# M8317E.net
KiCad netlist of a schematic drawn in EAGLE
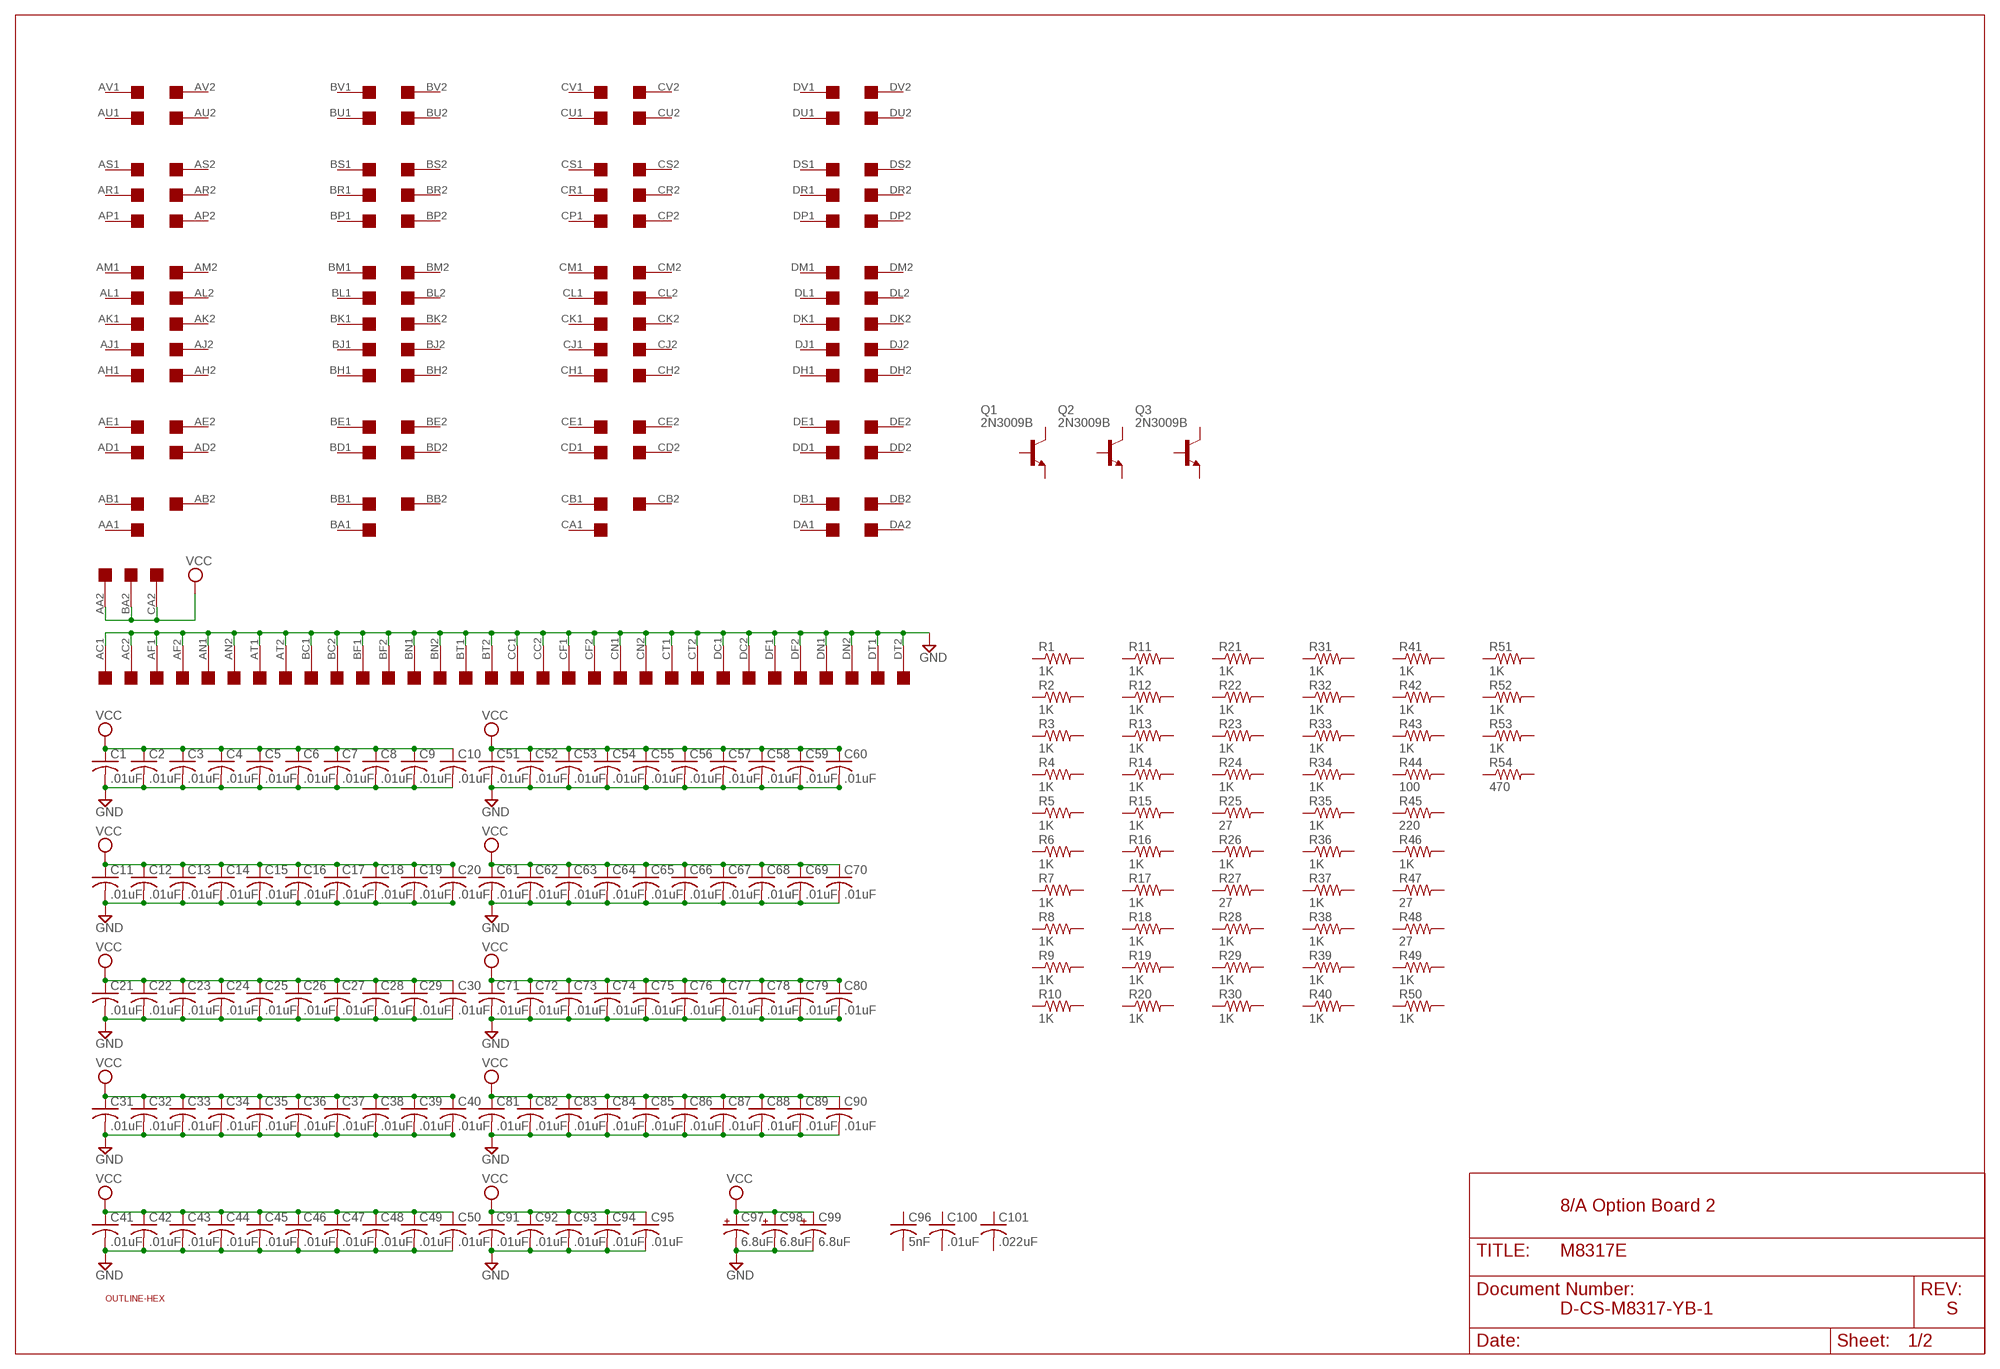
[diagram p0: schematic, sheet 1]
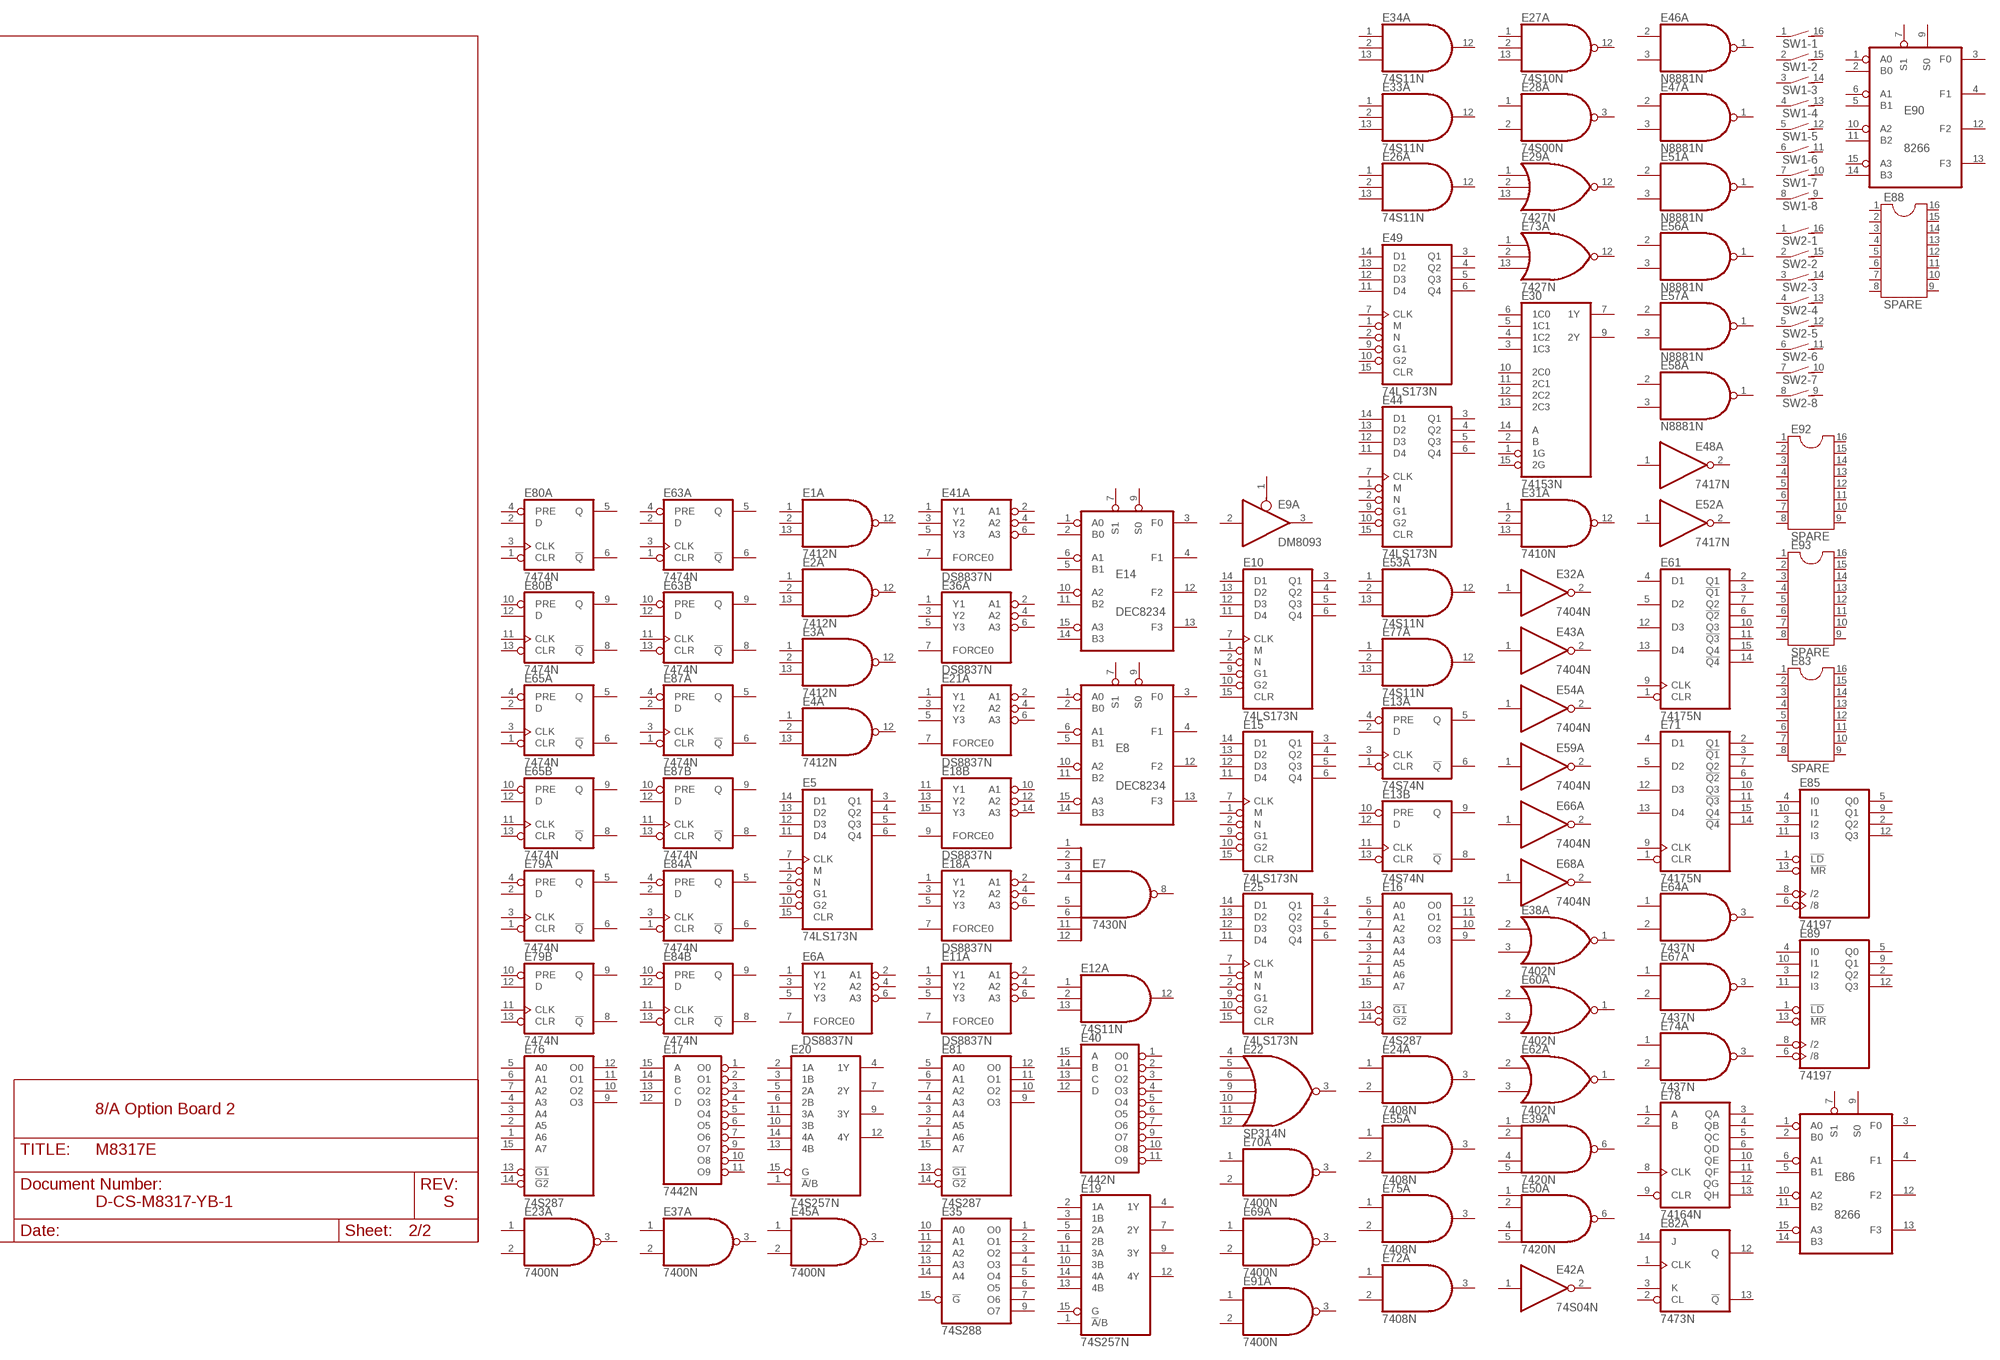
[diagram p1: schematic, sheet 2]

(export (version "E")
  (design (tool "Eeschema 10.0.6"))
  (components
    (comp (ref "C1")
      (value ".01uF")
      (footprint "eagle-import:C063-025X075")
      (libsource (lib "eagle-import") (part "C-US"))
    )
    (comp (ref "C2")
      (value ".01uF")
      (footprint "eagle-import:C063-025X075")
      (libsource (lib "eagle-import") (part "C-US"))
    )
    (comp (ref "C3")
      (value ".01uF")
      (footprint "eagle-import:C063-025X075")
      (libsource (lib "eagle-import") (part "C-US"))
    )
    (comp (ref "C4")
      (value ".01uF")
      (footprint "eagle-import:C063-025X075")
      (libsource (lib "eagle-import") (part "C-US"))
    )
    (comp (ref "C5")
      (value ".01uF")
      (footprint "eagle-import:C063-025X075")
      (libsource (lib "eagle-import") (part "C-US"))
    )
    (comp (ref "C6")
      (value ".01uF")
      (footprint "eagle-import:C063-025X075")
      (libsource (lib "eagle-import") (part "C-US"))
    )
    (comp (ref "C7")
      (value ".01uF")
      (footprint "eagle-import:C063-025X075")
      (libsource (lib "eagle-import") (part "C-US"))
    )
    (comp (ref "C8")
      (value ".01uF")
      (footprint "eagle-import:C063-025X075")
      (libsource (lib "eagle-import") (part "C-US"))
    )
    (comp (ref "C9")
      (value ".01uF")
      (footprint "eagle-import:C063-025X075")
      (libsource (lib "eagle-import") (part "C-US"))
    )
    (comp (ref "C10")
      (value ".01uF")
      (footprint "eagle-import:C063-025X075")
      (libsource (lib "eagle-import") (part "C-US"))
    )
    (comp (ref "C11")
      (value ".01uF")
      (footprint "eagle-import:C063-025X075")
      (libsource (lib "eagle-import") (part "C-US"))
    )
    (comp (ref "C12")
      (value ".01uF")
      (footprint "eagle-import:C063-025X075")
      (libsource (lib "eagle-import") (part "C-US"))
    )
    (comp (ref "C13")
      (value ".01uF")
      (footprint "eagle-import:C063-025X075")
      (libsource (lib "eagle-import") (part "C-US"))
    )
    (comp (ref "C14")
      (value ".01uF")
      (footprint "eagle-import:C063-025X075")
      (libsource (lib "eagle-import") (part "C-US"))
    )
    (comp (ref "C15")
      (value ".01uF")
      (footprint "eagle-import:C063-025X075")
      (libsource (lib "eagle-import") (part "C-US"))
    )
    (comp (ref "C16")
      (value ".01uF")
      (footprint "eagle-import:C063-025X075")
      (libsource (lib "eagle-import") (part "C-US"))
    )
    (comp (ref "C17")
      (value ".01uF")
      (footprint "eagle-import:C063-025X075")
      (libsource (lib "eagle-import") (part "C-US"))
    )
    (comp (ref "C18")
      (value ".01uF")
      (footprint "eagle-import:C063-025X075")
      (libsource (lib "eagle-import") (part "C-US"))
    )
    (comp (ref "C19")
      (value ".01uF")
      (footprint "eagle-import:C063-025X075")
      (libsource (lib "eagle-import") (part "C-US"))
    )
    (comp (ref "C20")
      (value ".01uF")
      (footprint "eagle-import:C063-025X075")
      (libsource (lib "eagle-import") (part "C-US"))
    )
    (comp (ref "C21")
      (value ".01uF")
      (footprint "eagle-import:C063-025X075")
      (libsource (lib "eagle-import") (part "C-US"))
    )
    (comp (ref "C22")
      (value ".01uF")
      (footprint "eagle-import:C063-025X075")
      (libsource (lib "eagle-import") (part "C-US"))
    )
    (comp (ref "C23")
      (value ".01uF")
      (footprint "eagle-import:C063-025X075")
      (libsource (lib "eagle-import") (part "C-US"))
    )
    (comp (ref "C24")
      (value ".01uF")
      (footprint "eagle-import:C063-025X075")
      (libsource (lib "eagle-import") (part "C-US"))
    )
    (comp (ref "C25")
      (value ".01uF")
      (footprint "eagle-import:C063-025X075")
      (libsource (lib "eagle-import") (part "C-US"))
    )
    (comp (ref "C26")
      (value ".01uF")
      (footprint "eagle-import:C063-025X075")
      (libsource (lib "eagle-import") (part "C-US"))
    )
    (comp (ref "C27")
      (value ".01uF")
      (footprint "eagle-import:C063-025X075")
      (libsource (lib "eagle-import") (part "C-US"))
    )
    (comp (ref "C28")
      (value ".01uF")
      (footprint "eagle-import:C063-025X075")
      (libsource (lib "eagle-import") (part "C-US"))
    )
    (comp (ref "C29")
      (value ".01uF")
      (footprint "eagle-import:C063-025X075")
      (libsource (lib "eagle-import") (part "C-US"))
    )
    (comp (ref "C30")
      (value ".01uF")
      (footprint "eagle-import:C063-025X075")
      (libsource (lib "eagle-import") (part "C-US"))
    )
    (comp (ref "C31")
      (value ".01uF")
      (footprint "eagle-import:C063-025X075")
      (libsource (lib "eagle-import") (part "C-US"))
    )
    (comp (ref "C32")
      (value ".01uF")
      (footprint "eagle-import:C063-025X075")
      (libsource (lib "eagle-import") (part "C-US"))
    )
    (comp (ref "C33")
      (value ".01uF")
      (footprint "eagle-import:C063-025X075")
      (libsource (lib "eagle-import") (part "C-US"))
    )
    (comp (ref "C34")
      (value ".01uF")
      (footprint "eagle-import:C063-025X075")
      (libsource (lib "eagle-import") (part "C-US"))
    )
    (comp (ref "C35")
      (value ".01uF")
      (footprint "eagle-import:C063-025X075")
      (libsource (lib "eagle-import") (part "C-US"))
    )
    (comp (ref "C36")
      (value ".01uF")
      (footprint "eagle-import:C063-025X075")
      (libsource (lib "eagle-import") (part "C-US"))
    )
    (comp (ref "C37")
      (value ".01uF")
      (footprint "eagle-import:C063-025X075")
      (libsource (lib "eagle-import") (part "C-US"))
    )
    (comp (ref "C38")
      (value ".01uF")
      (footprint "eagle-import:C063-025X075")
      (libsource (lib "eagle-import") (part "C-US"))
    )
    (comp (ref "C39")
      (value ".01uF")
      (footprint "eagle-import:C063-025X075")
      (libsource (lib "eagle-import") (part "C-US"))
    )
    (comp (ref "C40")
      (value ".01uF")
      (footprint "eagle-import:C063-025X075")
      (libsource (lib "eagle-import") (part "C-US"))
    )
    (comp (ref "C41")
      (value ".01uF")
      (footprint "eagle-import:C063-025X075")
      (libsource (lib "eagle-import") (part "C-US"))
    )
    (comp (ref "C42")
      (value ".01uF")
      (footprint "eagle-import:C063-025X075")
      (libsource (lib "eagle-import") (part "C-US"))
    )
    (comp (ref "C43")
      (value ".01uF")
      (footprint "eagle-import:C063-025X075")
      (libsource (lib "eagle-import") (part "C-US"))
    )
    (comp (ref "C44")
      (value ".01uF")
      (footprint "eagle-import:C063-025X075")
      (libsource (lib "eagle-import") (part "C-US"))
    )
    (comp (ref "C45")
      (value ".01uF")
      (footprint "eagle-import:C063-025X075")
      (libsource (lib "eagle-import") (part "C-US"))
    )
    (comp (ref "C46")
      (value ".01uF")
      (footprint "eagle-import:C063-025X075")
      (libsource (lib "eagle-import") (part "C-US"))
    )
    (comp (ref "C47")
      (value ".01uF")
      (footprint "eagle-import:C063-025X075")
      (libsource (lib "eagle-import") (part "C-US"))
    )
    (comp (ref "C48")
      (value ".01uF")
      (footprint "eagle-import:C063-025X075")
      (libsource (lib "eagle-import") (part "C-US"))
    )
    (comp (ref "C49")
      (value ".01uF")
      (footprint "eagle-import:C063-025X075")
      (libsource (lib "eagle-import") (part "C-US"))
    )
    (comp (ref "C50")
      (value ".01uF")
      (footprint "eagle-import:C063-025X075")
      (libsource (lib "eagle-import") (part "C-US"))
    )
    (comp (ref "C51")
      (value ".01uF")
      (footprint "eagle-import:C063-025X075")
      (libsource (lib "eagle-import") (part "C-US"))
    )
    (comp (ref "C52")
      (value ".01uF")
      (footprint "eagle-import:C063-025X075")
      (libsource (lib "eagle-import") (part "C-US"))
    )
    (comp (ref "C53")
      (value ".01uF")
      (footprint "eagle-import:C063-025X075")
      (libsource (lib "eagle-import") (part "C-US"))
    )
    (comp (ref "C54")
      (value ".01uF")
      (footprint "eagle-import:C063-025X075")
      (libsource (lib "eagle-import") (part "C-US"))
    )
    (comp (ref "C55")
      (value ".01uF")
      (footprint "eagle-import:C063-025X075")
      (libsource (lib "eagle-import") (part "C-US"))
    )
    (comp (ref "C56")
      (value ".01uF")
      (footprint "eagle-import:C063-025X075")
      (libsource (lib "eagle-import") (part "C-US"))
    )
    (comp (ref "C57")
      (value ".01uF")
      (footprint "eagle-import:C063-025X075")
      (libsource (lib "eagle-import") (part "C-US"))
    )
    (comp (ref "C58")
      (value ".01uF")
      (footprint "eagle-import:C063-025X075")
      (libsource (lib "eagle-import") (part "C-US"))
    )
    (comp (ref "C59")
      (value ".01uF")
      (footprint "eagle-import:C063-025X075")
      (libsource (lib "eagle-import") (part "C-US"))
    )
    (comp (ref "C60")
      (value ".01uF")
      (footprint "eagle-import:C063-025X075")
      (libsource (lib "eagle-import") (part "C-US"))
    )
    (comp (ref "C61")
      (value ".01uF")
      (footprint "eagle-import:C063-025X075")
      (libsource (lib "eagle-import") (part "C-US"))
    )
    (comp (ref "C62")
      (value ".01uF")
      (footprint "eagle-import:C063-025X075")
      (libsource (lib "eagle-import") (part "C-US"))
    )
    (comp (ref "C63")
      (value ".01uF")
      (footprint "eagle-import:C063-025X075")
      (libsource (lib "eagle-import") (part "C-US"))
    )
    (comp (ref "C64")
      (value ".01uF")
      (footprint "eagle-import:C063-025X075")
      (libsource (lib "eagle-import") (part "C-US"))
    )
    (comp (ref "C65")
      (value ".01uF")
      (footprint "eagle-import:C063-025X075")
      (libsource (lib "eagle-import") (part "C-US"))
    )
    (comp (ref "C66")
      (value ".01uF")
      (footprint "eagle-import:C063-025X075")
      (libsource (lib "eagle-import") (part "C-US"))
    )
    (comp (ref "C67")
      (value ".01uF")
      (footprint "eagle-import:C063-025X075")
      (libsource (lib "eagle-import") (part "C-US"))
    )
    (comp (ref "C68")
      (value ".01uF")
      (footprint "eagle-import:C063-025X075")
      (libsource (lib "eagle-import") (part "C-US"))
    )
    (comp (ref "C69")
      (value ".01uF")
      (footprint "eagle-import:C063-025X075")
      (libsource (lib "eagle-import") (part "C-US"))
    )
    (comp (ref "C70")
      (value ".01uF")
      (footprint "eagle-import:C063-025X075")
      (libsource (lib "eagle-import") (part "C-US"))
    )
    (comp (ref "C71")
      (value ".01uF")
      (footprint "eagle-import:C063-025X075")
      (libsource (lib "eagle-import") (part "C-US"))
    )
    (comp (ref "C72")
      (value ".01uF")
      (footprint "eagle-import:C063-025X075")
      (libsource (lib "eagle-import") (part "C-US"))
    )
    (comp (ref "C73")
      (value ".01uF")
      (footprint "eagle-import:C063-025X075")
      (libsource (lib "eagle-import") (part "C-US"))
    )
    (comp (ref "C74")
      (value ".01uF")
      (footprint "eagle-import:C063-025X075")
      (libsource (lib "eagle-import") (part "C-US"))
    )
    (comp (ref "C75")
      (value ".01uF")
      (footprint "eagle-import:C063-025X075")
      (libsource (lib "eagle-import") (part "C-US"))
    )
    (comp (ref "C76")
      (value ".01uF")
      (footprint "eagle-import:C063-025X075")
      (libsource (lib "eagle-import") (part "C-US"))
    )
    (comp (ref "C77")
      (value ".01uF")
      (footprint "eagle-import:C063-025X075")
      (libsource (lib "eagle-import") (part "C-US"))
    )
    (comp (ref "C78")
      (value ".01uF")
      (footprint "eagle-import:C063-025X075")
      (libsource (lib "eagle-import") (part "C-US"))
    )
    (comp (ref "C79")
      (value ".01uF")
      (footprint "eagle-import:C063-025X075")
      (libsource (lib "eagle-import") (part "C-US"))
    )
    (comp (ref "C80")
      (value ".01uF")
      (footprint "eagle-import:C063-025X075")
      (libsource (lib "eagle-import") (part "C-US"))
    )
    (comp (ref "C81")
      (value ".01uF")
      (footprint "eagle-import:C063-025X075")
      (libsource (lib "eagle-import") (part "C-US"))
    )
    (comp (ref "C82")
      (value ".01uF")
      (footprint "eagle-import:C063-025X075")
      (libsource (lib "eagle-import") (part "C-US"))
    )
    (comp (ref "C83")
      (value ".01uF")
      (footprint "eagle-import:C063-025X075")
      (libsource (lib "eagle-import") (part "C-US"))
    )
    (comp (ref "C84")
      (value ".01uF")
      (footprint "eagle-import:C063-025X075")
      (libsource (lib "eagle-import") (part "C-US"))
    )
    (comp (ref "C85")
      (value ".01uF")
      (footprint "eagle-import:C063-025X075")
      (libsource (lib "eagle-import") (part "C-US"))
    )
    (comp (ref "C86")
      (value ".01uF")
      (footprint "eagle-import:C063-025X075")
      (libsource (lib "eagle-import") (part "C-US"))
    )
    (comp (ref "C87")
      (value ".01uF")
      (footprint "eagle-import:C063-025X075")
      (libsource (lib "eagle-import") (part "C-US"))
    )
    (comp (ref "C88")
      (value ".01uF")
      (footprint "eagle-import:C063-025X075")
      (libsource (lib "eagle-import") (part "C-US"))
    )
    (comp (ref "C89")
      (value ".01uF")
      (footprint "eagle-import:C063-025X075")
      (libsource (lib "eagle-import") (part "C-US"))
    )
    (comp (ref "C90")
      (value ".01uF")
      (footprint "eagle-import:C063-025X075")
      (libsource (lib "eagle-import") (part "C-US"))
    )
    (comp (ref "C91")
      (value ".01uF")
      (footprint "eagle-import:C063-025X075")
      (libsource (lib "eagle-import") (part "C-US"))
    )
    (comp (ref "C92")
      (value ".01uF")
      (footprint "eagle-import:C063-025X075")
      (libsource (lib "eagle-import") (part "C-US"))
    )
    (comp (ref "C93")
      (value ".01uF")
      (footprint "eagle-import:C063-025X075")
      (libsource (lib "eagle-import") (part "C-US"))
    )
    (comp (ref "C94")
      (value ".01uF")
      (footprint "eagle-import:C063-025X075")
      (libsource (lib "eagle-import") (part "C-US"))
    )
    (comp (ref "C95")
      (value ".01uF")
      (footprint "eagle-import:C063-025X075")
      (libsource (lib "eagle-import") (part "C-US"))
    )
    (comp (ref "C96")
      (value "5nF")
      (footprint "eagle-import:C063-025X075")
      (libsource (lib "eagle-import") (part "C-US"))
    )
    (comp (ref "C97")
      (value "6.8uF")
      (footprint "eagle-import:E12-8")
      (libsource (lib "eagle-import") (part "CPOL-USE20-8AXIAL"))
    )
    (comp (ref "C98")
      (value "6.8uF")
      (footprint "eagle-import:E12-8")
      (libsource (lib "eagle-import") (part "CPOL-USE20-8AXIAL"))
    )
    (comp (ref "C99")
      (value "6.8uF")
      (footprint "eagle-import:E12-8")
      (libsource (lib "eagle-import") (part "CPOL-USE20-8AXIAL"))
    )
    (comp (ref "C100")
      (value ".01uF")
      (footprint "eagle-import:C063-025X075")
      (libsource (lib "eagle-import") (part "C-US"))
    )
    (comp (ref "C101")
      (value ".022uF")
      (footprint "eagle-import:C063-025X075")
      (libsource (lib "eagle-import") (part "C-US"))
    )
    (comp (ref "Q1")
      (value "2N3009B")
      (footprint "eagle-import:TO5")
      (libsource (lib "eagle-import") (part "-NPN-TO5"))
    )
    (comp (ref "Q2")
      (value "2N3009B")
      (footprint "eagle-import:TO5")
      (libsource (lib "eagle-import") (part "-NPN-TO5"))
    )
    (comp (ref "Q3")
      (value "2N3009B")
      (footprint "eagle-import:TO5")
      (libsource (lib "eagle-import") (part "-NPN-TO5"))
    )
    (comp (ref "R1")
      (value "1K")
      (footprint "eagle-import:0207_10")
      (libsource (lib "eagle-import") (part "R-US_0207/10"))
    )
    (comp (ref "R2")
      (value "1K")
      (footprint "eagle-import:0207_10")
      (libsource (lib "eagle-import") (part "R-US_0207/10"))
    )
    (comp (ref "R3")
      (value "1K")
      (footprint "eagle-import:0207_10")
      (libsource (lib "eagle-import") (part "R-US_0207/10"))
    )
    (comp (ref "R4")
      (value "1K")
      (footprint "eagle-import:0207_10")
      (libsource (lib "eagle-import") (part "R-US_0207/10"))
    )
    (comp (ref "R5")
      (value "1K")
      (footprint "eagle-import:0207_10")
      (libsource (lib "eagle-import") (part "R-US_0207/10"))
    )
    (comp (ref "R6")
      (value "1K")
      (footprint "eagle-import:0207_10")
      (libsource (lib "eagle-import") (part "R-US_0207/10"))
    )
    (comp (ref "R7")
      (value "1K")
      (footprint "eagle-import:0207_10")
      (libsource (lib "eagle-import") (part "R-US_0207/10"))
    )
    (comp (ref "R8")
      (value "1K")
      (footprint "eagle-import:0207_10")
      (libsource (lib "eagle-import") (part "R-US_0207/10"))
    )
    (comp (ref "R9")
      (value "1K")
      (footprint "eagle-import:0207_10")
      (libsource (lib "eagle-import") (part "R-US_0207/10"))
    )
    (comp (ref "R10")
      (value "1K")
      (footprint "eagle-import:0207_10")
      (libsource (lib "eagle-import") (part "R-US_0207/10"))
    )
    (comp (ref "R11")
      (value "1K")
      (footprint "eagle-import:0207_10")
      (libsource (lib "eagle-import") (part "R-US_0207/10"))
    )
    (comp (ref "R12")
      (value "1K")
      (footprint "eagle-import:0207_10")
      (libsource (lib "eagle-import") (part "R-US_0207/10"))
    )
    (comp (ref "R13")
      (value "1K")
      (footprint "eagle-import:0207_10")
      (libsource (lib "eagle-import") (part "R-US_0207/10"))
    )
    (comp (ref "R14")
      (value "1K")
      (footprint "eagle-import:0207_10")
      (libsource (lib "eagle-import") (part "R-US_0207/10"))
    )
    (comp (ref "R15")
      (value "1K")
      (footprint "eagle-import:0207_10")
      (libsource (lib "eagle-import") (part "R-US_0207/10"))
    )
    (comp (ref "R16")
      (value "1K")
      (footprint "eagle-import:0207_10")
      (libsource (lib "eagle-import") (part "R-US_0207/10"))
    )
    (comp (ref "R17")
      (value "1K")
      (footprint "eagle-import:0207_10")
      (libsource (lib "eagle-import") (part "R-US_0207/10"))
    )
    (comp (ref "R18")
      (value "1K")
      (footprint "eagle-import:0207_10")
      (libsource (lib "eagle-import") (part "R-US_0207/10"))
    )
    (comp (ref "R19")
      (value "1K")
      (footprint "eagle-import:0207_10")
      (libsource (lib "eagle-import") (part "R-US_0207/10"))
    )
    (comp (ref "R20")
      (value "1K")
      (footprint "eagle-import:0207_10")
      (libsource (lib "eagle-import") (part "R-US_0207/10"))
    )
    (comp (ref "R21")
      (value "1K")
      (footprint "eagle-import:0207_10")
      (libsource (lib "eagle-import") (part "R-US_0207/10"))
    )
    (comp (ref "R22")
      (value "1K")
      (footprint "eagle-import:0207_10")
      (libsource (lib "eagle-import") (part "R-US_0207/10"))
    )
    (comp (ref "R23")
      (value "1K")
      (footprint "eagle-import:0207_10")
      (libsource (lib "eagle-import") (part "R-US_0207/10"))
    )
    (comp (ref "R24")
      (value "1K")
      (footprint "eagle-import:0207_10")
      (libsource (lib "eagle-import") (part "R-US_0207/10"))
    )
    (comp (ref "R25")
      (value "27")
      (footprint "eagle-import:0207_10")
      (libsource (lib "eagle-import") (part "R-US_0207/10"))
    )
    (comp (ref "R26")
      (value "1K")
      (footprint "eagle-import:0207_10")
      (libsource (lib "eagle-import") (part "R-US_0207/10"))
    )
    (comp (ref "R27")
      (value "27")
      (footprint "eagle-import:0207_10")
      (libsource (lib "eagle-import") (part "R-US_0207/10"))
    )
    (comp (ref "R28")
      (value "1K")
      (footprint "eagle-import:0207_10")
      (libsource (lib "eagle-import") (part "R-US_0207/10"))
    )
    (comp (ref "R29")
      (value "1K")
      (footprint "eagle-import:0207_10")
      (libsource (lib "eagle-import") (part "R-US_0207/10"))
    )
    (comp (ref "R30")
      (value "1K")
      (footprint "eagle-import:0207_10")
      (libsource (lib "eagle-import") (part "R-US_0207/10"))
    )
    (comp (ref "R31")
      (value "1K")
      (footprint "eagle-import:0207_10")
      (libsource (lib "eagle-import") (part "R-US_0207/10"))
    )
    (comp (ref "R32")
      (value "1K")
      (footprint "eagle-import:0207_10")
      (libsource (lib "eagle-import") (part "R-US_0207/10"))
    )
    (comp (ref "R33")
      (value "1K")
      (footprint "eagle-import:0207_10")
      (libsource (lib "eagle-import") (part "R-US_0207/10"))
    )
    (comp (ref "R34")
      (value "1K")
      (footprint "eagle-import:0207_10")
      (libsource (lib "eagle-import") (part "R-US_0207/10"))
    )
    (comp (ref "R35")
      (value "1K")
      (footprint "eagle-import:0207_10")
      (libsource (lib "eagle-import") (part "R-US_0207/10"))
    )
    (comp (ref "R36")
      (value "1K")
      (footprint "eagle-import:0207_10")
      (libsource (lib "eagle-import") (part "R-US_0207/10"))
    )
    (comp (ref "R37")
      (value "1K")
      (footprint "eagle-import:0207_10")
      (libsource (lib "eagle-import") (part "R-US_0207/10"))
    )
    (comp (ref "R38")
      (value "1K")
      (footprint "eagle-import:0207_10")
      (libsource (lib "eagle-import") (part "R-US_0207/10"))
    )
    (comp (ref "R39")
      (value "1K")
      (footprint "eagle-import:0207_10")
      (libsource (lib "eagle-import") (part "R-US_0207/10"))
    )
    (comp (ref "R40")
      (value "1K")
      (footprint "eagle-import:0207_10")
      (libsource (lib "eagle-import") (part "R-US_0207/10"))
    )
    (comp (ref "R41")
      (value "1K")
      (footprint "eagle-import:0207_10")
      (libsource (lib "eagle-import") (part "R-US_0207/10"))
    )
    (comp (ref "R42")
      (value "1K")
      (footprint "eagle-import:0207_10")
      (libsource (lib "eagle-import") (part "R-US_0207/10"))
    )
    (comp (ref "R43")
      (value "1K")
      (footprint "eagle-import:0207_10")
      (libsource (lib "eagle-import") (part "R-US_0207/10"))
    )
    (comp (ref "R44")
      (value "100")
      (footprint "eagle-import:0207_10")
      (libsource (lib "eagle-import") (part "R-US_0207/10"))
    )
    (comp (ref "R45")
      (value "220")
      (footprint "eagle-import:0207_10")
      (libsource (lib "eagle-import") (part "R-US_0207/10"))
    )
    (comp (ref "R46")
      (value "1K")
      (footprint "eagle-import:0207_10")
      (libsource (lib "eagle-import") (part "R-US_0207/10"))
    )
    (comp (ref "R47")
      (value "27")
      (footprint "eagle-import:0207_10")
      (libsource (lib "eagle-import") (part "R-US_0207/10"))
    )
    (comp (ref "R48")
      (value "27")
      (footprint "eagle-import:0207_10")
      (libsource (lib "eagle-import") (part "R-US_0207/10"))
    )
    (comp (ref "R49")
      (value "1K")
      (footprint "eagle-import:0207_10")
      (libsource (lib "eagle-import") (part "R-US_0207/10"))
    )
    (comp (ref "R50")
      (value "1K")
      (footprint "eagle-import:0207_10")
      (libsource (lib "eagle-import") (part "R-US_0207/10"))
    )
    (comp (ref "R51")
      (value "1K")
      (footprint "eagle-import:0207_10")
      (libsource (lib "eagle-import") (part "R-US_0207/10"))
    )
    (comp (ref "R52")
      (value "1K")
      (footprint "eagle-import:0207_10")
      (libsource (lib "eagle-import") (part "R-US_0207/10"))
    )
    (comp (ref "R53")
      (value "1K")
      (footprint "eagle-import:0207_10")
      (libsource (lib "eagle-import") (part "R-US_0207/10"))
    )
    (comp (ref "R54")
      (value "470")
      (footprint "eagle-import:0207_10")
      (libsource (lib "eagle-import") (part "R-US_0207/10"))
    )
    (comp (ref "U$1")
      (value "HEX")
      (footprint "eagle-import:EDGE-CON12")
      (libsource (lib "eagle-import") (part "HEX"))
    )
    (comp (ref "U$2")
      (value "OUTLINE-HEX")
      (footprint "eagle-import:HEX-HEIGHT")
      (libsource (lib "eagle-import") (part "OUTLINE-HEX"))
    )
    (comp (ref "E1")
      (value "7412N")
      (footprint "eagle-import:DIL14")
      (libsource (lib "eagle-import") (part "7412N"))
    )
    (comp (ref "E2")
      (value "7412N")
      (footprint "eagle-import:DIL14")
      (libsource (lib "eagle-import") (part "7412N"))
    )
    (comp (ref "E3")
      (value "7412N")
      (footprint "eagle-import:DIL14")
      (libsource (lib "eagle-import") (part "7412N"))
    )
    (comp (ref "E4")
      (value "7412N")
      (footprint "eagle-import:DIL14")
      (libsource (lib "eagle-import") (part "7412N"))
    )
    (comp (ref "E5")
      (value "74LS173N")
      (footprint "eagle-import:DIL16")
      (libsource (lib "eagle-import") (part "74173NLS"))
    )
    (comp (ref "E6")
      (value "DS8837N")
      (footprint "eagle-import:DIL16")
      (libsource (lib "eagle-import") (part "DS8837N"))
    )
    (comp (ref "E7")
      (value "7430N")
      (footprint "eagle-import:DIL14")
      (libsource (lib "eagle-import") (part "7430N"))
    )
    (comp (ref "E8")
      (value "DEC8234")
      (footprint "eagle-import:DIL16")
      (libsource (lib "eagle-import") (part "DEC8235"))
    )
    (comp (ref "E9")
      (value "DM8093")
      (footprint "eagle-import:DIL14")
      (libsource (lib "eagle-import") (part "74125N"))
    )
    (comp (ref "E10")
      (value "74LS173N")
      (footprint "eagle-import:DIL16")
      (libsource (lib "eagle-import") (part "74173NLS"))
    )
    (comp (ref "E11")
      (value "DS8837N")
      (footprint "eagle-import:DIL16")
      (libsource (lib "eagle-import") (part "DS8837N"))
    )
    (comp (ref "E12")
      (value "74S11N")
      (footprint "eagle-import:DIL14")
      (libsource (lib "eagle-import") (part "7411NS"))
    )
    (comp (ref "E13")
      (value "74S74N")
      (footprint "eagle-import:DIL14")
      (libsource (lib "eagle-import") (part "7474NS"))
    )
    (comp (ref "E14")
      (value "DEC8234")
      (footprint "eagle-import:DIL16")
      (libsource (lib "eagle-import") (part "DEC8235"))
    )
    (comp (ref "E15")
      (value "74LS173N")
      (footprint "eagle-import:DIL16")
      (libsource (lib "eagle-import") (part "74173NLS"))
    )
    (comp (ref "E16")
      (value "74S287")
      (footprint "eagle-import:DIL16")
      (libsource (lib "eagle-import") (part "74S287"))
    )
    (comp (ref "E17")
      (value "7442N")
      (footprint "eagle-import:DIL16")
      (libsource (lib "eagle-import") (part "7442NLS"))
    )
    (comp (ref "E18")
      (value "DS8837N")
      (footprint "eagle-import:DIL16")
      (libsource (lib "eagle-import") (part "DS8837N"))
    )
    (comp (ref "E19")
      (value "74S257N")
      (footprint "eagle-import:DIL16")
      (libsource (lib "eagle-import") (part "74257NS"))
    )
    (comp (ref "E20")
      (value "74S257N")
      (footprint "eagle-import:DIL16")
      (libsource (lib "eagle-import") (part "74257NS"))
    )
    (comp (ref "E21")
      (value "DS8837N")
      (footprint "eagle-import:DIL16")
      (libsource (lib "eagle-import") (part "DS8837N"))
    )
    (comp (ref "E22")
      (value "SP314N")
      (footprint "eagle-import:DIL14")
      (libsource (lib "eagle-import") (part "SP314N"))
    )
    (comp (ref "E23")
      (value "7400N")
      (footprint "eagle-import:DIL14")
      (libsource (lib "eagle-import") (part "7400N"))
    )
    (comp (ref "E24")
      (value "7408N")
      (footprint "eagle-import:DIL14")
      (libsource (lib "eagle-import") (part "7408NS"))
    )
    (comp (ref "E25")
      (value "74LS173N")
      (footprint "eagle-import:DIL16")
      (libsource (lib "eagle-import") (part "74173NLS"))
    )
    (comp (ref "E26")
      (value "74S11N")
      (footprint "eagle-import:DIL14")
      (libsource (lib "eagle-import") (part "7411NS"))
    )
    (comp (ref "E27")
      (value "74S10N")
      (footprint "eagle-import:DIL14")
      (libsource (lib "eagle-import") (part "7410NS"))
    )
    (comp (ref "E28")
      (value "74S00N")
      (footprint "eagle-import:DIL14")
      (libsource (lib "eagle-import") (part "7400N"))
    )
    (comp (ref "E29")
      (value "7427N")
      (footprint "eagle-import:DIL14")
      (libsource (lib "eagle-import") (part "7427NLS"))
    )
    (comp (ref "E30")
      (value "74153N")
      (footprint "eagle-import:DIL16")
      (libsource (lib "eagle-import") (part "74153NS"))
    )
    (comp (ref "E31")
      (value "7410N")
      (footprint "eagle-import:DIL14")
      (libsource (lib "eagle-import") (part "7410NS"))
    )
    (comp (ref "E32")
      (value "7404N")
      (footprint "eagle-import:DIL14")
      (libsource (lib "eagle-import") (part "7404N"))
    )
    (comp (ref "E33")
      (value "74S11N")
      (footprint "eagle-import:DIL14")
      (libsource (lib "eagle-import") (part "7411NS"))
    )
    (comp (ref "E34")
      (value "74S11N")
      (footprint "eagle-import:DIL14")
      (libsource (lib "eagle-import") (part "7411NS"))
    )
    (comp (ref "E35")
      (value "74S288")
      (footprint "eagle-import:DIL16")
      (libsource (lib "eagle-import") (part "74S288"))
    )
    (comp (ref "E36")
      (value "DS8837N")
      (footprint "eagle-import:DIL16")
      (libsource (lib "eagle-import") (part "DS8837N"))
    )
    (comp (ref "E37")
      (value "7400N")
      (footprint "eagle-import:DIL14")
      (libsource (lib "eagle-import") (part "7400N"))
    )
    (comp (ref "E38")
      (value "7402N")
      (footprint "eagle-import:DIL14")
      (libsource (lib "eagle-import") (part "7402N"))
    )
    (comp (ref "E39")
      (value "7420N")
      (footprint "eagle-import:DIL14")
      (libsource (lib "eagle-import") (part "7420N"))
    )
    (comp (ref "E40")
      (value "7442N")
      (footprint "eagle-import:DIL16")
      (libsource (lib "eagle-import") (part "7442NLS"))
    )
    (comp (ref "E41")
      (value "DS8837N")
      (footprint "eagle-import:DIL16")
      (libsource (lib "eagle-import") (part "DS8837N"))
    )
    (comp (ref "E42")
      (value "74S04N")
      (footprint "eagle-import:DIL14")
      (libsource (lib "eagle-import") (part "7404N"))
    )
    (comp (ref "E43")
      (value "7404N")
      (footprint "eagle-import:DIL14")
      (libsource (lib "eagle-import") (part "7404N"))
    )
    (comp (ref "E44")
      (value "74LS173N")
      (footprint "eagle-import:DIL16")
      (libsource (lib "eagle-import") (part "74173NLS"))
    )
    (comp (ref "E45")
      (value "7400N")
      (footprint "eagle-import:DIL14")
      (libsource (lib "eagle-import") (part "7400N"))
    )
    (comp (ref "E46")
      (value "N8881N")
      (footprint "eagle-import:DIL14")
      (libsource (lib "eagle-import") (part "N8881N"))
    )
    (comp (ref "E47")
      (value "N8881N")
      (footprint "eagle-import:DIL14")
      (libsource (lib "eagle-import") (part "N8881N"))
    )
    (comp (ref "E48")
      (value "7417N")
      (footprint "eagle-import:DIL14")
      (libsource (lib "eagle-import") (part "7417N"))
    )
    (comp (ref "E49")
      (value "74LS173N")
      (footprint "eagle-import:DIL16")
      (libsource (lib "eagle-import") (part "74173NLS"))
    )
    (comp (ref "E50")
      (value "7420N")
      (footprint "eagle-import:DIL14")
      (libsource (lib "eagle-import") (part "7420N"))
    )
    (comp (ref "E51")
      (value "N8881N")
      (footprint "eagle-import:DIL14")
      (libsource (lib "eagle-import") (part "N8881N"))
    )
    (comp (ref "E52")
      (value "7417N")
      (footprint "eagle-import:DIL14")
      (libsource (lib "eagle-import") (part "7417N"))
    )
    (comp (ref "E53")
      (value "74S11N")
      (footprint "eagle-import:DIL14")
      (libsource (lib "eagle-import") (part "7411NS"))
    )
    (comp (ref "E54")
      (value "7404N")
      (footprint "eagle-import:DIL14")
      (libsource (lib "eagle-import") (part "7404N"))
    )
    (comp (ref "E55")
      (value "7408N")
      (footprint "eagle-import:DIL14")
      (libsource (lib "eagle-import") (part "7408NS"))
    )
    (comp (ref "E56")
      (value "N8881N")
      (footprint "eagle-import:DIL14")
      (libsource (lib "eagle-import") (part "N8881N"))
    )
    (comp (ref "E57")
      (value "N8881N")
      (footprint "eagle-import:DIL14")
      (libsource (lib "eagle-import") (part "N8881N"))
    )
    (comp (ref "E58")
      (value "N8881N")
      (footprint "eagle-import:DIL14")
      (libsource (lib "eagle-import") (part "N8881N"))
    )
    (comp (ref "E59")
      (value "7404N")
      (footprint "eagle-import:DIL14")
      (libsource (lib "eagle-import") (part "7404N"))
    )
    (comp (ref "E60")
      (value "7402N")
      (footprint "eagle-import:DIL14")
      (libsource (lib "eagle-import") (part "7402N"))
    )
    (comp (ref "E61")
      (value "74175N")
      (footprint "eagle-import:DIL16")
      (libsource (lib "eagle-import") (part "74175N"))
    )
    (comp (ref "E62")
      (value "7402N")
      (footprint "eagle-import:DIL14")
      (libsource (lib "eagle-import") (part "7402N"))
    )
    (comp (ref "E63")
      (value "7474N")
      (footprint "eagle-import:DIL14")
      (libsource (lib "eagle-import") (part "7474NS"))
    )
    (comp (ref "E64")
      (value "7437N")
      (footprint "eagle-import:DIL14")
      (libsource (lib "eagle-import") (part "7437N"))
    )
    (comp (ref "E65")
      (value "7474N")
      (footprint "eagle-import:DIL14")
      (libsource (lib "eagle-import") (part "7474NS"))
    )
    (comp (ref "E66")
      (value "7404N")
      (footprint "eagle-import:DIL14")
      (libsource (lib "eagle-import") (part "7404N"))
    )
    (comp (ref "E67")
      (value "7437N")
      (footprint "eagle-import:DIL14")
      (libsource (lib "eagle-import") (part "7437N"))
    )
    (comp (ref "E68")
      (value "7404N")
      (footprint "eagle-import:DIL14")
      (libsource (lib "eagle-import") (part "7404N"))
    )
    (comp (ref "E69")
      (value "7400N")
      (footprint "eagle-import:DIL14")
      (libsource (lib "eagle-import") (part "7400N"))
    )
    (comp (ref "E70")
      (value "7400N")
      (footprint "eagle-import:DIL14")
      (libsource (lib "eagle-import") (part "7400N"))
    )
    (comp (ref "E71")
      (value "74175N")
      (footprint "eagle-import:DIL16")
      (libsource (lib "eagle-import") (part "74175N"))
    )
    (comp (ref "E72")
      (value "7408N")
      (footprint "eagle-import:DIL14")
      (libsource (lib "eagle-import") (part "7408NS"))
    )
    (comp (ref "E73")
      (value "7427N")
      (footprint "eagle-import:DIL14")
      (libsource (lib "eagle-import") (part "7427NLS"))
    )
    (comp (ref "E74")
      (value "7437N")
      (footprint "eagle-import:DIL14")
      (libsource (lib "eagle-import") (part "7437N"))
    )
    (comp (ref "E75")
      (value "7408N")
      (footprint "eagle-import:DIL14")
      (libsource (lib "eagle-import") (part "7408NS"))
    )
    (comp (ref "E76")
      (value "74S287")
      (footprint "eagle-import:DIL16")
      (libsource (lib "eagle-import") (part "74S287"))
    )
    (comp (ref "E77")
      (value "74S11N")
      (footprint "eagle-import:DIL14")
      (libsource (lib "eagle-import") (part "7411NS"))
    )
    (comp (ref "E78")
      (value "74164N")
      (footprint "eagle-import:DIL14")
      (libsource (lib "eagle-import") (part "74164N"))
    )
    (comp (ref "E79")
      (value "7474N")
      (footprint "eagle-import:DIL14")
      (libsource (lib "eagle-import") (part "7474NS"))
    )
    (comp (ref "E80")
      (value "7474N")
      (footprint "eagle-import:DIL14")
      (libsource (lib "eagle-import") (part "7474NS"))
    )
    (comp (ref "E81")
      (value "74S287")
      (footprint "eagle-import:DIL16")
      (libsource (lib "eagle-import") (part "74S287"))
    )
    (comp (ref "E82")
      (value "7473N")
      (footprint "eagle-import:DIL14")
      (libsource (lib "eagle-import") (part "7473NLS"))
    )
    (comp (ref "E83")
      (value "SPARE")
      (footprint "eagle-import:SOCKET-16")
      (libsource (lib "eagle-import") (part "DIL16S"))
    )
    (comp (ref "E84")
      (value "7474N")
      (footprint "eagle-import:DIL14")
      (libsource (lib "eagle-import") (part "7474NS"))
    )
    (comp (ref "E85")
      (value "74197")
      (footprint "eagle-import:DIL14")
      (libsource (lib "eagle-import") (part "74LS197"))
    )
    (comp (ref "E86")
      (value "8266")
      (footprint "eagle-import:DIL16")
      (libsource (lib "eagle-import") (part "8266"))
    )
    (comp (ref "E87")
      (value "7474N")
      (footprint "eagle-import:DIL14")
      (libsource (lib "eagle-import") (part "7474NS"))
    )
    (comp (ref "E88")
      (value "SPARE")
      (footprint "eagle-import:SOCKET-16")
      (libsource (lib "eagle-import") (part "DIL16S"))
    )
    (comp (ref "E89")
      (value "74197")
      (footprint "eagle-import:DIL14")
      (libsource (lib "eagle-import") (part "74LS197"))
    )
    (comp (ref "E90")
      (value "8266")
      (footprint "eagle-import:DIL16")
      (libsource (lib "eagle-import") (part "8266"))
    )
    (comp (ref "E91")
      (value "7400N")
      (footprint "eagle-import:DIL14")
      (libsource (lib "eagle-import") (part "7400N"))
    )
    (comp (ref "E92")
      (value "SPARE")
      (footprint "eagle-import:SOCKET-16")
      (libsource (lib "eagle-import") (part "DIL16S"))
    )
    (comp (ref "E93")
      (value "SPARE")
      (footprint "eagle-import:SOCKET-16")
      (libsource (lib "eagle-import") (part "DIL16S"))
    )
    (comp (ref "SW1")
      (value "DIP08S")
      (footprint "eagle-import:DIP08S")
      (libsource (lib "eagle-import") (part "DIP08S"))
    )
    (comp (ref "SW2")
      (value "DIP08S")
      (footprint "eagle-import:DIP08S")
      (libsource (lib "eagle-import") (part "DIP08S"))
    )
  )
  (nets
    (net (code "1") (name "GND") (class "Default")
      (node (ref "C1") (pin "2") (pinfunction "2_2") (pintype "passive"))
      (node (ref "C10") (pin "2") (pinfunction "2_2") (pintype "passive"))
      (node (ref "C11") (pin "2") (pinfunction "2_2") (pintype "passive"))
      (node (ref "C12") (pin "2") (pinfunction "2_2") (pintype "passive"))
      (node (ref "C13") (pin "2") (pinfunction "2_2") (pintype "passive"))
      (node (ref "C14") (pin "2") (pinfunction "2_2") (pintype "passive"))
      (node (ref "C15") (pin "2") (pinfunction "2_2") (pintype "passive"))
      (node (ref "C16") (pin "2") (pinfunction "2_2") (pintype "passive"))
      (node (ref "C17") (pin "2") (pinfunction "2_2") (pintype "passive"))
      (node (ref "C18") (pin "2") (pinfunction "2_2") (pintype "passive"))
      (node (ref "C19") (pin "2") (pinfunction "2_2") (pintype "passive"))
      (node (ref "C2") (pin "2") (pinfunction "2_2") (pintype "passive"))
      (node (ref "C20") (pin "2") (pinfunction "2_2") (pintype "passive"))
      (node (ref "C21") (pin "2") (pinfunction "2_2") (pintype "passive"))
      (node (ref "C22") (pin "2") (pinfunction "2_2") (pintype "passive"))
      (node (ref "C23") (pin "2") (pinfunction "2_2") (pintype "passive"))
      (node (ref "C24") (pin "2") (pinfunction "2_2") (pintype "passive"))
      (node (ref "C25") (pin "2") (pinfunction "2_2") (pintype "passive"))
      (node (ref "C26") (pin "2") (pinfunction "2_2") (pintype "passive"))
      (node (ref "C27") (pin "2") (pinfunction "2_2") (pintype "passive"))
      (node (ref "C28") (pin "2") (pinfunction "2_2") (pintype "passive"))
      (node (ref "C29") (pin "2") (pinfunction "2_2") (pintype "passive"))
      (node (ref "C3") (pin "2") (pinfunction "2_2") (pintype "passive"))
      (node (ref "C30") (pin "2") (pinfunction "2_2") (pintype "passive"))
      (node (ref "C31") (pin "2") (pinfunction "2_2") (pintype "passive"))
      (node (ref "C32") (pin "2") (pinfunction "2_2") (pintype "passive"))
      (node (ref "C33") (pin "2") (pinfunction "2_2") (pintype "passive"))
      (node (ref "C34") (pin "2") (pinfunction "2_2") (pintype "passive"))
      (node (ref "C35") (pin "2") (pinfunction "2_2") (pintype "passive"))
      (node (ref "C36") (pin "2") (pinfunction "2_2") (pintype "passive"))
      (node (ref "C37") (pin "2") (pinfunction "2_2") (pintype "passive"))
      (node (ref "C38") (pin "2") (pinfunction "2_2") (pintype "passive"))
      (node (ref "C39") (pin "2") (pinfunction "2_2") (pintype "passive"))
      (node (ref "C4") (pin "2") (pinfunction "2_2") (pintype "passive"))
      (node (ref "C40") (pin "2") (pinfunction "2_2") (pintype "passive"))
      (node (ref "C41") (pin "2") (pinfunction "2_2") (pintype "passive"))
      (node (ref "C42") (pin "2") (pinfunction "2_2") (pintype "passive"))
      (node (ref "C43") (pin "2") (pinfunction "2_2") (pintype "passive"))
      (node (ref "C44") (pin "2") (pinfunction "2_2") (pintype "passive"))
      (node (ref "C45") (pin "2") (pinfunction "2_2") (pintype "passive"))
      (node (ref "C46") (pin "2") (pinfunction "2_2") (pintype "passive"))
      (node (ref "C47") (pin "2") (pinfunction "2_2") (pintype "passive"))
      (node (ref "C48") (pin "2") (pinfunction "2_2") (pintype "passive"))
      (node (ref "C49") (pin "2") (pinfunction "2_2") (pintype "passive"))
      (node (ref "C5") (pin "2") (pinfunction "2_2") (pintype "passive"))
      (node (ref "C50") (pin "2") (pinfunction "2_2") (pintype "passive"))
      (node (ref "C51") (pin "2") (pinfunction "2_2") (pintype "passive"))
      (node (ref "C52") (pin "2") (pinfunction "2_2") (pintype "passive"))
      (node (ref "C53") (pin "2") (pinfunction "2_2") (pintype "passive"))
      (node (ref "C54") (pin "2") (pinfunction "2_2") (pintype "passive"))
      (node (ref "C55") (pin "2") (pinfunction "2_2") (pintype "passive"))
      (node (ref "C56") (pin "2") (pinfunction "2_2") (pintype "passive"))
      (node (ref "C57") (pin "2") (pinfunction "2_2") (pintype "passive"))
      (node (ref "C58") (pin "2") (pinfunction "2_2") (pintype "passive"))
      (node (ref "C59") (pin "2") (pinfunction "2_2") (pintype "passive"))
      (node (ref "C6") (pin "2") (pinfunction "2_2") (pintype "passive"))
      (node (ref "C60") (pin "2") (pinfunction "2_2") (pintype "passive"))
      (node (ref "C61") (pin "2") (pinfunction "2_2") (pintype "passive"))
      (node (ref "C62") (pin "2") (pinfunction "2_2") (pintype "passive"))
      (node (ref "C63") (pin "2") (pinfunction "2_2") (pintype "passive"))
      (node (ref "C64") (pin "2") (pinfunction "2_2") (pintype "passive"))
      (node (ref "C65") (pin "2") (pinfunction "2_2") (pintype "passive"))
      (node (ref "C66") (pin "2") (pinfunction "2_2") (pintype "passive"))
      (node (ref "C67") (pin "2") (pinfunction "2_2") (pintype "passive"))
      (node (ref "C68") (pin "2") (pinfunction "2_2") (pintype "passive"))
      (node (ref "C69") (pin "2") (pinfunction "2_2") (pintype "passive"))
      (node (ref "C7") (pin "2") (pinfunction "2_2") (pintype "passive"))
      (node (ref "C70") (pin "2") (pinfunction "2_2") (pintype "passive"))
      (node (ref "C71") (pin "2") (pinfunction "2_2") (pintype "passive"))
      (node (ref "C72") (pin "2") (pinfunction "2_2") (pintype "passive"))
      (node (ref "C73") (pin "2") (pinfunction "2_2") (pintype "passive"))
      (node (ref "C74") (pin "2") (pinfunction "2_2") (pintype "passive"))
      (node (ref "C75") (pin "2") (pinfunction "2_2") (pintype "passive"))
      (node (ref "C76") (pin "2") (pinfunction "2_2") (pintype "passive"))
      (node (ref "C77") (pin "2") (pinfunction "2_2") (pintype "passive"))
      (node (ref "C78") (pin "2") (pinfunction "2_2") (pintype "passive"))
      (node (ref "C79") (pin "2") (pinfunction "2_2") (pintype "passive"))
      (node (ref "C8") (pin "2") (pinfunction "2_2") (pintype "passive"))
      (node (ref "C80") (pin "2") (pinfunction "2_2") (pintype "passive"))
      (node (ref "C81") (pin "2") (pinfunction "2_2") (pintype "passive"))
      (node (ref "C82") (pin "2") (pinfunction "2_2") (pintype "passive"))
      (node (ref "C83") (pin "2") (pinfunction "2_2") (pintype "passive"))
      (node (ref "C84") (pin "2") (pinfunction "2_2") (pintype "passive"))
      (node (ref "C85") (pin "2") (pinfunction "2_2") (pintype "passive"))
      (node (ref "C86") (pin "2") (pinfunction "2_2") (pintype "passive"))
      (node (ref "C87") (pin "2") (pinfunction "2_2") (pintype "passive"))
      (node (ref "C88") (pin "2") (pinfunction "2_2") (pintype "passive"))
      (node (ref "C89") (pin "2") (pinfunction "2_2") (pintype "passive"))
      (node (ref "C9") (pin "2") (pinfunction "2_2") (pintype "passive"))
      (node (ref "C90") (pin "2") (pinfunction "2_2") (pintype "passive"))
      (node (ref "C91") (pin "2") (pinfunction "2_2") (pintype "passive"))
      (node (ref "C92") (pin "2") (pinfunction "2_2") (pintype "passive"))
      (node (ref "C93") (pin "2") (pinfunction "2_2") (pintype "passive"))
      (node (ref "C94") (pin "2") (pinfunction "2_2") (pintype "passive"))
      (node (ref "C95") (pin "2") (pinfunction "2_2") (pintype "passive"))
      (node (ref "C97") (pin "-") (pinfunction "-_-") (pintype "passive"))
      (node (ref "C98") (pin "-") (pinfunction "-_-") (pintype "passive"))
      (node (ref "C99") (pin "-") (pinfunction "-_-") (pintype "passive"))
      (node (ref "U$1") (pin "AC1") (pinfunction "1_AC1") (pintype "bidirectional"))
      (node (ref "U$1") (pin "AC2") (pinfunction "1_AC2") (pintype "bidirectional"))
      (node (ref "U$1") (pin "AF1") (pinfunction "1_AF1") (pintype "bidirectional"))
      (node (ref "U$1") (pin "AF2") (pinfunction "1_AF2") (pintype "bidirectional"))
      (node (ref "U$1") (pin "AN1") (pinfunction "1_AN1") (pintype "bidirectional"))
      (node (ref "U$1") (pin "AN2") (pinfunction "1_AN2") (pintype "bidirectional"))
      (node (ref "U$1") (pin "AT1") (pinfunction "1_AT1") (pintype "bidirectional"))
      (node (ref "U$1") (pin "AT2") (pinfunction "1_AT2") (pintype "bidirectional"))
      (node (ref "U$1") (pin "BC1") (pinfunction "1_BC1") (pintype "bidirectional"))
      (node (ref "U$1") (pin "BC2") (pinfunction "1_BC2") (pintype "bidirectional"))
      (node (ref "U$1") (pin "BF1") (pinfunction "1_BF1") (pintype "bidirectional"))
      (node (ref "U$1") (pin "BF2") (pinfunction "1_BF2") (pintype "bidirectional"))
      (node (ref "U$1") (pin "BN1") (pinfunction "1_BN1") (pintype "bidirectional"))
      (node (ref "U$1") (pin "BN2") (pinfunction "1_BN2") (pintype "bidirectional"))
      (node (ref "U$1") (pin "BT1") (pinfunction "1_BT1") (pintype "bidirectional"))
      (node (ref "U$1") (pin "BT2") (pinfunction "1_BT2") (pintype "bidirectional"))
      (node (ref "U$1") (pin "CC1") (pinfunction "1_CC1") (pintype "bidirectional"))
      (node (ref "U$1") (pin "CC2") (pinfunction "1_CC2") (pintype "bidirectional"))
      (node (ref "U$1") (pin "CF1") (pinfunction "1_CF1") (pintype "bidirectional"))
      (node (ref "U$1") (pin "CF2") (pinfunction "1_CF2") (pintype "bidirectional"))
      (node (ref "U$1") (pin "CN1") (pinfunction "1_CN1") (pintype "bidirectional"))
      (node (ref "U$1") (pin "CN2") (pinfunction "1_CN2") (pintype "bidirectional"))
      (node (ref "U$1") (pin "CT1") (pinfunction "1_CT1") (pintype "bidirectional"))
      (node (ref "U$1") (pin "CT2") (pinfunction "1_CT2") (pintype "bidirectional"))
      (node (ref "U$1") (pin "DC1") (pinfunction "1_DC1") (pintype "bidirectional"))
      (node (ref "U$1") (pin "DC2") (pinfunction "1_DC2") (pintype "bidirectional"))
      (node (ref "U$1") (pin "DF1") (pinfunction "1_DF1") (pintype "bidirectional"))
      (node (ref "U$1") (pin "DF2") (pinfunction "1_DF2") (pintype "bidirectional"))
      (node (ref "U$1") (pin "DN1") (pinfunction "1_DN1") (pintype "bidirectional"))
      (node (ref "U$1") (pin "DN2") (pinfunction "1_DN2") (pintype "bidirectional"))
      (node (ref "U$1") (pin "DT1") (pinfunction "1_DT1") (pintype "bidirectional"))
      (node (ref "U$1") (pin "DT2") (pinfunction "1_DT2") (pintype "bidirectional"))
    )
    (net (code "2") (name "VCC") (class "Default")
      (node (ref "C1") (pin "1") (pinfunction "1_1") (pintype "passive"))
      (node (ref "C10") (pin "1") (pinfunction "1_1") (pintype "passive"))
      (node (ref "C11") (pin "1") (pinfunction "1_1") (pintype "passive"))
      (node (ref "C12") (pin "1") (pinfunction "1_1") (pintype "passive"))
      (node (ref "C13") (pin "1") (pinfunction "1_1") (pintype "passive"))
      (node (ref "C14") (pin "1") (pinfunction "1_1") (pintype "passive"))
      (node (ref "C15") (pin "1") (pinfunction "1_1") (pintype "passive"))
      (node (ref "C16") (pin "1") (pinfunction "1_1") (pintype "passive"))
      (node (ref "C17") (pin "1") (pinfunction "1_1") (pintype "passive"))
      (node (ref "C18") (pin "1") (pinfunction "1_1") (pintype "passive"))
      (node (ref "C19") (pin "1") (pinfunction "1_1") (pintype "passive"))
      (node (ref "C2") (pin "1") (pinfunction "1_1") (pintype "passive"))
      (node (ref "C20") (pin "1") (pinfunction "1_1") (pintype "passive"))
      (node (ref "C21") (pin "1") (pinfunction "1_1") (pintype "passive"))
      (node (ref "C22") (pin "1") (pinfunction "1_1") (pintype "passive"))
      (node (ref "C23") (pin "1") (pinfunction "1_1") (pintype "passive"))
      (node (ref "C24") (pin "1") (pinfunction "1_1") (pintype "passive"))
      (node (ref "C25") (pin "1") (pinfunction "1_1") (pintype "passive"))
      (node (ref "C26") (pin "1") (pinfunction "1_1") (pintype "passive"))
      (node (ref "C27") (pin "1") (pinfunction "1_1") (pintype "passive"))
      (node (ref "C28") (pin "1") (pinfunction "1_1") (pintype "passive"))
      (node (ref "C29") (pin "1") (pinfunction "1_1") (pintype "passive"))
      (node (ref "C3") (pin "1") (pinfunction "1_1") (pintype "passive"))
      (node (ref "C30") (pin "1") (pinfunction "1_1") (pintype "passive"))
      (node (ref "C31") (pin "1") (pinfunction "1_1") (pintype "passive"))
      (node (ref "C32") (pin "1") (pinfunction "1_1") (pintype "passive"))
      (node (ref "C33") (pin "1") (pinfunction "1_1") (pintype "passive"))
      (node (ref "C34") (pin "1") (pinfunction "1_1") (pintype "passive"))
      (node (ref "C35") (pin "1") (pinfunction "1_1") (pintype "passive"))
      (node (ref "C36") (pin "1") (pinfunction "1_1") (pintype "passive"))
      (node (ref "C37") (pin "1") (pinfunction "1_1") (pintype "passive"))
      (node (ref "C38") (pin "1") (pinfunction "1_1") (pintype "passive"))
      (node (ref "C39") (pin "1") (pinfunction "1_1") (pintype "passive"))
      (node (ref "C4") (pin "1") (pinfunction "1_1") (pintype "passive"))
      (node (ref "C40") (pin "1") (pinfunction "1_1") (pintype "passive"))
      (node (ref "C41") (pin "1") (pinfunction "1_1") (pintype "passive"))
      (node (ref "C42") (pin "1") (pinfunction "1_1") (pintype "passive"))
      (node (ref "C43") (pin "1") (pinfunction "1_1") (pintype "passive"))
      (node (ref "C44") (pin "1") (pinfunction "1_1") (pintype "passive"))
      (node (ref "C45") (pin "1") (pinfunction "1_1") (pintype "passive"))
      (node (ref "C46") (pin "1") (pinfunction "1_1") (pintype "passive"))
      (node (ref "C47") (pin "1") (pinfunction "1_1") (pintype "passive"))
      (node (ref "C48") (pin "1") (pinfunction "1_1") (pintype "passive"))
      (node (ref "C49") (pin "1") (pinfunction "1_1") (pintype "passive"))
      (node (ref "C5") (pin "1") (pinfunction "1_1") (pintype "passive"))
      (node (ref "C50") (pin "1") (pinfunction "1_1") (pintype "passive"))
      (node (ref "C51") (pin "1") (pinfunction "1_1") (pintype "passive"))
      (node (ref "C52") (pin "1") (pinfunction "1_1") (pintype "passive"))
      (node (ref "C53") (pin "1") (pinfunction "1_1") (pintype "passive"))
      (node (ref "C54") (pin "1") (pinfunction "1_1") (pintype "passive"))
      (node (ref "C55") (pin "1") (pinfunction "1_1") (pintype "passive"))
      (node (ref "C56") (pin "1") (pinfunction "1_1") (pintype "passive"))
      (node (ref "C57") (pin "1") (pinfunction "1_1") (pintype "passive"))
      (node (ref "C58") (pin "1") (pinfunction "1_1") (pintype "passive"))
      (node (ref "C59") (pin "1") (pinfunction "1_1") (pintype "passive"))
      (node (ref "C6") (pin "1") (pinfunction "1_1") (pintype "passive"))
      (node (ref "C60") (pin "1") (pinfunction "1_1") (pintype "passive"))
      (node (ref "C61") (pin "1") (pinfunction "1_1") (pintype "passive"))
      (node (ref "C62") (pin "1") (pinfunction "1_1") (pintype "passive"))
      (node (ref "C63") (pin "1") (pinfunction "1_1") (pintype "passive"))
      (node (ref "C64") (pin "1") (pinfunction "1_1") (pintype "passive"))
      (node (ref "C65") (pin "1") (pinfunction "1_1") (pintype "passive"))
      (node (ref "C66") (pin "1") (pinfunction "1_1") (pintype "passive"))
      (node (ref "C67") (pin "1") (pinfunction "1_1") (pintype "passive"))
      (node (ref "C68") (pin "1") (pinfunction "1_1") (pintype "passive"))
      (node (ref "C69") (pin "1") (pinfunction "1_1") (pintype "passive"))
      (node (ref "C7") (pin "1") (pinfunction "1_1") (pintype "passive"))
      (node (ref "C70") (pin "1") (pinfunction "1_1") (pintype "passive"))
      (node (ref "C71") (pin "1") (pinfunction "1_1") (pintype "passive"))
      (node (ref "C72") (pin "1") (pinfunction "1_1") (pintype "passive"))
      (node (ref "C73") (pin "1") (pinfunction "1_1") (pintype "passive"))
      (node (ref "C74") (pin "1") (pinfunction "1_1") (pintype "passive"))
      (node (ref "C75") (pin "1") (pinfunction "1_1") (pintype "passive"))
      (node (ref "C76") (pin "1") (pinfunction "1_1") (pintype "passive"))
      (node (ref "C77") (pin "1") (pinfunction "1_1") (pintype "passive"))
      (node (ref "C78") (pin "1") (pinfunction "1_1") (pintype "passive"))
      (node (ref "C79") (pin "1") (pinfunction "1_1") (pintype "passive"))
      (node (ref "C8") (pin "1") (pinfunction "1_1") (pintype "passive"))
      (node (ref "C80") (pin "1") (pinfunction "1_1") (pintype "passive"))
      (node (ref "C81") (pin "1") (pinfunction "1_1") (pintype "passive"))
      (node (ref "C82") (pin "1") (pinfunction "1_1") (pintype "passive"))
      (node (ref "C83") (pin "1") (pinfunction "1_1") (pintype "passive"))
      (node (ref "C84") (pin "1") (pinfunction "1_1") (pintype "passive"))
      (node (ref "C85") (pin "1") (pinfunction "1_1") (pintype "passive"))
      (node (ref "C86") (pin "1") (pinfunction "1_1") (pintype "passive"))
      (node (ref "C87") (pin "1") (pinfunction "1_1") (pintype "passive"))
      (node (ref "C88") (pin "1") (pinfunction "1_1") (pintype "passive"))
      (node (ref "C89") (pin "1") (pinfunction "1_1") (pintype "passive"))
      (node (ref "C9") (pin "1") (pinfunction "1_1") (pintype "passive"))
      (node (ref "C90") (pin "1") (pinfunction "1_1") (pintype "passive"))
      (node (ref "C91") (pin "1") (pinfunction "1_1") (pintype "passive"))
      (node (ref "C92") (pin "1") (pinfunction "1_1") (pintype "passive"))
      (node (ref "C93") (pin "1") (pinfunction "1_1") (pintype "passive"))
      (node (ref "C94") (pin "1") (pinfunction "1_1") (pintype "passive"))
      (node (ref "C95") (pin "1") (pinfunction "1_1") (pintype "passive"))
      (node (ref "C97") (pin "+") (pinfunction "+_+") (pintype "passive"))
      (node (ref "C98") (pin "+") (pinfunction "+_+") (pintype "passive"))
      (node (ref "C99") (pin "+") (pinfunction "+_+") (pintype "passive"))
      (node (ref "U$1") (pin "AA2") (pinfunction "1_AA2") (pintype "bidirectional"))
      (node (ref "U$1") (pin "BA2") (pinfunction "1_BA2") (pintype "bidirectional"))
      (node (ref "U$1") (pin "CA2") (pinfunction "1_CA2") (pintype "bidirectional"))
    )
    (net (code "3") (name "unconnected-(C96-Pad1)") (class "Default")
      (node (ref "C96") (pin "1") (pinfunction "1_1") (pintype "passive"))
    )
    (net (code "4") (name "unconnected-(C96-Pad2)") (class "Default")
      (node (ref "C96") (pin "2") (pinfunction "2_2") (pintype "passive"))
    )
    (net (code "5") (name "unconnected-(C100-Pad1)") (class "Default")
      (node (ref "C100") (pin "1") (pinfunction "1_1") (pintype "passive"))
    )
    (net (code "6") (name "unconnected-(C100-Pad2)") (class "Default")
      (node (ref "C100") (pin "2") (pinfunction "2_2") (pintype "passive"))
    )
    (net (code "7") (name "unconnected-(C101-Pad1)") (class "Default")
      (node (ref "C101") (pin "1") (pinfunction "1_1") (pintype "passive"))
    )
    (net (code "8") (name "unconnected-(C101-Pad2)") (class "Default")
      (node (ref "C101") (pin "2") (pinfunction "2_2") (pintype "passive"))
    )
    (net (code "9") (name "unconnected-(E1A-I0-Pad1)") (class "Default")
      (node (ref "E1") (pin "1") (pinfunction "I0_1") (pintype "input"))
    )
    (net (code "10") (name "unconnected-(E1A-I1-Pad2)") (class "Default")
      (node (ref "E1") (pin "2") (pinfunction "I1_2") (pintype "input"))
    )
    (net (code "11") (name "unconnected-(E1A-I2-Pad13)") (class "Default")
      (node (ref "E1") (pin "13") (pinfunction "I2_13") (pintype "input"))
    )
    (net (code "12") (name "unconnected-(E1A-O-Pad12)") (class "Default")
      (node (ref "E1") (pin "12") (pinfunction "O_12") (pintype "open_collector"))
    )
    (net (code "13") (name "unconnected-(E2A-I0-Pad1)") (class "Default")
      (node (ref "E2") (pin "1") (pinfunction "I0_1") (pintype "input"))
    )
    (net (code "14") (name "unconnected-(E2A-I1-Pad2)") (class "Default")
      (node (ref "E2") (pin "2") (pinfunction "I1_2") (pintype "input"))
    )
    (net (code "15") (name "unconnected-(E2A-I2-Pad13)") (class "Default")
      (node (ref "E2") (pin "13") (pinfunction "I2_13") (pintype "input"))
    )
    (net (code "16") (name "unconnected-(E2A-O-Pad12)") (class "Default")
      (node (ref "E2") (pin "12") (pinfunction "O_12") (pintype "open_collector"))
    )
    (net (code "17") (name "unconnected-(E3A-I0-Pad1)") (class "Default")
      (node (ref "E3") (pin "1") (pinfunction "I0_1") (pintype "input"))
    )
    (net (code "18") (name "unconnected-(E3A-I1-Pad2)") (class "Default")
      (node (ref "E3") (pin "2") (pinfunction "I1_2") (pintype "input"))
    )
    (net (code "19") (name "unconnected-(E3A-I2-Pad13)") (class "Default")
      (node (ref "E3") (pin "13") (pinfunction "I2_13") (pintype "input"))
    )
    (net (code "20") (name "unconnected-(E3A-O-Pad12)") (class "Default")
      (node (ref "E3") (pin "12") (pinfunction "O_12") (pintype "open_collector"))
    )
    (net (code "21") (name "unconnected-(E4A-I0-Pad1)") (class "Default")
      (node (ref "E4") (pin "1") (pinfunction "I0_1") (pintype "input"))
    )
    (net (code "22") (name "unconnected-(E4A-I1-Pad2)") (class "Default")
      (node (ref "E4") (pin "2") (pinfunction "I1_2") (pintype "input"))
    )
    (net (code "23") (name "unconnected-(E4A-I2-Pad13)") (class "Default")
      (node (ref "E4") (pin "13") (pinfunction "I2_13") (pintype "input"))
    )
    (net (code "24") (name "unconnected-(E4A-O-Pad12)") (class "Default")
      (node (ref "E4") (pin "12") (pinfunction "O_12") (pintype "open_collector"))
    )
    (net (code "25") (name "unconnected-(E5A-CLK-Pad7)") (class "Default")
      (node (ref "E5") (pin "7") (pinfunction "CLK_7") (pintype "input"))
    )
    (net (code "26") (name "unconnected-(E5A-CLR-Pad15)") (class "Default")
      (node (ref "E5") (pin "15") (pinfunction "CLR_15") (pintype "input"))
    )
    (net (code "27") (name "unconnected-(E5A-D1-Pad14)") (class "Default")
      (node (ref "E5") (pin "14") (pinfunction "D1_14") (pintype "input"))
    )
    (net (code "28") (name "unconnected-(E5A-D2-Pad13)") (class "Default")
      (node (ref "E5") (pin "13") (pinfunction "D2_13") (pintype "input"))
    )
    (net (code "29") (name "unconnected-(E5A-D3-Pad12)") (class "Default")
      (node (ref "E5") (pin "12") (pinfunction "D3_12") (pintype "input"))
    )
    (net (code "30") (name "unconnected-(E5A-D4-Pad11)") (class "Default")
      (node (ref "E5") (pin "11") (pinfunction "D4_11") (pintype "input"))
    )
    (net (code "31") (name "unconnected-(E5A-G1-Pad9)") (class "Default")
      (node (ref "E5") (pin "9") (pinfunction "G1_9") (pintype "input"))
    )
    (net (code "32") (name "unconnected-(E5A-G2-Pad10)") (class "Default")
      (node (ref "E5") (pin "10") (pinfunction "G2_10") (pintype "input"))
    )
    (net (code "33") (name "unconnected-(E5A-M-Pad1)") (class "Default")
      (node (ref "E5") (pin "1") (pinfunction "M_1") (pintype "input"))
    )
    (net (code "34") (name "unconnected-(E5A-N-Pad2)") (class "Default")
      (node (ref "E5") (pin "2") (pinfunction "N_2") (pintype "input"))
    )
    (net (code "35") (name "unconnected-(E5A-Q1-Pad3)") (class "Default")
      (node (ref "E5") (pin "3") (pinfunction "Q1_3") (pintype "tri_state"))
    )
    (net (code "36") (name "unconnected-(E5A-Q2-Pad4)") (class "Default")
      (node (ref "E5") (pin "4") (pinfunction "Q2_4") (pintype "tri_state"))
    )
    (net (code "37") (name "unconnected-(E5A-Q3-Pad5)") (class "Default")
      (node (ref "E5") (pin "5") (pinfunction "Q3_5") (pintype "tri_state"))
    )
    (net (code "38") (name "unconnected-(E5A-Q4-Pad6)") (class "Default")
      (node (ref "E5") (pin "6") (pinfunction "Q4_6") (pintype "tri_state"))
    )
    (net (code "39") (name "unconnected-(E6A-A1-Pad2)") (class "Default")
      (node (ref "E6") (pin "2") (pinfunction "A1_2") (pintype "output"))
    )
    (net (code "40") (name "unconnected-(E6A-A2-Pad4)") (class "Default")
      (node (ref "E6") (pin "4") (pinfunction "A2_4") (pintype "output"))
    )
    (net (code "41") (name "unconnected-(E6A-A3-Pad6)") (class "Default")
      (node (ref "E6") (pin "6") (pinfunction "A3_6") (pintype "output"))
    )
    (net (code "42") (name "unconnected-(E6A-FORCE0-Pad7)") (class "Default")
      (node (ref "E6") (pin "7") (pinfunction "FORCE0_7") (pintype "input"))
    )
    (net (code "43") (name "unconnected-(E6A-Y1-Pad1)") (class "Default")
      (node (ref "E6") (pin "1") (pinfunction "Y1_1") (pintype "input"))
    )
    (net (code "44") (name "unconnected-(E6A-Y2-Pad3)") (class "Default")
      (node (ref "E6") (pin "3") (pinfunction "Y2_3") (pintype "input"))
    )
    (net (code "45") (name "unconnected-(E6A-Y3-Pad5)") (class "Default")
      (node (ref "E6") (pin "5") (pinfunction "Y3_5") (pintype "input"))
    )
    (net (code "46") (name "unconnected-(E7D-I0-Pad1)") (class "Default")
      (node (ref "E7") (pin "1") (pinfunction "I0_1") (pintype "input"))
    )
    (net (code "47") (name "unconnected-(E7D-I1-Pad2)") (class "Default")
      (node (ref "E7") (pin "2") (pinfunction "I1_2") (pintype "input"))
    )
    (net (code "48") (name "unconnected-(E7D-I2-Pad3)") (class "Default")
      (node (ref "E7") (pin "3") (pinfunction "I2_3") (pintype "input"))
    )
    (net (code "49") (name "unconnected-(E7D-I3-Pad4)") (class "Default")
      (node (ref "E7") (pin "4") (pinfunction "I3_4") (pintype "input"))
    )
    (net (code "50") (name "unconnected-(E7D-I4-Pad5)") (class "Default")
      (node (ref "E7") (pin "5") (pinfunction "I4_5") (pintype "input"))
    )
    (net (code "51") (name "unconnected-(E7D-I5-Pad6)") (class "Default")
      (node (ref "E7") (pin "6") (pinfunction "I5_6") (pintype "input"))
    )
    (net (code "52") (name "unconnected-(E7D-I6-Pad11)") (class "Default")
      (node (ref "E7") (pin "11") (pinfunction "I6_11") (pintype "input"))
    )
    (net (code "53") (name "unconnected-(E7D-I7-Pad12)") (class "Default")
      (node (ref "E7") (pin "12") (pinfunction "I7_12") (pintype "input"))
    )
    (net (code "54") (name "unconnected-(E7D-O-Pad8)") (class "Default")
      (node (ref "E7") (pin "8") (pinfunction "O_8") (pintype "output"))
    )
    (net (code "55") (name "unconnected-(E8A-A0-Pad1)") (class "Default")
      (node (ref "E8") (pin "1") (pinfunction "A0_1") (pintype "input"))
    )
    (net (code "56") (name "unconnected-(E8A-A1-Pad6)") (class "Default")
      (node (ref "E8") (pin "6") (pinfunction "A1_6") (pintype "input"))
    )
    (net (code "57") (name "unconnected-(E8A-A2-Pad10)") (class "Default")
      (node (ref "E8") (pin "10") (pinfunction "A2_10") (pintype "input"))
    )
    (net (code "58") (name "unconnected-(E8A-A3-Pad15)") (class "Default")
      (node (ref "E8") (pin "15") (pinfunction "A3_15") (pintype "input"))
    )
    (net (code "59") (name "unconnected-(E8A-B0-Pad2)") (class "Default")
      (node (ref "E8") (pin "2") (pinfunction "B0_2") (pintype "input"))
    )
    (net (code "60") (name "unconnected-(E8A-B1-Pad5)") (class "Default")
      (node (ref "E8") (pin "5") (pinfunction "B1_5") (pintype "input"))
    )
    (net (code "61") (name "unconnected-(E8A-B2-Pad11)") (class "Default")
      (node (ref "E8") (pin "11") (pinfunction "B2_11") (pintype "input"))
    )
    (net (code "62") (name "unconnected-(E8A-B3-Pad14)") (class "Default")
      (node (ref "E8") (pin "14") (pinfunction "B3_14") (pintype "input"))
    )
    (net (code "63") (name "unconnected-(E8A-F0-Pad3)") (class "Default")
      (node (ref "E8") (pin "3") (pinfunction "F0_3") (pintype "open_collector"))
    )
    (net (code "64") (name "unconnected-(E8A-F1-Pad4)") (class "Default")
      (node (ref "E8") (pin "4") (pinfunction "F1_4") (pintype "open_collector"))
    )
    (net (code "65") (name "unconnected-(E8A-F2-Pad12)") (class "Default")
      (node (ref "E8") (pin "12") (pinfunction "F2_12") (pintype "open_collector"))
    )
    (net (code "66") (name "unconnected-(E8A-F3-Pad13)") (class "Default")
      (node (ref "E8") (pin "13") (pinfunction "F3_13") (pintype "open_collector"))
    )
    (net (code "67") (name "unconnected-(E8A-S0-Pad9)") (class "Default")
      (node (ref "E8") (pin "9") (pinfunction "S0_9") (pintype "input"))
    )
    (net (code "68") (name "unconnected-(E8A-S1-Pad7)") (class "Default")
      (node (ref "E8") (pin "7") (pinfunction "S1_7") (pintype "input"))
    )
    (net (code "69") (name "unconnected-(E9A-I-Pad2)") (class "Default")
      (node (ref "E9") (pin "2") (pinfunction "I_2") (pintype "input"))
    )
    (net (code "70") (name "unconnected-(E9A-O-Pad3)") (class "Default")
      (node (ref "E9") (pin "3") (pinfunction "O_3") (pintype "tri_state"))
    )
    (net (code "71") (name "unconnected-(E9A-OE-Pad1)") (class "Default")
      (node (ref "E9") (pin "1") (pinfunction "OE_1") (pintype "input"))
    )
    (net (code "72") (name "unconnected-(E10A-CLK-Pad7)") (class "Default")
      (node (ref "E10") (pin "7") (pinfunction "CLK_7") (pintype "input"))
    )
    (net (code "73") (name "unconnected-(E10A-CLR-Pad15)") (class "Default")
      (node (ref "E10") (pin "15") (pinfunction "CLR_15") (pintype "input"))
    )
    (net (code "74") (name "unconnected-(E10A-D1-Pad14)") (class "Default")
      (node (ref "E10") (pin "14") (pinfunction "D1_14") (pintype "input"))
    )
    (net (code "75") (name "unconnected-(E10A-D2-Pad13)") (class "Default")
      (node (ref "E10") (pin "13") (pinfunction "D2_13") (pintype "input"))
    )
    (net (code "76") (name "unconnected-(E10A-D3-Pad12)") (class "Default")
      (node (ref "E10") (pin "12") (pinfunction "D3_12") (pintype "input"))
    )
    (net (code "77") (name "unconnected-(E10A-D4-Pad11)") (class "Default")
      (node (ref "E10") (pin "11") (pinfunction "D4_11") (pintype "input"))
    )
    (net (code "78") (name "unconnected-(E10A-G1-Pad9)") (class "Default")
      (node (ref "E10") (pin "9") (pinfunction "G1_9") (pintype "input"))
    )
    (net (code "79") (name "unconnected-(E10A-G2-Pad10)") (class "Default")
      (node (ref "E10") (pin "10") (pinfunction "G2_10") (pintype "input"))
    )
    (net (code "80") (name "unconnected-(E10A-M-Pad1)") (class "Default")
      (node (ref "E10") (pin "1") (pinfunction "M_1") (pintype "input"))
    )
    (net (code "81") (name "unconnected-(E10A-N-Pad2)") (class "Default")
      (node (ref "E10") (pin "2") (pinfunction "N_2") (pintype "input"))
    )
    (net (code "82") (name "unconnected-(E10A-Q1-Pad3)") (class "Default")
      (node (ref "E10") (pin "3") (pinfunction "Q1_3") (pintype "tri_state"))
    )
    (net (code "83") (name "unconnected-(E10A-Q2-Pad4)") (class "Default")
      (node (ref "E10") (pin "4") (pinfunction "Q2_4") (pintype "tri_state"))
    )
    (net (code "84") (name "unconnected-(E10A-Q3-Pad5)") (class "Default")
      (node (ref "E10") (pin "5") (pinfunction "Q3_5") (pintype "tri_state"))
    )
    (net (code "85") (name "unconnected-(E10A-Q4-Pad6)") (class "Default")
      (node (ref "E10") (pin "6") (pinfunction "Q4_6") (pintype "tri_state"))
    )
    (net (code "86") (name "unconnected-(E11A-A1-Pad2)") (class "Default")
      (node (ref "E11") (pin "2") (pinfunction "A1_2") (pintype "output"))
    )
    (net (code "87") (name "unconnected-(E11A-A2-Pad4)") (class "Default")
      (node (ref "E11") (pin "4") (pinfunction "A2_4") (pintype "output"))
    )
    (net (code "88") (name "unconnected-(E11A-A3-Pad6)") (class "Default")
      (node (ref "E11") (pin "6") (pinfunction "A3_6") (pintype "output"))
    )
    (net (code "89") (name "unconnected-(E11A-FORCE0-Pad7)") (class "Default")
      (node (ref "E11") (pin "7") (pinfunction "FORCE0_7") (pintype "input"))
    )
    (net (code "90") (name "unconnected-(E11A-Y1-Pad1)") (class "Default")
      (node (ref "E11") (pin "1") (pinfunction "Y1_1") (pintype "input"))
    )
    (net (code "91") (name "unconnected-(E11A-Y2-Pad3)") (class "Default")
      (node (ref "E11") (pin "3") (pinfunction "Y2_3") (pintype "input"))
    )
    (net (code "92") (name "unconnected-(E11A-Y3-Pad5)") (class "Default")
      (node (ref "E11") (pin "5") (pinfunction "Y3_5") (pintype "input"))
    )
    (net (code "93") (name "unconnected-(E12A-I0-Pad1)") (class "Default")
      (node (ref "E12") (pin "1") (pinfunction "I0_1") (pintype "input"))
    )
    (net (code "94") (name "unconnected-(E12A-I1-Pad2)") (class "Default")
      (node (ref "E12") (pin "2") (pinfunction "I1_2") (pintype "input"))
    )
    (net (code "95") (name "unconnected-(E12A-I2-Pad13)") (class "Default")
      (node (ref "E12") (pin "13") (pinfunction "I2_13") (pintype "input"))
    )
    (net (code "96") (name "unconnected-(E12A-O-Pad12)") (class "Default")
      (node (ref "E12") (pin "12") (pinfunction "O_12") (pintype "output"))
    )
    (net (code "97") (name "unconnected-(E13A-CLK-Pad3)") (class "Default")
      (node (ref "E13") (pin "3") (pinfunction "CLK_3") (pintype "input"))
    )
    (net (code "98") (name "unconnected-(E13A-CLR-Pad1)") (class "Default")
      (node (ref "E13") (pin "1") (pinfunction "CLR_1") (pintype "input"))
    )
    (net (code "99") (name "unconnected-(E13A-D-Pad2)") (class "Default")
      (node (ref "E13") (pin "2") (pinfunction "D_2") (pintype "input"))
    )
    (net (code "100") (name "unconnected-(E13A-PRE-Pad4)") (class "Default")
      (node (ref "E13") (pin "4") (pinfunction "PRE_4") (pintype "input"))
    )
    (net (code "101") (name "unconnected-(E13A-Q-Pad5)") (class "Default")
      (node (ref "E13") (pin "5") (pinfunction "Q_5") (pintype "output"))
    )
    (net (code "102") (name "unconnected-(E13A-~{Q}-Pad6)") (class "Default")
      (node (ref "E13") (pin "6") (pinfunction "~{Q}_6") (pintype "output"))
    )
    (net (code "103") (name "unconnected-(E13B-CLK-Pad11)") (class "Default")
      (node (ref "E13") (pin "11") (pinfunction "CLK_11") (pintype "input"))
    )
    (net (code "104") (name "unconnected-(E13B-CLR-Pad13)") (class "Default")
      (node (ref "E13") (pin "13") (pinfunction "CLR_13") (pintype "input"))
    )
    (net (code "105") (name "unconnected-(E13B-D-Pad12)") (class "Default")
      (node (ref "E13") (pin "12") (pinfunction "D_12") (pintype "input"))
    )
    (net (code "106") (name "unconnected-(E13B-PRE-Pad10)") (class "Default")
      (node (ref "E13") (pin "10") (pinfunction "PRE_10") (pintype "input"))
    )
    (net (code "107") (name "unconnected-(E13B-Q-Pad9)") (class "Default")
      (node (ref "E13") (pin "9") (pinfunction "Q_9") (pintype "output"))
    )
    (net (code "108") (name "unconnected-(E13B-~{Q}-Pad8)") (class "Default")
      (node (ref "E13") (pin "8") (pinfunction "~{Q}_8") (pintype "output"))
    )
    (net (code "109") (name "unconnected-(E14A-A0-Pad1)") (class "Default")
      (node (ref "E14") (pin "1") (pinfunction "A0_1") (pintype "input"))
    )
    (net (code "110") (name "unconnected-(E14A-A1-Pad6)") (class "Default")
      (node (ref "E14") (pin "6") (pinfunction "A1_6") (pintype "input"))
    )
    (net (code "111") (name "unconnected-(E14A-A2-Pad10)") (class "Default")
      (node (ref "E14") (pin "10") (pinfunction "A2_10") (pintype "input"))
    )
    (net (code "112") (name "unconnected-(E14A-A3-Pad15)") (class "Default")
      (node (ref "E14") (pin "15") (pinfunction "A3_15") (pintype "input"))
    )
    (net (code "113") (name "unconnected-(E14A-B0-Pad2)") (class "Default")
      (node (ref "E14") (pin "2") (pinfunction "B0_2") (pintype "input"))
    )
    (net (code "114") (name "unconnected-(E14A-B1-Pad5)") (class "Default")
      (node (ref "E14") (pin "5") (pinfunction "B1_5") (pintype "input"))
    )
    (net (code "115") (name "unconnected-(E14A-B2-Pad11)") (class "Default")
      (node (ref "E14") (pin "11") (pinfunction "B2_11") (pintype "input"))
    )
    (net (code "116") (name "unconnected-(E14A-B3-Pad14)") (class "Default")
      (node (ref "E14") (pin "14") (pinfunction "B3_14") (pintype "input"))
    )
    (net (code "117") (name "unconnected-(E14A-F0-Pad3)") (class "Default")
      (node (ref "E14") (pin "3") (pinfunction "F0_3") (pintype "open_collector"))
    )
    (net (code "118") (name "unconnected-(E14A-F1-Pad4)") (class "Default")
      (node (ref "E14") (pin "4") (pinfunction "F1_4") (pintype "open_collector"))
    )
    (net (code "119") (name "unconnected-(E14A-F2-Pad12)") (class "Default")
      (node (ref "E14") (pin "12") (pinfunction "F2_12") (pintype "open_collector"))
    )
    (net (code "120") (name "unconnected-(E14A-F3-Pad13)") (class "Default")
      (node (ref "E14") (pin "13") (pinfunction "F3_13") (pintype "open_collector"))
    )
    (net (code "121") (name "unconnected-(E14A-S0-Pad9)") (class "Default")
      (node (ref "E14") (pin "9") (pinfunction "S0_9") (pintype "input"))
    )
    (net (code "122") (name "unconnected-(E14A-S1-Pad7)") (class "Default")
      (node (ref "E14") (pin "7") (pinfunction "S1_7") (pintype "input"))
    )
    (net (code "123") (name "unconnected-(E15A-CLK-Pad7)") (class "Default")
      (node (ref "E15") (pin "7") (pinfunction "CLK_7") (pintype "input"))
    )
    (net (code "124") (name "unconnected-(E15A-CLR-Pad15)") (class "Default")
      (node (ref "E15") (pin "15") (pinfunction "CLR_15") (pintype "input"))
    )
    (net (code "125") (name "unconnected-(E15A-D1-Pad14)") (class "Default")
      (node (ref "E15") (pin "14") (pinfunction "D1_14") (pintype "input"))
    )
    (net (code "126") (name "unconnected-(E15A-D2-Pad13)") (class "Default")
      (node (ref "E15") (pin "13") (pinfunction "D2_13") (pintype "input"))
    )
    (net (code "127") (name "unconnected-(E15A-D3-Pad12)") (class "Default")
      (node (ref "E15") (pin "12") (pinfunction "D3_12") (pintype "input"))
    )
    (net (code "128") (name "unconnected-(E15A-D4-Pad11)") (class "Default")
      (node (ref "E15") (pin "11") (pinfunction "D4_11") (pintype "input"))
    )
    (net (code "129") (name "unconnected-(E15A-G1-Pad9)") (class "Default")
      (node (ref "E15") (pin "9") (pinfunction "G1_9") (pintype "input"))
    )
    (net (code "130") (name "unconnected-(E15A-G2-Pad10)") (class "Default")
      (node (ref "E15") (pin "10") (pinfunction "G2_10") (pintype "input"))
    )
    (net (code "131") (name "unconnected-(E15A-M-Pad1)") (class "Default")
      (node (ref "E15") (pin "1") (pinfunction "M_1") (pintype "input"))
    )
    (net (code "132") (name "unconnected-(E15A-N-Pad2)") (class "Default")
      (node (ref "E15") (pin "2") (pinfunction "N_2") (pintype "input"))
    )
    (net (code "133") (name "unconnected-(E15A-Q1-Pad3)") (class "Default")
      (node (ref "E15") (pin "3") (pinfunction "Q1_3") (pintype "tri_state"))
    )
    (net (code "134") (name "unconnected-(E15A-Q2-Pad4)") (class "Default")
      (node (ref "E15") (pin "4") (pinfunction "Q2_4") (pintype "tri_state"))
    )
    (net (code "135") (name "unconnected-(E15A-Q3-Pad5)") (class "Default")
      (node (ref "E15") (pin "5") (pinfunction "Q3_5") (pintype "tri_state"))
    )
    (net (code "136") (name "unconnected-(E15A-Q4-Pad6)") (class "Default")
      (node (ref "E15") (pin "6") (pinfunction "Q4_6") (pintype "tri_state"))
    )
    (net (code "137") (name "unconnected-(E16A-A0-Pad5)") (class "Default")
      (node (ref "E16") (pin "5") (pinfunction "A0_5") (pintype "input"))
    )
    (net (code "138") (name "unconnected-(E16A-A1-Pad6)") (class "Default")
      (node (ref "E16") (pin "6") (pinfunction "A1_6") (pintype "input"))
    )
    (net (code "139") (name "unconnected-(E16A-A2-Pad7)") (class "Default")
      (node (ref "E16") (pin "7") (pinfunction "A2_7") (pintype "input"))
    )
    (net (code "140") (name "unconnected-(E16A-A3-Pad4)") (class "Default")
      (node (ref "E16") (pin "4") (pinfunction "A3_4") (pintype "input"))
    )
    (net (code "141") (name "unconnected-(E16A-A4-Pad3)") (class "Default")
      (node (ref "E16") (pin "3") (pinfunction "A4_3") (pintype "input"))
    )
    (net (code "142") (name "unconnected-(E16A-A5-Pad2)") (class "Default")
      (node (ref "E16") (pin "2") (pinfunction "A5_2") (pintype "input"))
    )
    (net (code "143") (name "unconnected-(E16A-A6-Pad1)") (class "Default")
      (node (ref "E16") (pin "1") (pinfunction "A6_1") (pintype "input"))
    )
    (net (code "144") (name "unconnected-(E16A-A7-Pad15)") (class "Default")
      (node (ref "E16") (pin "15") (pinfunction "A7_15") (pintype "input"))
    )
    (net (code "145") (name "unconnected-(E16A-O0-Pad12)") (class "Default")
      (node (ref "E16") (pin "12") (pinfunction "O0_12") (pintype "tri_state"))
    )
    (net (code "146") (name "unconnected-(E16A-O1-Pad11)") (class "Default")
      (node (ref "E16") (pin "11") (pinfunction "O1_11") (pintype "tri_state"))
    )
    (net (code "147") (name "unconnected-(E16A-O2-Pad10)") (class "Default")
      (node (ref "E16") (pin "10") (pinfunction "O2_10") (pintype "tri_state"))
    )
    (net (code "148") (name "unconnected-(E16A-O3-Pad9)") (class "Default")
      (node (ref "E16") (pin "9") (pinfunction "O3_9") (pintype "tri_state"))
    )
    (net (code "149") (name "unconnected-(E16A-~{G1}-Pad13)") (class "Default")
      (node (ref "E16") (pin "13") (pinfunction "~{G1}_13") (pintype "input"))
    )
    (net (code "150") (name "unconnected-(E16A-~{G2}-Pad14)") (class "Default")
      (node (ref "E16") (pin "14") (pinfunction "~{G2}_14") (pintype "input"))
    )
    (net (code "151") (name "unconnected-(E17A-A-Pad15)") (class "Default")
      (node (ref "E17") (pin "15") (pinfunction "A_15") (pintype "input"))
    )
    (net (code "152") (name "unconnected-(E17A-B-Pad14)") (class "Default")
      (node (ref "E17") (pin "14") (pinfunction "B_14") (pintype "input"))
    )
    (net (code "153") (name "unconnected-(E17A-C-Pad13)") (class "Default")
      (node (ref "E17") (pin "13") (pinfunction "C_13") (pintype "input"))
    )
    (net (code "154") (name "unconnected-(E17A-D-Pad12)") (class "Default")
      (node (ref "E17") (pin "12") (pinfunction "D_12") (pintype "input"))
    )
    (net (code "155") (name "unconnected-(E17A-O0-Pad1)") (class "Default")
      (node (ref "E17") (pin "1") (pinfunction "O0_1") (pintype "output"))
    )
    (net (code "156") (name "unconnected-(E17A-O1-Pad2)") (class "Default")
      (node (ref "E17") (pin "2") (pinfunction "O1_2") (pintype "output"))
    )
    (net (code "157") (name "unconnected-(E17A-O2-Pad3)") (class "Default")
      (node (ref "E17") (pin "3") (pinfunction "O2_3") (pintype "output"))
    )
    (net (code "158") (name "unconnected-(E17A-O3-Pad4)") (class "Default")
      (node (ref "E17") (pin "4") (pinfunction "O3_4") (pintype "output"))
    )
    (net (code "159") (name "unconnected-(E17A-O4-Pad5)") (class "Default")
      (node (ref "E17") (pin "5") (pinfunction "O4_5") (pintype "output"))
    )
    (net (code "160") (name "unconnected-(E17A-O5-Pad6)") (class "Default")
      (node (ref "E17") (pin "6") (pinfunction "O5_6") (pintype "output"))
    )
    (net (code "161") (name "unconnected-(E17A-O6-Pad7)") (class "Default")
      (node (ref "E17") (pin "7") (pinfunction "O6_7") (pintype "output"))
    )
    (net (code "162") (name "unconnected-(E17A-O7-Pad9)") (class "Default")
      (node (ref "E17") (pin "9") (pinfunction "O7_9") (pintype "output"))
    )
    (net (code "163") (name "unconnected-(E17A-O8-Pad10)") (class "Default")
      (node (ref "E17") (pin "10") (pinfunction "O8_10") (pintype "output"))
    )
    (net (code "164") (name "unconnected-(E17A-O9-Pad11)") (class "Default")
      (node (ref "E17") (pin "11") (pinfunction "O9_11") (pintype "output"))
    )
    (net (code "165") (name "unconnected-(E18A-A1-Pad2)") (class "Default")
      (node (ref "E18") (pin "2") (pinfunction "A1_2") (pintype "output"))
    )
    (net (code "166") (name "unconnected-(E18A-A2-Pad4)") (class "Default")
      (node (ref "E18") (pin "4") (pinfunction "A2_4") (pintype "output"))
    )
    (net (code "167") (name "unconnected-(E18A-A3-Pad6)") (class "Default")
      (node (ref "E18") (pin "6") (pinfunction "A3_6") (pintype "output"))
    )
    (net (code "168") (name "unconnected-(E18A-FORCE0-Pad7)") (class "Default")
      (node (ref "E18") (pin "7") (pinfunction "FORCE0_7") (pintype "input"))
    )
    (net (code "169") (name "unconnected-(E18A-Y1-Pad1)") (class "Default")
      (node (ref "E18") (pin "1") (pinfunction "Y1_1") (pintype "input"))
    )
    (net (code "170") (name "unconnected-(E18A-Y2-Pad3)") (class "Default")
      (node (ref "E18") (pin "3") (pinfunction "Y2_3") (pintype "input"))
    )
    (net (code "171") (name "unconnected-(E18A-Y3-Pad5)") (class "Default")
      (node (ref "E18") (pin "5") (pinfunction "Y3_5") (pintype "input"))
    )
    (net (code "172") (name "unconnected-(E18B-A1-Pad10)") (class "Default")
      (node (ref "E18") (pin "10") (pinfunction "A1_10") (pintype "output"))
    )
    (net (code "173") (name "unconnected-(E18B-A2-Pad12)") (class "Default")
      (node (ref "E18") (pin "12") (pinfunction "A2_12") (pintype "output"))
    )
    (net (code "174") (name "unconnected-(E18B-A3-Pad14)") (class "Default")
      (node (ref "E18") (pin "14") (pinfunction "A3_14") (pintype "output"))
    )
    (net (code "175") (name "unconnected-(E18B-FORCE0-Pad9)") (class "Default")
      (node (ref "E18") (pin "9") (pinfunction "FORCE0_9") (pintype "input"))
    )
    (net (code "176") (name "unconnected-(E18B-Y1-Pad11)") (class "Default")
      (node (ref "E18") (pin "11") (pinfunction "Y1_11") (pintype "input"))
    )
    (net (code "177") (name "unconnected-(E18B-Y2-Pad13)") (class "Default")
      (node (ref "E18") (pin "13") (pinfunction "Y2_13") (pintype "input"))
    )
    (net (code "178") (name "unconnected-(E18B-Y3-Pad15)") (class "Default")
      (node (ref "E18") (pin "15") (pinfunction "Y3_15") (pintype "input"))
    )
    (net (code "179") (name "unconnected-(E19A-1A-Pad2)") (class "Default")
      (node (ref "E19") (pin "2") (pinfunction "1A_2") (pintype "input"))
    )
    (net (code "180") (name "unconnected-(E19A-1B-Pad3)") (class "Default")
      (node (ref "E19") (pin "3") (pinfunction "1B_3") (pintype "input"))
    )
    (net (code "181") (name "unconnected-(E19A-1Y-Pad4)") (class "Default")
      (node (ref "E19") (pin "4") (pinfunction "1Y_4") (pintype "tri_state"))
    )
    (net (code "182") (name "unconnected-(E19A-2A-Pad5)") (class "Default")
      (node (ref "E19") (pin "5") (pinfunction "2A_5") (pintype "input"))
    )
    (net (code "183") (name "unconnected-(E19A-2B-Pad6)") (class "Default")
      (node (ref "E19") (pin "6") (pinfunction "2B_6") (pintype "input"))
    )
    (net (code "184") (name "unconnected-(E19A-2Y-Pad7)") (class "Default")
      (node (ref "E19") (pin "7") (pinfunction "2Y_7") (pintype "tri_state"))
    )
    (net (code "185") (name "unconnected-(E19A-3A-Pad11)") (class "Default")
      (node (ref "E19") (pin "11") (pinfunction "3A_11") (pintype "input"))
    )
    (net (code "186") (name "unconnected-(E19A-3B-Pad10)") (class "Default")
      (node (ref "E19") (pin "10") (pinfunction "3B_10") (pintype "input"))
    )
    (net (code "187") (name "unconnected-(E19A-3Y-Pad9)") (class "Default")
      (node (ref "E19") (pin "9") (pinfunction "3Y_9") (pintype "tri_state"))
    )
    (net (code "188") (name "unconnected-(E19A-4A-Pad14)") (class "Default")
      (node (ref "E19") (pin "14") (pinfunction "4A_14") (pintype "input"))
    )
    (net (code "189") (name "unconnected-(E19A-4B-Pad13)") (class "Default")
      (node (ref "E19") (pin "13") (pinfunction "4B_13") (pintype "input"))
    )
    (net (code "190") (name "unconnected-(E19A-4Y-Pad12)") (class "Default")
      (node (ref "E19") (pin "12") (pinfunction "4Y_12") (pintype "tri_state"))
    )
    (net (code "191") (name "unconnected-(E19A-G-Pad15)") (class "Default")
      (node (ref "E19") (pin "15") (pinfunction "G_15") (pintype "input"))
    )
    (net (code "192") (name "unconnected-(E19A-~{A}{slash}B-Pad1)") (class "Default")
      (node (ref "E19") (pin "1") (pinfunction "~{A}/B_1") (pintype "input"))
    )
    (net (code "193") (name "unconnected-(E20A-1A-Pad2)") (class "Default")
      (node (ref "E20") (pin "2") (pinfunction "1A_2") (pintype "input"))
    )
    (net (code "194") (name "unconnected-(E20A-1B-Pad3)") (class "Default")
      (node (ref "E20") (pin "3") (pinfunction "1B_3") (pintype "input"))
    )
    (net (code "195") (name "unconnected-(E20A-1Y-Pad4)") (class "Default")
      (node (ref "E20") (pin "4") (pinfunction "1Y_4") (pintype "tri_state"))
    )
    (net (code "196") (name "unconnected-(E20A-2A-Pad5)") (class "Default")
      (node (ref "E20") (pin "5") (pinfunction "2A_5") (pintype "input"))
    )
    (net (code "197") (name "unconnected-(E20A-2B-Pad6)") (class "Default")
      (node (ref "E20") (pin "6") (pinfunction "2B_6") (pintype "input"))
    )
    (net (code "198") (name "unconnected-(E20A-2Y-Pad7)") (class "Default")
      (node (ref "E20") (pin "7") (pinfunction "2Y_7") (pintype "tri_state"))
    )
    (net (code "199") (name "unconnected-(E20A-3A-Pad11)") (class "Default")
      (node (ref "E20") (pin "11") (pinfunction "3A_11") (pintype "input"))
    )
    (net (code "200") (name "unconnected-(E20A-3B-Pad10)") (class "Default")
      (node (ref "E20") (pin "10") (pinfunction "3B_10") (pintype "input"))
    )
    (net (code "201") (name "unconnected-(E20A-3Y-Pad9)") (class "Default")
      (node (ref "E20") (pin "9") (pinfunction "3Y_9") (pintype "tri_state"))
    )
    (net (code "202") (name "unconnected-(E20A-4A-Pad14)") (class "Default")
      (node (ref "E20") (pin "14") (pinfunction "4A_14") (pintype "input"))
    )
    (net (code "203") (name "unconnected-(E20A-4B-Pad13)") (class "Default")
      (node (ref "E20") (pin "13") (pinfunction "4B_13") (pintype "input"))
    )
    (net (code "204") (name "unconnected-(E20A-4Y-Pad12)") (class "Default")
      (node (ref "E20") (pin "12") (pinfunction "4Y_12") (pintype "tri_state"))
    )
    (net (code "205") (name "unconnected-(E20A-G-Pad15)") (class "Default")
      (node (ref "E20") (pin "15") (pinfunction "G_15") (pintype "input"))
    )
    (net (code "206") (name "unconnected-(E20A-~{A}{slash}B-Pad1)") (class "Default")
      (node (ref "E20") (pin "1") (pinfunction "~{A}/B_1") (pintype "input"))
    )
    (net (code "207") (name "unconnected-(E21A-A1-Pad2)") (class "Default")
      (node (ref "E21") (pin "2") (pinfunction "A1_2") (pintype "output"))
    )
    (net (code "208") (name "unconnected-(E21A-A2-Pad4)") (class "Default")
      (node (ref "E21") (pin "4") (pinfunction "A2_4") (pintype "output"))
    )
    (net (code "209") (name "unconnected-(E21A-A3-Pad6)") (class "Default")
      (node (ref "E21") (pin "6") (pinfunction "A3_6") (pintype "output"))
    )
    (net (code "210") (name "unconnected-(E21A-FORCE0-Pad7)") (class "Default")
      (node (ref "E21") (pin "7") (pinfunction "FORCE0_7") (pintype "input"))
    )
    (net (code "211") (name "unconnected-(E21A-Y1-Pad1)") (class "Default")
      (node (ref "E21") (pin "1") (pinfunction "Y1_1") (pintype "input"))
    )
    (net (code "212") (name "unconnected-(E21A-Y2-Pad3)") (class "Default")
      (node (ref "E21") (pin "3") (pinfunction "Y2_3") (pintype "input"))
    )
    (net (code "213") (name "unconnected-(E21A-Y3-Pad5)") (class "Default")
      (node (ref "E21") (pin "5") (pinfunction "Y3_5") (pintype "input"))
    )
    (net (code "214") (name "unconnected-(E22A-I0-Pad4)") (class "Default")
      (node (ref "E22") (pin "4") (pinfunction "I0_4") (pintype "input"))
    )
    (net (code "215") (name "unconnected-(E22A-I1-Pad5)") (class "Default")
      (node (ref "E22") (pin "5") (pinfunction "I1_5") (pintype "input"))
    )
    (net (code "216") (name "unconnected-(E22A-I2-Pad6)") (class "Default")
      (node (ref "E22") (pin "6") (pinfunction "I2_6") (pintype "input"))
    )
    (net (code "217") (name "unconnected-(E22A-I3-Pad9)") (class "Default")
      (node (ref "E22") (pin "9") (pinfunction "I3_9") (pintype "input"))
    )
    (net (code "218") (name "unconnected-(E22A-I4-Pad10)") (class "Default")
      (node (ref "E22") (pin "10") (pinfunction "I4_10") (pintype "input"))
    )
    (net (code "219") (name "unconnected-(E22A-I5-Pad11)") (class "Default")
      (node (ref "E22") (pin "11") (pinfunction "I5_11") (pintype "input"))
    )
    (net (code "220") (name "unconnected-(E22A-I6-Pad12)") (class "Default")
      (node (ref "E22") (pin "12") (pinfunction "I6_12") (pintype "input"))
    )
    (net (code "221") (name "unconnected-(E22A-O-Pad3)") (class "Default")
      (node (ref "E22") (pin "3") (pinfunction "O_3") (pintype "output"))
    )
    (net (code "222") (name "unconnected-(E23A-I0-Pad1)") (class "Default")
      (node (ref "E23") (pin "1") (pinfunction "I0_1") (pintype "input"))
    )
    (net (code "223") (name "unconnected-(E23A-I1-Pad2)") (class "Default")
      (node (ref "E23") (pin "2") (pinfunction "I1_2") (pintype "input"))
    )
    (net (code "224") (name "unconnected-(E23A-O-Pad3)") (class "Default")
      (node (ref "E23") (pin "3") (pinfunction "O_3") (pintype "output"))
    )
    (net (code "225") (name "unconnected-(E24A-I0-Pad1)") (class "Default")
      (node (ref "E24") (pin "1") (pinfunction "I0_1") (pintype "input"))
    )
    (net (code "226") (name "unconnected-(E24A-I1-Pad2)") (class "Default")
      (node (ref "E24") (pin "2") (pinfunction "I1_2") (pintype "input"))
    )
    (net (code "227") (name "unconnected-(E24A-O-Pad3)") (class "Default")
      (node (ref "E24") (pin "3") (pinfunction "O_3") (pintype "output"))
    )
    (net (code "228") (name "unconnected-(E25A-CLK-Pad7)") (class "Default")
      (node (ref "E25") (pin "7") (pinfunction "CLK_7") (pintype "input"))
    )
    (net (code "229") (name "unconnected-(E25A-CLR-Pad15)") (class "Default")
      (node (ref "E25") (pin "15") (pinfunction "CLR_15") (pintype "input"))
    )
    (net (code "230") (name "unconnected-(E25A-D1-Pad14)") (class "Default")
      (node (ref "E25") (pin "14") (pinfunction "D1_14") (pintype "input"))
    )
    (net (code "231") (name "unconnected-(E25A-D2-Pad13)") (class "Default")
      (node (ref "E25") (pin "13") (pinfunction "D2_13") (pintype "input"))
    )
    (net (code "232") (name "unconnected-(E25A-D3-Pad12)") (class "Default")
      (node (ref "E25") (pin "12") (pinfunction "D3_12") (pintype "input"))
    )
    (net (code "233") (name "unconnected-(E25A-D4-Pad11)") (class "Default")
      (node (ref "E25") (pin "11") (pinfunction "D4_11") (pintype "input"))
    )
    (net (code "234") (name "unconnected-(E25A-G1-Pad9)") (class "Default")
      (node (ref "E25") (pin "9") (pinfunction "G1_9") (pintype "input"))
    )
    (net (code "235") (name "unconnected-(E25A-G2-Pad10)") (class "Default")
      (node (ref "E25") (pin "10") (pinfunction "G2_10") (pintype "input"))
    )
    (net (code "236") (name "unconnected-(E25A-M-Pad1)") (class "Default")
      (node (ref "E25") (pin "1") (pinfunction "M_1") (pintype "input"))
    )
    (net (code "237") (name "unconnected-(E25A-N-Pad2)") (class "Default")
      (node (ref "E25") (pin "2") (pinfunction "N_2") (pintype "input"))
    )
    (net (code "238") (name "unconnected-(E25A-Q1-Pad3)") (class "Default")
      (node (ref "E25") (pin "3") (pinfunction "Q1_3") (pintype "tri_state"))
    )
    (net (code "239") (name "unconnected-(E25A-Q2-Pad4)") (class "Default")
      (node (ref "E25") (pin "4") (pinfunction "Q2_4") (pintype "tri_state"))
    )
    (net (code "240") (name "unconnected-(E25A-Q3-Pad5)") (class "Default")
      (node (ref "E25") (pin "5") (pinfunction "Q3_5") (pintype "tri_state"))
    )
    (net (code "241") (name "unconnected-(E25A-Q4-Pad6)") (class "Default")
      (node (ref "E25") (pin "6") (pinfunction "Q4_6") (pintype "tri_state"))
    )
    (net (code "242") (name "unconnected-(E26A-I0-Pad1)") (class "Default")
      (node (ref "E26") (pin "1") (pinfunction "I0_1") (pintype "input"))
    )
    (net (code "243") (name "unconnected-(E26A-I1-Pad2)") (class "Default")
      (node (ref "E26") (pin "2") (pinfunction "I1_2") (pintype "input"))
    )
    (net (code "244") (name "unconnected-(E26A-I2-Pad13)") (class "Default")
      (node (ref "E26") (pin "13") (pinfunction "I2_13") (pintype "input"))
    )
    (net (code "245") (name "unconnected-(E26A-O-Pad12)") (class "Default")
      (node (ref "E26") (pin "12") (pinfunction "O_12") (pintype "output"))
    )
    (net (code "246") (name "unconnected-(E27A-I0-Pad1)") (class "Default")
      (node (ref "E27") (pin "1") (pinfunction "I0_1") (pintype "input"))
    )
    (net (code "247") (name "unconnected-(E27A-I1-Pad2)") (class "Default")
      (node (ref "E27") (pin "2") (pinfunction "I1_2") (pintype "input"))
    )
    (net (code "248") (name "unconnected-(E27A-I2-Pad13)") (class "Default")
      (node (ref "E27") (pin "13") (pinfunction "I2_13") (pintype "input"))
    )
    (net (code "249") (name "unconnected-(E27A-O-Pad12)") (class "Default")
      (node (ref "E27") (pin "12") (pinfunction "O_12") (pintype "output"))
    )
    (net (code "250") (name "unconnected-(E28A-I0-Pad1)") (class "Default")
      (node (ref "E28") (pin "1") (pinfunction "I0_1") (pintype "input"))
    )
    (net (code "251") (name "unconnected-(E28A-I1-Pad2)") (class "Default")
      (node (ref "E28") (pin "2") (pinfunction "I1_2") (pintype "input"))
    )
    (net (code "252") (name "unconnected-(E28A-O-Pad3)") (class "Default")
      (node (ref "E28") (pin "3") (pinfunction "O_3") (pintype "output"))
    )
    (net (code "253") (name "unconnected-(E29A-I0-Pad1)") (class "Default")
      (node (ref "E29") (pin "1") (pinfunction "I0_1") (pintype "input"))
    )
    (net (code "254") (name "unconnected-(E29A-I1-Pad2)") (class "Default")
      (node (ref "E29") (pin "2") (pinfunction "I1_2") (pintype "input"))
    )
    (net (code "255") (name "unconnected-(E29A-I2-Pad13)") (class "Default")
      (node (ref "E29") (pin "13") (pinfunction "I2_13") (pintype "input"))
    )
    (net (code "256") (name "unconnected-(E29A-O-Pad12)") (class "Default")
      (node (ref "E29") (pin "12") (pinfunction "O_12") (pintype "output"))
    )
    (net (code "257") (name "unconnected-(E30A-1C0-Pad6)") (class "Default")
      (node (ref "E30") (pin "6") (pinfunction "1C0_6") (pintype "input"))
    )
    (net (code "258") (name "unconnected-(E30A-1C1-Pad5)") (class "Default")
      (node (ref "E30") (pin "5") (pinfunction "1C1_5") (pintype "input"))
    )
    (net (code "259") (name "unconnected-(E30A-1C2-Pad4)") (class "Default")
      (node (ref "E30") (pin "4") (pinfunction "1C2_4") (pintype "input"))
    )
    (net (code "260") (name "unconnected-(E30A-1C3-Pad3)") (class "Default")
      (node (ref "E30") (pin "3") (pinfunction "1C3_3") (pintype "input"))
    )
    (net (code "261") (name "unconnected-(E30A-1G-Pad1)") (class "Default")
      (node (ref "E30") (pin "1") (pinfunction "1G_1") (pintype "input"))
    )
    (net (code "262") (name "unconnected-(E30A-1Y-Pad7)") (class "Default")
      (node (ref "E30") (pin "7") (pinfunction "1Y_7") (pintype "output"))
    )
    (net (code "263") (name "unconnected-(E30A-2C0-Pad10)") (class "Default")
      (node (ref "E30") (pin "10") (pinfunction "2C0_10") (pintype "input"))
    )
    (net (code "264") (name "unconnected-(E30A-2C1-Pad11)") (class "Default")
      (node (ref "E30") (pin "11") (pinfunction "2C1_11") (pintype "input"))
    )
    (net (code "265") (name "unconnected-(E30A-2C2-Pad12)") (class "Default")
      (node (ref "E30") (pin "12") (pinfunction "2C2_12") (pintype "input"))
    )
    (net (code "266") (name "unconnected-(E30A-2C3-Pad13)") (class "Default")
      (node (ref "E30") (pin "13") (pinfunction "2C3_13") (pintype "input"))
    )
    (net (code "267") (name "unconnected-(E30A-2G-Pad15)") (class "Default")
      (node (ref "E30") (pin "15") (pinfunction "2G_15") (pintype "input"))
    )
    (net (code "268") (name "unconnected-(E30A-2Y-Pad9)") (class "Default")
      (node (ref "E30") (pin "9") (pinfunction "2Y_9") (pintype "output"))
    )
    (net (code "269") (name "unconnected-(E30A-A-Pad14)") (class "Default")
      (node (ref "E30") (pin "14") (pinfunction "A_14") (pintype "input"))
    )
    (net (code "270") (name "unconnected-(E30A-B-Pad2)") (class "Default")
      (node (ref "E30") (pin "2") (pinfunction "B_2") (pintype "input"))
    )
    (net (code "271") (name "unconnected-(E31A-I0-Pad1)") (class "Default")
      (node (ref "E31") (pin "1") (pinfunction "I0_1") (pintype "input"))
    )
    (net (code "272") (name "unconnected-(E31A-I1-Pad2)") (class "Default")
      (node (ref "E31") (pin "2") (pinfunction "I1_2") (pintype "input"))
    )
    (net (code "273") (name "unconnected-(E31A-I2-Pad13)") (class "Default")
      (node (ref "E31") (pin "13") (pinfunction "I2_13") (pintype "input"))
    )
    (net (code "274") (name "unconnected-(E31A-O-Pad12)") (class "Default")
      (node (ref "E31") (pin "12") (pinfunction "O_12") (pintype "output"))
    )
    (net (code "275") (name "unconnected-(E32A-I-Pad1)") (class "Default")
      (node (ref "E32") (pin "1") (pinfunction "I_1") (pintype "input"))
    )
    (net (code "276") (name "unconnected-(E32A-O-Pad2)") (class "Default")
      (node (ref "E32") (pin "2") (pinfunction "O_2") (pintype "output"))
    )
    (net (code "277") (name "unconnected-(E33A-I0-Pad1)") (class "Default")
      (node (ref "E33") (pin "1") (pinfunction "I0_1") (pintype "input"))
    )
    (net (code "278") (name "unconnected-(E33A-I1-Pad2)") (class "Default")
      (node (ref "E33") (pin "2") (pinfunction "I1_2") (pintype "input"))
    )
    (net (code "279") (name "unconnected-(E33A-I2-Pad13)") (class "Default")
      (node (ref "E33") (pin "13") (pinfunction "I2_13") (pintype "input"))
    )
    (net (code "280") (name "unconnected-(E33A-O-Pad12)") (class "Default")
      (node (ref "E33") (pin "12") (pinfunction "O_12") (pintype "output"))
    )
    (net (code "281") (name "unconnected-(E34A-I0-Pad1)") (class "Default")
      (node (ref "E34") (pin "1") (pinfunction "I0_1") (pintype "input"))
    )
    (net (code "282") (name "unconnected-(E34A-I1-Pad2)") (class "Default")
      (node (ref "E34") (pin "2") (pinfunction "I1_2") (pintype "input"))
    )
    (net (code "283") (name "unconnected-(E34A-I2-Pad13)") (class "Default")
      (node (ref "E34") (pin "13") (pinfunction "I2_13") (pintype "input"))
    )
    (net (code "284") (name "unconnected-(E34A-O-Pad12)") (class "Default")
      (node (ref "E34") (pin "12") (pinfunction "O_12") (pintype "output"))
    )
    (net (code "285") (name "unconnected-(E35A-A0-Pad10)") (class "Default")
      (node (ref "E35") (pin "10") (pinfunction "A0_10") (pintype "input"))
    )
    (net (code "286") (name "unconnected-(E35A-A1-Pad11)") (class "Default")
      (node (ref "E35") (pin "11") (pinfunction "A1_11") (pintype "input"))
    )
    (net (code "287") (name "unconnected-(E35A-A2-Pad12)") (class "Default")
      (node (ref "E35") (pin "12") (pinfunction "A2_12") (pintype "input"))
    )
    (net (code "288") (name "unconnected-(E35A-A3-Pad13)") (class "Default")
      (node (ref "E35") (pin "13") (pinfunction "A3_13") (pintype "input"))
    )
    (net (code "289") (name "unconnected-(E35A-A4-Pad14)") (class "Default")
      (node (ref "E35") (pin "14") (pinfunction "A4_14") (pintype "input"))
    )
    (net (code "290") (name "unconnected-(E35A-O0-Pad1)") (class "Default")
      (node (ref "E35") (pin "1") (pinfunction "O0_1") (pintype "tri_state"))
    )
    (net (code "291") (name "unconnected-(E35A-O1-Pad2)") (class "Default")
      (node (ref "E35") (pin "2") (pinfunction "O1_2") (pintype "tri_state"))
    )
    (net (code "292") (name "unconnected-(E35A-O2-Pad3)") (class "Default")
      (node (ref "E35") (pin "3") (pinfunction "O2_3") (pintype "tri_state"))
    )
    (net (code "293") (name "unconnected-(E35A-O3-Pad4)") (class "Default")
      (node (ref "E35") (pin "4") (pinfunction "O3_4") (pintype "tri_state"))
    )
    (net (code "294") (name "unconnected-(E35A-O4-Pad5)") (class "Default")
      (node (ref "E35") (pin "5") (pinfunction "O4_5") (pintype "tri_state"))
    )
    (net (code "295") (name "unconnected-(E35A-O5-Pad6)") (class "Default")
      (node (ref "E35") (pin "6") (pinfunction "O5_6") (pintype "tri_state"))
    )
    (net (code "296") (name "unconnected-(E35A-O6-Pad7)") (class "Default")
      (node (ref "E35") (pin "7") (pinfunction "O6_7") (pintype "tri_state"))
    )
    (net (code "297") (name "unconnected-(E35A-O7-Pad9)") (class "Default")
      (node (ref "E35") (pin "9") (pinfunction "O7_9") (pintype "tri_state"))
    )
    (net (code "298") (name "unconnected-(E35A-~{G}-Pad15)") (class "Default")
      (node (ref "E35") (pin "15") (pinfunction "~{G}_15") (pintype "input"))
    )
    (net (code "299") (name "unconnected-(E36A-A1-Pad2)") (class "Default")
      (node (ref "E36") (pin "2") (pinfunction "A1_2") (pintype "output"))
    )
    (net (code "300") (name "unconnected-(E36A-A2-Pad4)") (class "Default")
      (node (ref "E36") (pin "4") (pinfunction "A2_4") (pintype "output"))
    )
    (net (code "301") (name "unconnected-(E36A-A3-Pad6)") (class "Default")
      (node (ref "E36") (pin "6") (pinfunction "A3_6") (pintype "output"))
    )
    (net (code "302") (name "unconnected-(E36A-FORCE0-Pad7)") (class "Default")
      (node (ref "E36") (pin "7") (pinfunction "FORCE0_7") (pintype "input"))
    )
    (net (code "303") (name "unconnected-(E36A-Y1-Pad1)") (class "Default")
      (node (ref "E36") (pin "1") (pinfunction "Y1_1") (pintype "input"))
    )
    (net (code "304") (name "unconnected-(E36A-Y2-Pad3)") (class "Default")
      (node (ref "E36") (pin "3") (pinfunction "Y2_3") (pintype "input"))
    )
    (net (code "305") (name "unconnected-(E36A-Y3-Pad5)") (class "Default")
      (node (ref "E36") (pin "5") (pinfunction "Y3_5") (pintype "input"))
    )
    (net (code "306") (name "unconnected-(E37A-I0-Pad1)") (class "Default")
      (node (ref "E37") (pin "1") (pinfunction "I0_1") (pintype "input"))
    )
    (net (code "307") (name "unconnected-(E37A-I1-Pad2)") (class "Default")
      (node (ref "E37") (pin "2") (pinfunction "I1_2") (pintype "input"))
    )
    (net (code "308") (name "unconnected-(E37A-O-Pad3)") (class "Default")
      (node (ref "E37") (pin "3") (pinfunction "O_3") (pintype "output"))
    )
    (net (code "309") (name "unconnected-(E38A-I0-Pad2)") (class "Default")
      (node (ref "E38") (pin "2") (pinfunction "I0_2") (pintype "input"))
    )
    (net (code "310") (name "unconnected-(E38A-I1-Pad3)") (class "Default")
      (node (ref "E38") (pin "3") (pinfunction "I1_3") (pintype "input"))
    )
    (net (code "311") (name "unconnected-(E38A-O-Pad1)") (class "Default")
      (node (ref "E38") (pin "1") (pinfunction "O_1") (pintype "output"))
    )
    (net (code "312") (name "unconnected-(E39C-I0-Pad1)") (class "Default")
      (node (ref "E39") (pin "1") (pinfunction "I0_1") (pintype "input"))
    )
    (net (code "313") (name "unconnected-(E39C-I1-Pad2)") (class "Default")
      (node (ref "E39") (pin "2") (pinfunction "I1_2") (pintype "input"))
    )
    (net (code "314") (name "unconnected-(E39C-I2-Pad4)") (class "Default")
      (node (ref "E39") (pin "4") (pinfunction "I2_4") (pintype "input"))
    )
    (net (code "315") (name "unconnected-(E39C-I3-Pad5)") (class "Default")
      (node (ref "E39") (pin "5") (pinfunction "I3_5") (pintype "input"))
    )
    (net (code "316") (name "unconnected-(E39C-O-Pad6)") (class "Default")
      (node (ref "E39") (pin "6") (pinfunction "O_6") (pintype "output"))
    )
    (net (code "317") (name "unconnected-(E40A-A-Pad15)") (class "Default")
      (node (ref "E40") (pin "15") (pinfunction "A_15") (pintype "input"))
    )
    (net (code "318") (name "unconnected-(E40A-B-Pad14)") (class "Default")
      (node (ref "E40") (pin "14") (pinfunction "B_14") (pintype "input"))
    )
    (net (code "319") (name "unconnected-(E40A-C-Pad13)") (class "Default")
      (node (ref "E40") (pin "13") (pinfunction "C_13") (pintype "input"))
    )
    (net (code "320") (name "unconnected-(E40A-D-Pad12)") (class "Default")
      (node (ref "E40") (pin "12") (pinfunction "D_12") (pintype "input"))
    )
    (net (code "321") (name "unconnected-(E40A-O0-Pad1)") (class "Default")
      (node (ref "E40") (pin "1") (pinfunction "O0_1") (pintype "output"))
    )
    (net (code "322") (name "unconnected-(E40A-O1-Pad2)") (class "Default")
      (node (ref "E40") (pin "2") (pinfunction "O1_2") (pintype "output"))
    )
    (net (code "323") (name "unconnected-(E40A-O2-Pad3)") (class "Default")
      (node (ref "E40") (pin "3") (pinfunction "O2_3") (pintype "output"))
    )
    (net (code "324") (name "unconnected-(E40A-O3-Pad4)") (class "Default")
      (node (ref "E40") (pin "4") (pinfunction "O3_4") (pintype "output"))
    )
    (net (code "325") (name "unconnected-(E40A-O4-Pad5)") (class "Default")
      (node (ref "E40") (pin "5") (pinfunction "O4_5") (pintype "output"))
    )
    (net (code "326") (name "unconnected-(E40A-O5-Pad6)") (class "Default")
      (node (ref "E40") (pin "6") (pinfunction "O5_6") (pintype "output"))
    )
    (net (code "327") (name "unconnected-(E40A-O6-Pad7)") (class "Default")
      (node (ref "E40") (pin "7") (pinfunction "O6_7") (pintype "output"))
    )
    (net (code "328") (name "unconnected-(E40A-O7-Pad9)") (class "Default")
      (node (ref "E40") (pin "9") (pinfunction "O7_9") (pintype "output"))
    )
    (net (code "329") (name "unconnected-(E40A-O8-Pad10)") (class "Default")
      (node (ref "E40") (pin "10") (pinfunction "O8_10") (pintype "output"))
    )
    (net (code "330") (name "unconnected-(E40A-O9-Pad11)") (class "Default")
      (node (ref "E40") (pin "11") (pinfunction "O9_11") (pintype "output"))
    )
    (net (code "331") (name "unconnected-(E41A-A1-Pad2)") (class "Default")
      (node (ref "E41") (pin "2") (pinfunction "A1_2") (pintype "output"))
    )
    (net (code "332") (name "unconnected-(E41A-A2-Pad4)") (class "Default")
      (node (ref "E41") (pin "4") (pinfunction "A2_4") (pintype "output"))
    )
    (net (code "333") (name "unconnected-(E41A-A3-Pad6)") (class "Default")
      (node (ref "E41") (pin "6") (pinfunction "A3_6") (pintype "output"))
    )
    (net (code "334") (name "unconnected-(E41A-FORCE0-Pad7)") (class "Default")
      (node (ref "E41") (pin "7") (pinfunction "FORCE0_7") (pintype "input"))
    )
    (net (code "335") (name "unconnected-(E41A-Y1-Pad1)") (class "Default")
      (node (ref "E41") (pin "1") (pinfunction "Y1_1") (pintype "input"))
    )
    (net (code "336") (name "unconnected-(E41A-Y2-Pad3)") (class "Default")
      (node (ref "E41") (pin "3") (pinfunction "Y2_3") (pintype "input"))
    )
    (net (code "337") (name "unconnected-(E41A-Y3-Pad5)") (class "Default")
      (node (ref "E41") (pin "5") (pinfunction "Y3_5") (pintype "input"))
    )
    (net (code "338") (name "unconnected-(E42A-I-Pad1)") (class "Default")
      (node (ref "E42") (pin "1") (pinfunction "I_1") (pintype "input"))
    )
    (net (code "339") (name "unconnected-(E42A-O-Pad2)") (class "Default")
      (node (ref "E42") (pin "2") (pinfunction "O_2") (pintype "output"))
    )
    (net (code "340") (name "unconnected-(E43A-I-Pad1)") (class "Default")
      (node (ref "E43") (pin "1") (pinfunction "I_1") (pintype "input"))
    )
    (net (code "341") (name "unconnected-(E43A-O-Pad2)") (class "Default")
      (node (ref "E43") (pin "2") (pinfunction "O_2") (pintype "output"))
    )
    (net (code "342") (name "unconnected-(E44A-CLK-Pad7)") (class "Default")
      (node (ref "E44") (pin "7") (pinfunction "CLK_7") (pintype "input"))
    )
    (net (code "343") (name "unconnected-(E44A-CLR-Pad15)") (class "Default")
      (node (ref "E44") (pin "15") (pinfunction "CLR_15") (pintype "input"))
    )
    (net (code "344") (name "unconnected-(E44A-D1-Pad14)") (class "Default")
      (node (ref "E44") (pin "14") (pinfunction "D1_14") (pintype "input"))
    )
    (net (code "345") (name "unconnected-(E44A-D2-Pad13)") (class "Default")
      (node (ref "E44") (pin "13") (pinfunction "D2_13") (pintype "input"))
    )
    (net (code "346") (name "unconnected-(E44A-D3-Pad12)") (class "Default")
      (node (ref "E44") (pin "12") (pinfunction "D3_12") (pintype "input"))
    )
    (net (code "347") (name "unconnected-(E44A-D4-Pad11)") (class "Default")
      (node (ref "E44") (pin "11") (pinfunction "D4_11") (pintype "input"))
    )
    (net (code "348") (name "unconnected-(E44A-G1-Pad9)") (class "Default")
      (node (ref "E44") (pin "9") (pinfunction "G1_9") (pintype "input"))
    )
    (net (code "349") (name "unconnected-(E44A-G2-Pad10)") (class "Default")
      (node (ref "E44") (pin "10") (pinfunction "G2_10") (pintype "input"))
    )
    (net (code "350") (name "unconnected-(E44A-M-Pad1)") (class "Default")
      (node (ref "E44") (pin "1") (pinfunction "M_1") (pintype "input"))
    )
    (net (code "351") (name "unconnected-(E44A-N-Pad2)") (class "Default")
      (node (ref "E44") (pin "2") (pinfunction "N_2") (pintype "input"))
    )
    (net (code "352") (name "unconnected-(E44A-Q1-Pad3)") (class "Default")
      (node (ref "E44") (pin "3") (pinfunction "Q1_3") (pintype "tri_state"))
    )
    (net (code "353") (name "unconnected-(E44A-Q2-Pad4)") (class "Default")
      (node (ref "E44") (pin "4") (pinfunction "Q2_4") (pintype "tri_state"))
    )
    (net (code "354") (name "unconnected-(E44A-Q3-Pad5)") (class "Default")
      (node (ref "E44") (pin "5") (pinfunction "Q3_5") (pintype "tri_state"))
    )
    (net (code "355") (name "unconnected-(E44A-Q4-Pad6)") (class "Default")
      (node (ref "E44") (pin "6") (pinfunction "Q4_6") (pintype "tri_state"))
    )
    (net (code "356") (name "unconnected-(E45A-I0-Pad1)") (class "Default")
      (node (ref "E45") (pin "1") (pinfunction "I0_1") (pintype "input"))
    )
    (net (code "357") (name "unconnected-(E45A-I1-Pad2)") (class "Default")
      (node (ref "E45") (pin "2") (pinfunction "I1_2") (pintype "input"))
    )
    (net (code "358") (name "unconnected-(E45A-O-Pad3)") (class "Default")
      (node (ref "E45") (pin "3") (pinfunction "O_3") (pintype "output"))
    )
    (net (code "359") (name "unconnected-(E46A-I0-Pad2)") (class "Default")
      (node (ref "E46") (pin "2") (pinfunction "I0_2") (pintype "input"))
    )
    (net (code "360") (name "unconnected-(E46A-I1-Pad3)") (class "Default")
      (node (ref "E46") (pin "3") (pinfunction "I1_3") (pintype "input"))
    )
    (net (code "361") (name "unconnected-(E46A-O-Pad1)") (class "Default")
      (node (ref "E46") (pin "1") (pinfunction "O_1") (pintype "open_collector"))
    )
    (net (code "362") (name "unconnected-(E47A-I0-Pad2)") (class "Default")
      (node (ref "E47") (pin "2") (pinfunction "I0_2") (pintype "input"))
    )
    (net (code "363") (name "unconnected-(E47A-I1-Pad3)") (class "Default")
      (node (ref "E47") (pin "3") (pinfunction "I1_3") (pintype "input"))
    )
    (net (code "364") (name "unconnected-(E47A-O-Pad1)") (class "Default")
      (node (ref "E47") (pin "1") (pinfunction "O_1") (pintype "open_collector"))
    )
    (net (code "365") (name "unconnected-(E48A-I-Pad1)") (class "Default")
      (node (ref "E48") (pin "1") (pinfunction "I_1") (pintype "input"))
    )
    (net (code "366") (name "unconnected-(E48A-O-Pad2)") (class "Default")
      (node (ref "E48") (pin "2") (pinfunction "O_2") (pintype "open_collector"))
    )
    (net (code "367") (name "unconnected-(E49A-CLK-Pad7)") (class "Default")
      (node (ref "E49") (pin "7") (pinfunction "CLK_7") (pintype "input"))
    )
    (net (code "368") (name "unconnected-(E49A-CLR-Pad15)") (class "Default")
      (node (ref "E49") (pin "15") (pinfunction "CLR_15") (pintype "input"))
    )
    (net (code "369") (name "unconnected-(E49A-D1-Pad14)") (class "Default")
      (node (ref "E49") (pin "14") (pinfunction "D1_14") (pintype "input"))
    )
    (net (code "370") (name "unconnected-(E49A-D2-Pad13)") (class "Default")
      (node (ref "E49") (pin "13") (pinfunction "D2_13") (pintype "input"))
    )
    (net (code "371") (name "unconnected-(E49A-D3-Pad12)") (class "Default")
      (node (ref "E49") (pin "12") (pinfunction "D3_12") (pintype "input"))
    )
    (net (code "372") (name "unconnected-(E49A-D4-Pad11)") (class "Default")
      (node (ref "E49") (pin "11") (pinfunction "D4_11") (pintype "input"))
    )
    (net (code "373") (name "unconnected-(E49A-G1-Pad9)") (class "Default")
      (node (ref "E49") (pin "9") (pinfunction "G1_9") (pintype "input"))
    )
    (net (code "374") (name "unconnected-(E49A-G2-Pad10)") (class "Default")
      (node (ref "E49") (pin "10") (pinfunction "G2_10") (pintype "input"))
    )
    (net (code "375") (name "unconnected-(E49A-M-Pad1)") (class "Default")
      (node (ref "E49") (pin "1") (pinfunction "M_1") (pintype "input"))
    )
    (net (code "376") (name "unconnected-(E49A-N-Pad2)") (class "Default")
      (node (ref "E49") (pin "2") (pinfunction "N_2") (pintype "input"))
    )
    (net (code "377") (name "unconnected-(E49A-Q1-Pad3)") (class "Default")
      (node (ref "E49") (pin "3") (pinfunction "Q1_3") (pintype "tri_state"))
    )
    (net (code "378") (name "unconnected-(E49A-Q2-Pad4)") (class "Default")
      (node (ref "E49") (pin "4") (pinfunction "Q2_4") (pintype "tri_state"))
    )
    (net (code "379") (name "unconnected-(E49A-Q3-Pad5)") (class "Default")
      (node (ref "E49") (pin "5") (pinfunction "Q3_5") (pintype "tri_state"))
    )
    (net (code "380") (name "unconnected-(E49A-Q4-Pad6)") (class "Default")
      (node (ref "E49") (pin "6") (pinfunction "Q4_6") (pintype "tri_state"))
    )
    (net (code "381") (name "unconnected-(E50C-I0-Pad1)") (class "Default")
      (node (ref "E50") (pin "1") (pinfunction "I0_1") (pintype "input"))
    )
    (net (code "382") (name "unconnected-(E50C-I1-Pad2)") (class "Default")
      (node (ref "E50") (pin "2") (pinfunction "I1_2") (pintype "input"))
    )
    (net (code "383") (name "unconnected-(E50C-I2-Pad4)") (class "Default")
      (node (ref "E50") (pin "4") (pinfunction "I2_4") (pintype "input"))
    )
    (net (code "384") (name "unconnected-(E50C-I3-Pad5)") (class "Default")
      (node (ref "E50") (pin "5") (pinfunction "I3_5") (pintype "input"))
    )
    (net (code "385") (name "unconnected-(E50C-O-Pad6)") (class "Default")
      (node (ref "E50") (pin "6") (pinfunction "O_6") (pintype "output"))
    )
    (net (code "386") (name "unconnected-(E51A-I0-Pad2)") (class "Default")
      (node (ref "E51") (pin "2") (pinfunction "I0_2") (pintype "input"))
    )
    (net (code "387") (name "unconnected-(E51A-I1-Pad3)") (class "Default")
      (node (ref "E51") (pin "3") (pinfunction "I1_3") (pintype "input"))
    )
    (net (code "388") (name "unconnected-(E51A-O-Pad1)") (class "Default")
      (node (ref "E51") (pin "1") (pinfunction "O_1") (pintype "open_collector"))
    )
    (net (code "389") (name "unconnected-(E52A-I-Pad1)") (class "Default")
      (node (ref "E52") (pin "1") (pinfunction "I_1") (pintype "input"))
    )
    (net (code "390") (name "unconnected-(E52A-O-Pad2)") (class "Default")
      (node (ref "E52") (pin "2") (pinfunction "O_2") (pintype "open_collector"))
    )
    (net (code "391") (name "unconnected-(E53A-I0-Pad1)") (class "Default")
      (node (ref "E53") (pin "1") (pinfunction "I0_1") (pintype "input"))
    )
    (net (code "392") (name "unconnected-(E53A-I1-Pad2)") (class "Default")
      (node (ref "E53") (pin "2") (pinfunction "I1_2") (pintype "input"))
    )
    (net (code "393") (name "unconnected-(E53A-I2-Pad13)") (class "Default")
      (node (ref "E53") (pin "13") (pinfunction "I2_13") (pintype "input"))
    )
    (net (code "394") (name "unconnected-(E53A-O-Pad12)") (class "Default")
      (node (ref "E53") (pin "12") (pinfunction "O_12") (pintype "output"))
    )
    (net (code "395") (name "unconnected-(E54A-I-Pad1)") (class "Default")
      (node (ref "E54") (pin "1") (pinfunction "I_1") (pintype "input"))
    )
    (net (code "396") (name "unconnected-(E54A-O-Pad2)") (class "Default")
      (node (ref "E54") (pin "2") (pinfunction "O_2") (pintype "output"))
    )
    (net (code "397") (name "unconnected-(E55A-I0-Pad1)") (class "Default")
      (node (ref "E55") (pin "1") (pinfunction "I0_1") (pintype "input"))
    )
    (net (code "398") (name "unconnected-(E55A-I1-Pad2)") (class "Default")
      (node (ref "E55") (pin "2") (pinfunction "I1_2") (pintype "input"))
    )
    (net (code "399") (name "unconnected-(E55A-O-Pad3)") (class "Default")
      (node (ref "E55") (pin "3") (pinfunction "O_3") (pintype "output"))
    )
    (net (code "400") (name "unconnected-(E56A-I0-Pad2)") (class "Default")
      (node (ref "E56") (pin "2") (pinfunction "I0_2") (pintype "input"))
    )
    (net (code "401") (name "unconnected-(E56A-I1-Pad3)") (class "Default")
      (node (ref "E56") (pin "3") (pinfunction "I1_3") (pintype "input"))
    )
    (net (code "402") (name "unconnected-(E56A-O-Pad1)") (class "Default")
      (node (ref "E56") (pin "1") (pinfunction "O_1") (pintype "open_collector"))
    )
    (net (code "403") (name "unconnected-(E57A-I0-Pad2)") (class "Default")
      (node (ref "E57") (pin "2") (pinfunction "I0_2") (pintype "input"))
    )
    (net (code "404") (name "unconnected-(E57A-I1-Pad3)") (class "Default")
      (node (ref "E57") (pin "3") (pinfunction "I1_3") (pintype "input"))
    )
    (net (code "405") (name "unconnected-(E57A-O-Pad1)") (class "Default")
      (node (ref "E57") (pin "1") (pinfunction "O_1") (pintype "open_collector"))
    )
    (net (code "406") (name "unconnected-(E58A-I0-Pad2)") (class "Default")
      (node (ref "E58") (pin "2") (pinfunction "I0_2") (pintype "input"))
    )
    (net (code "407") (name "unconnected-(E58A-I1-Pad3)") (class "Default")
      (node (ref "E58") (pin "3") (pinfunction "I1_3") (pintype "input"))
    )
    (net (code "408") (name "unconnected-(E58A-O-Pad1)") (class "Default")
      (node (ref "E58") (pin "1") (pinfunction "O_1") (pintype "open_collector"))
    )
    (net (code "409") (name "unconnected-(E59A-I-Pad1)") (class "Default")
      (node (ref "E59") (pin "1") (pinfunction "I_1") (pintype "input"))
    )
    (net (code "410") (name "unconnected-(E59A-O-Pad2)") (class "Default")
      (node (ref "E59") (pin "2") (pinfunction "O_2") (pintype "output"))
    )
    (net (code "411") (name "unconnected-(E60A-I0-Pad2)") (class "Default")
      (node (ref "E60") (pin "2") (pinfunction "I0_2") (pintype "input"))
    )
    (net (code "412") (name "unconnected-(E60A-I1-Pad3)") (class "Default")
      (node (ref "E60") (pin "3") (pinfunction "I1_3") (pintype "input"))
    )
    (net (code "413") (name "unconnected-(E60A-O-Pad1)") (class "Default")
      (node (ref "E60") (pin "1") (pinfunction "O_1") (pintype "output"))
    )
    (net (code "414") (name "unconnected-(E61A-CLK-Pad9)") (class "Default")
      (node (ref "E61") (pin "9") (pinfunction "CLK_9") (pintype "input"))
    )
    (net (code "415") (name "unconnected-(E61A-CLR-Pad1)") (class "Default")
      (node (ref "E61") (pin "1") (pinfunction "CLR_1") (pintype "input"))
    )
    (net (code "416") (name "unconnected-(E61A-D1-Pad4)") (class "Default")
      (node (ref "E61") (pin "4") (pinfunction "D1_4") (pintype "input"))
    )
    (net (code "417") (name "unconnected-(E61A-D2-Pad5)") (class "Default")
      (node (ref "E61") (pin "5") (pinfunction "D2_5") (pintype "input"))
    )
    (net (code "418") (name "unconnected-(E61A-D3-Pad12)") (class "Default")
      (node (ref "E61") (pin "12") (pinfunction "D3_12") (pintype "input"))
    )
    (net (code "419") (name "unconnected-(E61A-D4-Pad13)") (class "Default")
      (node (ref "E61") (pin "13") (pinfunction "D4_13") (pintype "input"))
    )
    (net (code "420") (name "unconnected-(E61A-Q1-Pad2)") (class "Default")
      (node (ref "E61") (pin "2") (pinfunction "Q1_2") (pintype "output"))
    )
    (net (code "421") (name "unconnected-(E61A-Q2-Pad7)") (class "Default")
      (node (ref "E61") (pin "7") (pinfunction "Q2_7") (pintype "output"))
    )
    (net (code "422") (name "unconnected-(E61A-Q3-Pad10)") (class "Default")
      (node (ref "E61") (pin "10") (pinfunction "Q3_10") (pintype "output"))
    )
    (net (code "423") (name "unconnected-(E61A-Q4-Pad15)") (class "Default")
      (node (ref "E61") (pin "15") (pinfunction "Q4_15") (pintype "output"))
    )
    (net (code "424") (name "unconnected-(E61A-~{Q1}-Pad3)") (class "Default")
      (node (ref "E61") (pin "3") (pinfunction "~{Q1}_3") (pintype "output"))
    )
    (net (code "425") (name "unconnected-(E61A-~{Q2}-Pad6)") (class "Default")
      (node (ref "E61") (pin "6") (pinfunction "~{Q2}_6") (pintype "output"))
    )
    (net (code "426") (name "unconnected-(E61A-~{Q3}-Pad11)") (class "Default")
      (node (ref "E61") (pin "11") (pinfunction "~{Q3}_11") (pintype "output"))
    )
    (net (code "427") (name "unconnected-(E61A-~{Q4}-Pad14)") (class "Default")
      (node (ref "E61") (pin "14") (pinfunction "~{Q4}_14") (pintype "output"))
    )
    (net (code "428") (name "unconnected-(E62A-I0-Pad2)") (class "Default")
      (node (ref "E62") (pin "2") (pinfunction "I0_2") (pintype "input"))
    )
    (net (code "429") (name "unconnected-(E62A-I1-Pad3)") (class "Default")
      (node (ref "E62") (pin "3") (pinfunction "I1_3") (pintype "input"))
    )
    (net (code "430") (name "unconnected-(E62A-O-Pad1)") (class "Default")
      (node (ref "E62") (pin "1") (pinfunction "O_1") (pintype "output"))
    )
    (net (code "431") (name "unconnected-(E63A-CLK-Pad3)") (class "Default")
      (node (ref "E63") (pin "3") (pinfunction "CLK_3") (pintype "input"))
    )
    (net (code "432") (name "unconnected-(E63A-CLR-Pad1)") (class "Default")
      (node (ref "E63") (pin "1") (pinfunction "CLR_1") (pintype "input"))
    )
    (net (code "433") (name "unconnected-(E63A-D-Pad2)") (class "Default")
      (node (ref "E63") (pin "2") (pinfunction "D_2") (pintype "input"))
    )
    (net (code "434") (name "unconnected-(E63A-PRE-Pad4)") (class "Default")
      (node (ref "E63") (pin "4") (pinfunction "PRE_4") (pintype "input"))
    )
    (net (code "435") (name "unconnected-(E63A-Q-Pad5)") (class "Default")
      (node (ref "E63") (pin "5") (pinfunction "Q_5") (pintype "output"))
    )
    (net (code "436") (name "unconnected-(E63A-~{Q}-Pad6)") (class "Default")
      (node (ref "E63") (pin "6") (pinfunction "~{Q}_6") (pintype "output"))
    )
    (net (code "437") (name "unconnected-(E63B-CLK-Pad11)") (class "Default")
      (node (ref "E63") (pin "11") (pinfunction "CLK_11") (pintype "input"))
    )
    (net (code "438") (name "unconnected-(E63B-CLR-Pad13)") (class "Default")
      (node (ref "E63") (pin "13") (pinfunction "CLR_13") (pintype "input"))
    )
    (net (code "439") (name "unconnected-(E63B-D-Pad12)") (class "Default")
      (node (ref "E63") (pin "12") (pinfunction "D_12") (pintype "input"))
    )
    (net (code "440") (name "unconnected-(E63B-PRE-Pad10)") (class "Default")
      (node (ref "E63") (pin "10") (pinfunction "PRE_10") (pintype "input"))
    )
    (net (code "441") (name "unconnected-(E63B-Q-Pad9)") (class "Default")
      (node (ref "E63") (pin "9") (pinfunction "Q_9") (pintype "output"))
    )
    (net (code "442") (name "unconnected-(E63B-~{Q}-Pad8)") (class "Default")
      (node (ref "E63") (pin "8") (pinfunction "~{Q}_8") (pintype "output"))
    )
    (net (code "443") (name "unconnected-(E64A-I0-Pad1)") (class "Default")
      (node (ref "E64") (pin "1") (pinfunction "I0_1") (pintype "input"))
    )
    (net (code "444") (name "unconnected-(E64A-I1-Pad2)") (class "Default")
      (node (ref "E64") (pin "2") (pinfunction "I1_2") (pintype "input"))
    )
    (net (code "445") (name "unconnected-(E64A-O-Pad3)") (class "Default")
      (node (ref "E64") (pin "3") (pinfunction "O_3") (pintype "output"))
    )
    (net (code "446") (name "unconnected-(E65A-CLK-Pad3)") (class "Default")
      (node (ref "E65") (pin "3") (pinfunction "CLK_3") (pintype "input"))
    )
    (net (code "447") (name "unconnected-(E65A-CLR-Pad1)") (class "Default")
      (node (ref "E65") (pin "1") (pinfunction "CLR_1") (pintype "input"))
    )
    (net (code "448") (name "unconnected-(E65A-D-Pad2)") (class "Default")
      (node (ref "E65") (pin "2") (pinfunction "D_2") (pintype "input"))
    )
    (net (code "449") (name "unconnected-(E65A-PRE-Pad4)") (class "Default")
      (node (ref "E65") (pin "4") (pinfunction "PRE_4") (pintype "input"))
    )
    (net (code "450") (name "unconnected-(E65A-Q-Pad5)") (class "Default")
      (node (ref "E65") (pin "5") (pinfunction "Q_5") (pintype "output"))
    )
    (net (code "451") (name "unconnected-(E65A-~{Q}-Pad6)") (class "Default")
      (node (ref "E65") (pin "6") (pinfunction "~{Q}_6") (pintype "output"))
    )
    (net (code "452") (name "unconnected-(E65B-CLK-Pad11)") (class "Default")
      (node (ref "E65") (pin "11") (pinfunction "CLK_11") (pintype "input"))
    )
    (net (code "453") (name "unconnected-(E65B-CLR-Pad13)") (class "Default")
      (node (ref "E65") (pin "13") (pinfunction "CLR_13") (pintype "input"))
    )
    (net (code "454") (name "unconnected-(E65B-D-Pad12)") (class "Default")
      (node (ref "E65") (pin "12") (pinfunction "D_12") (pintype "input"))
    )
    (net (code "455") (name "unconnected-(E65B-PRE-Pad10)") (class "Default")
      (node (ref "E65") (pin "10") (pinfunction "PRE_10") (pintype "input"))
    )
    (net (code "456") (name "unconnected-(E65B-Q-Pad9)") (class "Default")
      (node (ref "E65") (pin "9") (pinfunction "Q_9") (pintype "output"))
    )
    (net (code "457") (name "unconnected-(E65B-~{Q}-Pad8)") (class "Default")
      (node (ref "E65") (pin "8") (pinfunction "~{Q}_8") (pintype "output"))
    )
    (net (code "458") (name "unconnected-(E66A-I-Pad1)") (class "Default")
      (node (ref "E66") (pin "1") (pinfunction "I_1") (pintype "input"))
    )
    (net (code "459") (name "unconnected-(E66A-O-Pad2)") (class "Default")
      (node (ref "E66") (pin "2") (pinfunction "O_2") (pintype "output"))
    )
    (net (code "460") (name "unconnected-(E67A-I0-Pad1)") (class "Default")
      (node (ref "E67") (pin "1") (pinfunction "I0_1") (pintype "input"))
    )
    (net (code "461") (name "unconnected-(E67A-I1-Pad2)") (class "Default")
      (node (ref "E67") (pin "2") (pinfunction "I1_2") (pintype "input"))
    )
    (net (code "462") (name "unconnected-(E67A-O-Pad3)") (class "Default")
      (node (ref "E67") (pin "3") (pinfunction "O_3") (pintype "output"))
    )
    (net (code "463") (name "unconnected-(E68A-I-Pad1)") (class "Default")
      (node (ref "E68") (pin "1") (pinfunction "I_1") (pintype "input"))
    )
    (net (code "464") (name "unconnected-(E68A-O-Pad2)") (class "Default")
      (node (ref "E68") (pin "2") (pinfunction "O_2") (pintype "output"))
    )
    (net (code "465") (name "unconnected-(E69A-I0-Pad1)") (class "Default")
      (node (ref "E69") (pin "1") (pinfunction "I0_1") (pintype "input"))
    )
    (net (code "466") (name "unconnected-(E69A-I1-Pad2)") (class "Default")
      (node (ref "E69") (pin "2") (pinfunction "I1_2") (pintype "input"))
    )
    (net (code "467") (name "unconnected-(E69A-O-Pad3)") (class "Default")
      (node (ref "E69") (pin "3") (pinfunction "O_3") (pintype "output"))
    )
    (net (code "468") (name "unconnected-(E70A-I0-Pad1)") (class "Default")
      (node (ref "E70") (pin "1") (pinfunction "I0_1") (pintype "input"))
    )
    (net (code "469") (name "unconnected-(E70A-I1-Pad2)") (class "Default")
      (node (ref "E70") (pin "2") (pinfunction "I1_2") (pintype "input"))
    )
    (net (code "470") (name "unconnected-(E70A-O-Pad3)") (class "Default")
      (node (ref "E70") (pin "3") (pinfunction "O_3") (pintype "output"))
    )
    (net (code "471") (name "unconnected-(E71A-CLK-Pad9)") (class "Default")
      (node (ref "E71") (pin "9") (pinfunction "CLK_9") (pintype "input"))
    )
    (net (code "472") (name "unconnected-(E71A-CLR-Pad1)") (class "Default")
      (node (ref "E71") (pin "1") (pinfunction "CLR_1") (pintype "input"))
    )
    (net (code "473") (name "unconnected-(E71A-D1-Pad4)") (class "Default")
      (node (ref "E71") (pin "4") (pinfunction "D1_4") (pintype "input"))
    )
    (net (code "474") (name "unconnected-(E71A-D2-Pad5)") (class "Default")
      (node (ref "E71") (pin "5") (pinfunction "D2_5") (pintype "input"))
    )
    (net (code "475") (name "unconnected-(E71A-D3-Pad12)") (class "Default")
      (node (ref "E71") (pin "12") (pinfunction "D3_12") (pintype "input"))
    )
    (net (code "476") (name "unconnected-(E71A-D4-Pad13)") (class "Default")
      (node (ref "E71") (pin "13") (pinfunction "D4_13") (pintype "input"))
    )
    (net (code "477") (name "unconnected-(E71A-Q1-Pad2)") (class "Default")
      (node (ref "E71") (pin "2") (pinfunction "Q1_2") (pintype "output"))
    )
    (net (code "478") (name "unconnected-(E71A-Q2-Pad7)") (class "Default")
      (node (ref "E71") (pin "7") (pinfunction "Q2_7") (pintype "output"))
    )
    (net (code "479") (name "unconnected-(E71A-Q3-Pad10)") (class "Default")
      (node (ref "E71") (pin "10") (pinfunction "Q3_10") (pintype "output"))
    )
    (net (code "480") (name "unconnected-(E71A-Q4-Pad15)") (class "Default")
      (node (ref "E71") (pin "15") (pinfunction "Q4_15") (pintype "output"))
    )
    (net (code "481") (name "unconnected-(E71A-~{Q1}-Pad3)") (class "Default")
      (node (ref "E71") (pin "3") (pinfunction "~{Q1}_3") (pintype "output"))
    )
    (net (code "482") (name "unconnected-(E71A-~{Q2}-Pad6)") (class "Default")
      (node (ref "E71") (pin "6") (pinfunction "~{Q2}_6") (pintype "output"))
    )
    (net (code "483") (name "unconnected-(E71A-~{Q3}-Pad11)") (class "Default")
      (node (ref "E71") (pin "11") (pinfunction "~{Q3}_11") (pintype "output"))
    )
    (net (code "484") (name "unconnected-(E71A-~{Q4}-Pad14)") (class "Default")
      (node (ref "E71") (pin "14") (pinfunction "~{Q4}_14") (pintype "output"))
    )
    (net (code "485") (name "unconnected-(E72A-I0-Pad1)") (class "Default")
      (node (ref "E72") (pin "1") (pinfunction "I0_1") (pintype "input"))
    )
    (net (code "486") (name "unconnected-(E72A-I1-Pad2)") (class "Default")
      (node (ref "E72") (pin "2") (pinfunction "I1_2") (pintype "input"))
    )
    (net (code "487") (name "unconnected-(E72A-O-Pad3)") (class "Default")
      (node (ref "E72") (pin "3") (pinfunction "O_3") (pintype "output"))
    )
    (net (code "488") (name "unconnected-(E73A-I0-Pad1)") (class "Default")
      (node (ref "E73") (pin "1") (pinfunction "I0_1") (pintype "input"))
    )
    (net (code "489") (name "unconnected-(E73A-I1-Pad2)") (class "Default")
      (node (ref "E73") (pin "2") (pinfunction "I1_2") (pintype "input"))
    )
    (net (code "490") (name "unconnected-(E73A-I2-Pad13)") (class "Default")
      (node (ref "E73") (pin "13") (pinfunction "I2_13") (pintype "input"))
    )
    (net (code "491") (name "unconnected-(E73A-O-Pad12)") (class "Default")
      (node (ref "E73") (pin "12") (pinfunction "O_12") (pintype "output"))
    )
    (net (code "492") (name "unconnected-(E74A-I0-Pad1)") (class "Default")
      (node (ref "E74") (pin "1") (pinfunction "I0_1") (pintype "input"))
    )
    (net (code "493") (name "unconnected-(E74A-I1-Pad2)") (class "Default")
      (node (ref "E74") (pin "2") (pinfunction "I1_2") (pintype "input"))
    )
    (net (code "494") (name "unconnected-(E74A-O-Pad3)") (class "Default")
      (node (ref "E74") (pin "3") (pinfunction "O_3") (pintype "output"))
    )
    (net (code "495") (name "unconnected-(E75A-I0-Pad1)") (class "Default")
      (node (ref "E75") (pin "1") (pinfunction "I0_1") (pintype "input"))
    )
    (net (code "496") (name "unconnected-(E75A-I1-Pad2)") (class "Default")
      (node (ref "E75") (pin "2") (pinfunction "I1_2") (pintype "input"))
    )
    (net (code "497") (name "unconnected-(E75A-O-Pad3)") (class "Default")
      (node (ref "E75") (pin "3") (pinfunction "O_3") (pintype "output"))
    )
    (net (code "498") (name "unconnected-(E76A-A0-Pad5)") (class "Default")
      (node (ref "E76") (pin "5") (pinfunction "A0_5") (pintype "input"))
    )
    (net (code "499") (name "unconnected-(E76A-A1-Pad6)") (class "Default")
      (node (ref "E76") (pin "6") (pinfunction "A1_6") (pintype "input"))
    )
    (net (code "500") (name "unconnected-(E76A-A2-Pad7)") (class "Default")
      (node (ref "E76") (pin "7") (pinfunction "A2_7") (pintype "input"))
    )
    (net (code "501") (name "unconnected-(E76A-A3-Pad4)") (class "Default")
      (node (ref "E76") (pin "4") (pinfunction "A3_4") (pintype "input"))
    )
    (net (code "502") (name "unconnected-(E76A-A4-Pad3)") (class "Default")
      (node (ref "E76") (pin "3") (pinfunction "A4_3") (pintype "input"))
    )
    (net (code "503") (name "unconnected-(E76A-A5-Pad2)") (class "Default")
      (node (ref "E76") (pin "2") (pinfunction "A5_2") (pintype "input"))
    )
    (net (code "504") (name "unconnected-(E76A-A6-Pad1)") (class "Default")
      (node (ref "E76") (pin "1") (pinfunction "A6_1") (pintype "input"))
    )
    (net (code "505") (name "unconnected-(E76A-A7-Pad15)") (class "Default")
      (node (ref "E76") (pin "15") (pinfunction "A7_15") (pintype "input"))
    )
    (net (code "506") (name "unconnected-(E76A-O0-Pad12)") (class "Default")
      (node (ref "E76") (pin "12") (pinfunction "O0_12") (pintype "tri_state"))
    )
    (net (code "507") (name "unconnected-(E76A-O1-Pad11)") (class "Default")
      (node (ref "E76") (pin "11") (pinfunction "O1_11") (pintype "tri_state"))
    )
    (net (code "508") (name "unconnected-(E76A-O2-Pad10)") (class "Default")
      (node (ref "E76") (pin "10") (pinfunction "O2_10") (pintype "tri_state"))
    )
    (net (code "509") (name "unconnected-(E76A-O3-Pad9)") (class "Default")
      (node (ref "E76") (pin "9") (pinfunction "O3_9") (pintype "tri_state"))
    )
    (net (code "510") (name "unconnected-(E76A-~{G1}-Pad13)") (class "Default")
      (node (ref "E76") (pin "13") (pinfunction "~{G1}_13") (pintype "input"))
    )
    (net (code "511") (name "unconnected-(E76A-~{G2}-Pad14)") (class "Default")
      (node (ref "E76") (pin "14") (pinfunction "~{G2}_14") (pintype "input"))
    )
    (net (code "512") (name "unconnected-(E77A-I0-Pad1)") (class "Default")
      (node (ref "E77") (pin "1") (pinfunction "I0_1") (pintype "input"))
    )
    (net (code "513") (name "unconnected-(E77A-I1-Pad2)") (class "Default")
      (node (ref "E77") (pin "2") (pinfunction "I1_2") (pintype "input"))
    )
    (net (code "514") (name "unconnected-(E77A-I2-Pad13)") (class "Default")
      (node (ref "E77") (pin "13") (pinfunction "I2_13") (pintype "input"))
    )
    (net (code "515") (name "unconnected-(E77A-O-Pad12)") (class "Default")
      (node (ref "E77") (pin "12") (pinfunction "O_12") (pintype "output"))
    )
    (net (code "516") (name "unconnected-(E78A-A-Pad1)") (class "Default")
      (node (ref "E78") (pin "1") (pinfunction "A_1") (pintype "input"))
    )
    (net (code "517") (name "unconnected-(E78A-B-Pad2)") (class "Default")
      (node (ref "E78") (pin "2") (pinfunction "B_2") (pintype "input"))
    )
    (net (code "518") (name "unconnected-(E78A-CLK-Pad8)") (class "Default")
      (node (ref "E78") (pin "8") (pinfunction "CLK_8") (pintype "input"))
    )
    (net (code "519") (name "unconnected-(E78A-CLR-Pad9)") (class "Default")
      (node (ref "E78") (pin "9") (pinfunction "CLR_9") (pintype "input"))
    )
    (net (code "520") (name "unconnected-(E78A-QA-Pad3)") (class "Default")
      (node (ref "E78") (pin "3") (pinfunction "QA_3") (pintype "output"))
    )
    (net (code "521") (name "unconnected-(E78A-QB-Pad4)") (class "Default")
      (node (ref "E78") (pin "4") (pinfunction "QB_4") (pintype "output"))
    )
    (net (code "522") (name "unconnected-(E78A-QC-Pad5)") (class "Default")
      (node (ref "E78") (pin "5") (pinfunction "QC_5") (pintype "output"))
    )
    (net (code "523") (name "unconnected-(E78A-QD-Pad6)") (class "Default")
      (node (ref "E78") (pin "6") (pinfunction "QD_6") (pintype "output"))
    )
    (net (code "524") (name "unconnected-(E78A-QE-Pad10)") (class "Default")
      (node (ref "E78") (pin "10") (pinfunction "QE_10") (pintype "output"))
    )
    (net (code "525") (name "unconnected-(E78A-QF-Pad11)") (class "Default")
      (node (ref "E78") (pin "11") (pinfunction "QF_11") (pintype "output"))
    )
    (net (code "526") (name "unconnected-(E78A-QG-Pad12)") (class "Default")
      (node (ref "E78") (pin "12") (pinfunction "QG_12") (pintype "output"))
    )
    (net (code "527") (name "unconnected-(E78A-QH-Pad13)") (class "Default")
      (node (ref "E78") (pin "13") (pinfunction "QH_13") (pintype "output"))
    )
    (net (code "528") (name "unconnected-(E79A-CLK-Pad3)") (class "Default")
      (node (ref "E79") (pin "3") (pinfunction "CLK_3") (pintype "input"))
    )
    (net (code "529") (name "unconnected-(E79A-CLR-Pad1)") (class "Default")
      (node (ref "E79") (pin "1") (pinfunction "CLR_1") (pintype "input"))
    )
    (net (code "530") (name "unconnected-(E79A-D-Pad2)") (class "Default")
      (node (ref "E79") (pin "2") (pinfunction "D_2") (pintype "input"))
    )
    (net (code "531") (name "unconnected-(E79A-PRE-Pad4)") (class "Default")
      (node (ref "E79") (pin "4") (pinfunction "PRE_4") (pintype "input"))
    )
    (net (code "532") (name "unconnected-(E79A-Q-Pad5)") (class "Default")
      (node (ref "E79") (pin "5") (pinfunction "Q_5") (pintype "output"))
    )
    (net (code "533") (name "unconnected-(E79A-~{Q}-Pad6)") (class "Default")
      (node (ref "E79") (pin "6") (pinfunction "~{Q}_6") (pintype "output"))
    )
    (net (code "534") (name "unconnected-(E79B-CLK-Pad11)") (class "Default")
      (node (ref "E79") (pin "11") (pinfunction "CLK_11") (pintype "input"))
    )
    (net (code "535") (name "unconnected-(E79B-CLR-Pad13)") (class "Default")
      (node (ref "E79") (pin "13") (pinfunction "CLR_13") (pintype "input"))
    )
    (net (code "536") (name "unconnected-(E79B-D-Pad12)") (class "Default")
      (node (ref "E79") (pin "12") (pinfunction "D_12") (pintype "input"))
    )
    (net (code "537") (name "unconnected-(E79B-PRE-Pad10)") (class "Default")
      (node (ref "E79") (pin "10") (pinfunction "PRE_10") (pintype "input"))
    )
    (net (code "538") (name "unconnected-(E79B-Q-Pad9)") (class "Default")
      (node (ref "E79") (pin "9") (pinfunction "Q_9") (pintype "output"))
    )
    (net (code "539") (name "unconnected-(E79B-~{Q}-Pad8)") (class "Default")
      (node (ref "E79") (pin "8") (pinfunction "~{Q}_8") (pintype "output"))
    )
    (net (code "540") (name "unconnected-(E80A-CLK-Pad3)") (class "Default")
      (node (ref "E80") (pin "3") (pinfunction "CLK_3") (pintype "input"))
    )
    (net (code "541") (name "unconnected-(E80A-CLR-Pad1)") (class "Default")
      (node (ref "E80") (pin "1") (pinfunction "CLR_1") (pintype "input"))
    )
    (net (code "542") (name "unconnected-(E80A-D-Pad2)") (class "Default")
      (node (ref "E80") (pin "2") (pinfunction "D_2") (pintype "input"))
    )
    (net (code "543") (name "unconnected-(E80A-PRE-Pad4)") (class "Default")
      (node (ref "E80") (pin "4") (pinfunction "PRE_4") (pintype "input"))
    )
    (net (code "544") (name "unconnected-(E80A-Q-Pad5)") (class "Default")
      (node (ref "E80") (pin "5") (pinfunction "Q_5") (pintype "output"))
    )
    (net (code "545") (name "unconnected-(E80A-~{Q}-Pad6)") (class "Default")
      (node (ref "E80") (pin "6") (pinfunction "~{Q}_6") (pintype "output"))
    )
    (net (code "546") (name "unconnected-(E80B-CLK-Pad11)") (class "Default")
      (node (ref "E80") (pin "11") (pinfunction "CLK_11") (pintype "input"))
    )
    (net (code "547") (name "unconnected-(E80B-CLR-Pad13)") (class "Default")
      (node (ref "E80") (pin "13") (pinfunction "CLR_13") (pintype "input"))
    )
    (net (code "548") (name "unconnected-(E80B-D-Pad12)") (class "Default")
      (node (ref "E80") (pin "12") (pinfunction "D_12") (pintype "input"))
    )
    (net (code "549") (name "unconnected-(E80B-PRE-Pad10)") (class "Default")
      (node (ref "E80") (pin "10") (pinfunction "PRE_10") (pintype "input"))
    )
    (net (code "550") (name "unconnected-(E80B-Q-Pad9)") (class "Default")
      (node (ref "E80") (pin "9") (pinfunction "Q_9") (pintype "output"))
    )
    (net (code "551") (name "unconnected-(E80B-~{Q}-Pad8)") (class "Default")
      (node (ref "E80") (pin "8") (pinfunction "~{Q}_8") (pintype "output"))
    )
    (net (code "552") (name "unconnected-(E81A-A0-Pad5)") (class "Default")
      (node (ref "E81") (pin "5") (pinfunction "A0_5") (pintype "input"))
    )
    (net (code "553") (name "unconnected-(E81A-A1-Pad6)") (class "Default")
      (node (ref "E81") (pin "6") (pinfunction "A1_6") (pintype "input"))
    )
    (net (code "554") (name "unconnected-(E81A-A2-Pad7)") (class "Default")
      (node (ref "E81") (pin "7") (pinfunction "A2_7") (pintype "input"))
    )
    (net (code "555") (name "unconnected-(E81A-A3-Pad4)") (class "Default")
      (node (ref "E81") (pin "4") (pinfunction "A3_4") (pintype "input"))
    )
    (net (code "556") (name "unconnected-(E81A-A4-Pad3)") (class "Default")
      (node (ref "E81") (pin "3") (pinfunction "A4_3") (pintype "input"))
    )
    (net (code "557") (name "unconnected-(E81A-A5-Pad2)") (class "Default")
      (node (ref "E81") (pin "2") (pinfunction "A5_2") (pintype "input"))
    )
    (net (code "558") (name "unconnected-(E81A-A6-Pad1)") (class "Default")
      (node (ref "E81") (pin "1") (pinfunction "A6_1") (pintype "input"))
    )
    (net (code "559") (name "unconnected-(E81A-A7-Pad15)") (class "Default")
      (node (ref "E81") (pin "15") (pinfunction "A7_15") (pintype "input"))
    )
    (net (code "560") (name "unconnected-(E81A-O0-Pad12)") (class "Default")
      (node (ref "E81") (pin "12") (pinfunction "O0_12") (pintype "tri_state"))
    )
    (net (code "561") (name "unconnected-(E81A-O1-Pad11)") (class "Default")
      (node (ref "E81") (pin "11") (pinfunction "O1_11") (pintype "tri_state"))
    )
    (net (code "562") (name "unconnected-(E81A-O2-Pad10)") (class "Default")
      (node (ref "E81") (pin "10") (pinfunction "O2_10") (pintype "tri_state"))
    )
    (net (code "563") (name "unconnected-(E81A-O3-Pad9)") (class "Default")
      (node (ref "E81") (pin "9") (pinfunction "O3_9") (pintype "tri_state"))
    )
    (net (code "564") (name "unconnected-(E81A-~{G1}-Pad13)") (class "Default")
      (node (ref "E81") (pin "13") (pinfunction "~{G1}_13") (pintype "input"))
    )
    (net (code "565") (name "unconnected-(E81A-~{G2}-Pad14)") (class "Default")
      (node (ref "E81") (pin "14") (pinfunction "~{G2}_14") (pintype "input"))
    )
    (net (code "566") (name "unconnected-(E82A-CL-Pad2)") (class "Default")
      (node (ref "E82") (pin "2") (pinfunction "CL_2") (pintype "input"))
    )
    (net (code "567") (name "unconnected-(E82A-CLK-Pad1)") (class "Default")
      (node (ref "E82") (pin "1") (pinfunction "CLK_1") (pintype "input"))
    )
    (net (code "568") (name "unconnected-(E82A-J-Pad14)") (class "Default")
      (node (ref "E82") (pin "14") (pinfunction "J_14") (pintype "input"))
    )
    (net (code "569") (name "unconnected-(E82A-K-Pad3)") (class "Default")
      (node (ref "E82") (pin "3") (pinfunction "K_3") (pintype "input"))
    )
    (net (code "570") (name "unconnected-(E82A-Q-Pad12)") (class "Default")
      (node (ref "E82") (pin "12") (pinfunction "Q_12") (pintype "output"))
    )
    (net (code "571") (name "unconnected-(E82A-~{Q}-Pad13)") (class "Default")
      (node (ref "E82") (pin "13") (pinfunction "~{Q}_13") (pintype "output"))
    )
    (net (code "572") (name "unconnected-(E83-Pad1)") (class "Default")
      (node (ref "E83") (pin "1") (pinfunction "1_1") (pintype "passive"))
    )
    (net (code "573") (name "unconnected-(E83-Pad2)") (class "Default")
      (node (ref "E83") (pin "2") (pinfunction "2_2") (pintype "passive"))
    )
    (net (code "574") (name "unconnected-(E83-Pad3)") (class "Default")
      (node (ref "E83") (pin "3") (pinfunction "3_3") (pintype "passive"))
    )
    (net (code "575") (name "unconnected-(E83-Pad4)") (class "Default")
      (node (ref "E83") (pin "4") (pinfunction "4_4") (pintype "passive"))
    )
    (net (code "576") (name "unconnected-(E83-Pad5)") (class "Default")
      (node (ref "E83") (pin "5") (pinfunction "5_5") (pintype "passive"))
    )
    (net (code "577") (name "unconnected-(E83-Pad6)") (class "Default")
      (node (ref "E83") (pin "6") (pinfunction "6_6") (pintype "passive"))
    )
    (net (code "578") (name "unconnected-(E83-Pad7)") (class "Default")
      (node (ref "E83") (pin "7") (pinfunction "7_7") (pintype "passive"))
    )
    (net (code "579") (name "unconnected-(E83-Pad8)") (class "Default")
      (node (ref "E83") (pin "8") (pinfunction "8_8") (pintype "passive"))
    )
    (net (code "580") (name "unconnected-(E83-Pad9)") (class "Default")
      (node (ref "E83") (pin "9") (pinfunction "9_9") (pintype "passive"))
    )
    (net (code "581") (name "unconnected-(E83-Pad10)") (class "Default")
      (node (ref "E83") (pin "10") (pinfunction "10_10") (pintype "passive"))
    )
    (net (code "582") (name "unconnected-(E83-Pad11)") (class "Default")
      (node (ref "E83") (pin "11") (pinfunction "11_11") (pintype "passive"))
    )
    (net (code "583") (name "unconnected-(E83-Pad12)") (class "Default")
      (node (ref "E83") (pin "12") (pinfunction "12_12") (pintype "passive"))
    )
    (net (code "584") (name "unconnected-(E83-Pad13)") (class "Default")
      (node (ref "E83") (pin "13") (pinfunction "13_13") (pintype "passive"))
    )
    (net (code "585") (name "unconnected-(E83-Pad14)") (class "Default")
      (node (ref "E83") (pin "14") (pinfunction "14_14") (pintype "passive"))
    )
    (net (code "586") (name "unconnected-(E83-Pad15)") (class "Default")
      (node (ref "E83") (pin "15") (pinfunction "15_15") (pintype "passive"))
    )
    (net (code "587") (name "unconnected-(E83-Pad16)") (class "Default")
      (node (ref "E83") (pin "16") (pinfunction "16_16") (pintype "passive"))
    )
    (net (code "588") (name "unconnected-(E84A-CLK-Pad3)") (class "Default")
      (node (ref "E84") (pin "3") (pinfunction "CLK_3") (pintype "input"))
    )
    (net (code "589") (name "unconnected-(E84A-CLR-Pad1)") (class "Default")
      (node (ref "E84") (pin "1") (pinfunction "CLR_1") (pintype "input"))
    )
    (net (code "590") (name "unconnected-(E84A-D-Pad2)") (class "Default")
      (node (ref "E84") (pin "2") (pinfunction "D_2") (pintype "input"))
    )
    (net (code "591") (name "unconnected-(E84A-PRE-Pad4)") (class "Default")
      (node (ref "E84") (pin "4") (pinfunction "PRE_4") (pintype "input"))
    )
    (net (code "592") (name "unconnected-(E84A-Q-Pad5)") (class "Default")
      (node (ref "E84") (pin "5") (pinfunction "Q_5") (pintype "output"))
    )
    (net (code "593") (name "unconnected-(E84A-~{Q}-Pad6)") (class "Default")
      (node (ref "E84") (pin "6") (pinfunction "~{Q}_6") (pintype "output"))
    )
    (net (code "594") (name "unconnected-(E84B-CLK-Pad11)") (class "Default")
      (node (ref "E84") (pin "11") (pinfunction "CLK_11") (pintype "input"))
    )
    (net (code "595") (name "unconnected-(E84B-CLR-Pad13)") (class "Default")
      (node (ref "E84") (pin "13") (pinfunction "CLR_13") (pintype "input"))
    )
    (net (code "596") (name "unconnected-(E84B-D-Pad12)") (class "Default")
      (node (ref "E84") (pin "12") (pinfunction "D_12") (pintype "input"))
    )
    (net (code "597") (name "unconnected-(E84B-PRE-Pad10)") (class "Default")
      (node (ref "E84") (pin "10") (pinfunction "PRE_10") (pintype "input"))
    )
    (net (code "598") (name "unconnected-(E84B-Q-Pad9)") (class "Default")
      (node (ref "E84") (pin "9") (pinfunction "Q_9") (pintype "output"))
    )
    (net (code "599") (name "unconnected-(E84B-~{Q}-Pad8)") (class "Default")
      (node (ref "E84") (pin "8") (pinfunction "~{Q}_8") (pintype "output"))
    )
    (net (code "600") (name "unconnected-(E85A-I0-Pad4)") (class "Default")
      (node (ref "E85") (pin "4") (pinfunction "I0_4") (pintype "input"))
    )
    (net (code "601") (name "unconnected-(E85A-I1-Pad10)") (class "Default")
      (node (ref "E85") (pin "10") (pinfunction "I1_10") (pintype "input"))
    )
    (net (code "602") (name "unconnected-(E85A-I2-Pad3)") (class "Default")
      (node (ref "E85") (pin "3") (pinfunction "I2_3") (pintype "input"))
    )
    (net (code "603") (name "unconnected-(E85A-I3-Pad11)") (class "Default")
      (node (ref "E85") (pin "11") (pinfunction "I3_11") (pintype "input"))
    )
    (net (code "604") (name "unconnected-(E85A-Q0-Pad5)") (class "Default")
      (node (ref "E85") (pin "5") (pinfunction "Q0_5") (pintype "output"))
    )
    (net (code "605") (name "unconnected-(E85A-Q1-Pad9)") (class "Default")
      (node (ref "E85") (pin "9") (pinfunction "Q1_9") (pintype "output"))
    )
    (net (code "606") (name "unconnected-(E85A-Q2-Pad2)") (class "Default")
      (node (ref "E85") (pin "2") (pinfunction "Q2_2") (pintype "output"))
    )
    (net (code "607") (name "unconnected-(E85A-Q3-Pad12)") (class "Default")
      (node (ref "E85") (pin "12") (pinfunction "Q3_12") (pintype "output"))
    )
    (net (code "608") (name "unconnected-(E85A-{slash}2-Pad8)") (class "Default")
      (node (ref "E85") (pin "8") (pinfunction "/2_8") (pintype "bidirectional"))
    )
    (net (code "609") (name "unconnected-(E85A-{slash}8-Pad6)") (class "Default")
      (node (ref "E85") (pin "6") (pinfunction "/8_6") (pintype "bidirectional"))
    )
    (net (code "610") (name "unconnected-(E85A-~{LD}-Pad1)") (class "Default")
      (node (ref "E85") (pin "1") (pinfunction "~{LD}_1") (pintype "input"))
    )
    (net (code "611") (name "unconnected-(E85A-~{MR}-Pad13)") (class "Default")
      (node (ref "E85") (pin "13") (pinfunction "~{MR}_13") (pintype "input"))
    )
    (net (code "612") (name "unconnected-(E86A-A0-Pad1)") (class "Default")
      (node (ref "E86") (pin "1") (pinfunction "A0_1") (pintype "input"))
    )
    (net (code "613") (name "unconnected-(E86A-A1-Pad6)") (class "Default")
      (node (ref "E86") (pin "6") (pinfunction "A1_6") (pintype "input"))
    )
    (net (code "614") (name "unconnected-(E86A-A2-Pad10)") (class "Default")
      (node (ref "E86") (pin "10") (pinfunction "A2_10") (pintype "input"))
    )
    (net (code "615") (name "unconnected-(E86A-A3-Pad15)") (class "Default")
      (node (ref "E86") (pin "15") (pinfunction "A3_15") (pintype "input"))
    )
    (net (code "616") (name "unconnected-(E86A-B0-Pad2)") (class "Default")
      (node (ref "E86") (pin "2") (pinfunction "B0_2") (pintype "input"))
    )
    (net (code "617") (name "unconnected-(E86A-B1-Pad5)") (class "Default")
      (node (ref "E86") (pin "5") (pinfunction "B1_5") (pintype "input"))
    )
    (net (code "618") (name "unconnected-(E86A-B2-Pad11)") (class "Default")
      (node (ref "E86") (pin "11") (pinfunction "B2_11") (pintype "input"))
    )
    (net (code "619") (name "unconnected-(E86A-B3-Pad14)") (class "Default")
      (node (ref "E86") (pin "14") (pinfunction "B3_14") (pintype "input"))
    )
    (net (code "620") (name "unconnected-(E86A-F0-Pad3)") (class "Default")
      (node (ref "E86") (pin "3") (pinfunction "F0_3") (pintype "output"))
    )
    (net (code "621") (name "unconnected-(E86A-F1-Pad4)") (class "Default")
      (node (ref "E86") (pin "4") (pinfunction "F1_4") (pintype "output"))
    )
    (net (code "622") (name "unconnected-(E86A-F2-Pad12)") (class "Default")
      (node (ref "E86") (pin "12") (pinfunction "F2_12") (pintype "output"))
    )
    (net (code "623") (name "unconnected-(E86A-F3-Pad13)") (class "Default")
      (node (ref "E86") (pin "13") (pinfunction "F3_13") (pintype "output"))
    )
    (net (code "624") (name "unconnected-(E86A-S0-Pad9)") (class "Default")
      (node (ref "E86") (pin "9") (pinfunction "S0_9") (pintype "input"))
    )
    (net (code "625") (name "unconnected-(E86A-S1-Pad7)") (class "Default")
      (node (ref "E86") (pin "7") (pinfunction "S1_7") (pintype "input"))
    )
    (net (code "626") (name "unconnected-(E87A-CLK-Pad3)") (class "Default")
      (node (ref "E87") (pin "3") (pinfunction "CLK_3") (pintype "input"))
    )
    (net (code "627") (name "unconnected-(E87A-CLR-Pad1)") (class "Default")
      (node (ref "E87") (pin "1") (pinfunction "CLR_1") (pintype "input"))
    )
    (net (code "628") (name "unconnected-(E87A-D-Pad2)") (class "Default")
      (node (ref "E87") (pin "2") (pinfunction "D_2") (pintype "input"))
    )
    (net (code "629") (name "unconnected-(E87A-PRE-Pad4)") (class "Default")
      (node (ref "E87") (pin "4") (pinfunction "PRE_4") (pintype "input"))
    )
    (net (code "630") (name "unconnected-(E87A-Q-Pad5)") (class "Default")
      (node (ref "E87") (pin "5") (pinfunction "Q_5") (pintype "output"))
    )
    (net (code "631") (name "unconnected-(E87A-~{Q}-Pad6)") (class "Default")
      (node (ref "E87") (pin "6") (pinfunction "~{Q}_6") (pintype "output"))
    )
    (net (code "632") (name "unconnected-(E87B-CLK-Pad11)") (class "Default")
      (node (ref "E87") (pin "11") (pinfunction "CLK_11") (pintype "input"))
    )
    (net (code "633") (name "unconnected-(E87B-CLR-Pad13)") (class "Default")
      (node (ref "E87") (pin "13") (pinfunction "CLR_13") (pintype "input"))
    )
    (net (code "634") (name "unconnected-(E87B-D-Pad12)") (class "Default")
      (node (ref "E87") (pin "12") (pinfunction "D_12") (pintype "input"))
    )
    (net (code "635") (name "unconnected-(E87B-PRE-Pad10)") (class "Default")
      (node (ref "E87") (pin "10") (pinfunction "PRE_10") (pintype "input"))
    )
    (net (code "636") (name "unconnected-(E87B-Q-Pad9)") (class "Default")
      (node (ref "E87") (pin "9") (pinfunction "Q_9") (pintype "output"))
    )
    (net (code "637") (name "unconnected-(E87B-~{Q}-Pad8)") (class "Default")
      (node (ref "E87") (pin "8") (pinfunction "~{Q}_8") (pintype "output"))
    )
    (net (code "638") (name "unconnected-(E88-Pad1)") (class "Default")
      (node (ref "E88") (pin "1") (pinfunction "1_1") (pintype "passive"))
    )
    (net (code "639") (name "unconnected-(E88-Pad2)") (class "Default")
      (node (ref "E88") (pin "2") (pinfunction "2_2") (pintype "passive"))
    )
    (net (code "640") (name "unconnected-(E88-Pad3)") (class "Default")
      (node (ref "E88") (pin "3") (pinfunction "3_3") (pintype "passive"))
    )
    (net (code "641") (name "unconnected-(E88-Pad4)") (class "Default")
      (node (ref "E88") (pin "4") (pinfunction "4_4") (pintype "passive"))
    )
    (net (code "642") (name "unconnected-(E88-Pad5)") (class "Default")
      (node (ref "E88") (pin "5") (pinfunction "5_5") (pintype "passive"))
    )
    (net (code "643") (name "unconnected-(E88-Pad6)") (class "Default")
      (node (ref "E88") (pin "6") (pinfunction "6_6") (pintype "passive"))
    )
    (net (code "644") (name "unconnected-(E88-Pad7)") (class "Default")
      (node (ref "E88") (pin "7") (pinfunction "7_7") (pintype "passive"))
    )
    (net (code "645") (name "unconnected-(E88-Pad8)") (class "Default")
      (node (ref "E88") (pin "8") (pinfunction "8_8") (pintype "passive"))
    )
    (net (code "646") (name "unconnected-(E88-Pad9)") (class "Default")
      (node (ref "E88") (pin "9") (pinfunction "9_9") (pintype "passive"))
    )
    (net (code "647") (name "unconnected-(E88-Pad10)") (class "Default")
      (node (ref "E88") (pin "10") (pinfunction "10_10") (pintype "passive"))
    )
    (net (code "648") (name "unconnected-(E88-Pad11)") (class "Default")
      (node (ref "E88") (pin "11") (pinfunction "11_11") (pintype "passive"))
    )
    (net (code "649") (name "unconnected-(E88-Pad12)") (class "Default")
      (node (ref "E88") (pin "12") (pinfunction "12_12") (pintype "passive"))
    )
    (net (code "650") (name "unconnected-(E88-Pad13)") (class "Default")
      (node (ref "E88") (pin "13") (pinfunction "13_13") (pintype "passive"))
    )
    (net (code "651") (name "unconnected-(E88-Pad14)") (class "Default")
      (node (ref "E88") (pin "14") (pinfunction "14_14") (pintype "passive"))
    )
    (net (code "652") (name "unconnected-(E88-Pad15)") (class "Default")
      (node (ref "E88") (pin "15") (pinfunction "15_15") (pintype "passive"))
    )
    (net (code "653") (name "unconnected-(E88-Pad16)") (class "Default")
      (node (ref "E88") (pin "16") (pinfunction "16_16") (pintype "passive"))
    )
    (net (code "654") (name "unconnected-(E89A-I0-Pad4)") (class "Default")
      (node (ref "E89") (pin "4") (pinfunction "I0_4") (pintype "input"))
    )
    (net (code "655") (name "unconnected-(E89A-I1-Pad10)") (class "Default")
      (node (ref "E89") (pin "10") (pinfunction "I1_10") (pintype "input"))
    )
    (net (code "656") (name "unconnected-(E89A-I2-Pad3)") (class "Default")
      (node (ref "E89") (pin "3") (pinfunction "I2_3") (pintype "input"))
    )
    (net (code "657") (name "unconnected-(E89A-I3-Pad11)") (class "Default")
      (node (ref "E89") (pin "11") (pinfunction "I3_11") (pintype "input"))
    )
    (net (code "658") (name "unconnected-(E89A-Q0-Pad5)") (class "Default")
      (node (ref "E89") (pin "5") (pinfunction "Q0_5") (pintype "output"))
    )
    (net (code "659") (name "unconnected-(E89A-Q1-Pad9)") (class "Default")
      (node (ref "E89") (pin "9") (pinfunction "Q1_9") (pintype "output"))
    )
    (net (code "660") (name "unconnected-(E89A-Q2-Pad2)") (class "Default")
      (node (ref "E89") (pin "2") (pinfunction "Q2_2") (pintype "output"))
    )
    (net (code "661") (name "unconnected-(E89A-Q3-Pad12)") (class "Default")
      (node (ref "E89") (pin "12") (pinfunction "Q3_12") (pintype "output"))
    )
    (net (code "662") (name "unconnected-(E89A-{slash}2-Pad8)") (class "Default")
      (node (ref "E89") (pin "8") (pinfunction "/2_8") (pintype "bidirectional"))
    )
    (net (code "663") (name "unconnected-(E89A-{slash}8-Pad6)") (class "Default")
      (node (ref "E89") (pin "6") (pinfunction "/8_6") (pintype "bidirectional"))
    )
    (net (code "664") (name "unconnected-(E89A-~{LD}-Pad1)") (class "Default")
      (node (ref "E89") (pin "1") (pinfunction "~{LD}_1") (pintype "input"))
    )
    (net (code "665") (name "unconnected-(E89A-~{MR}-Pad13)") (class "Default")
      (node (ref "E89") (pin "13") (pinfunction "~{MR}_13") (pintype "input"))
    )
    (net (code "666") (name "unconnected-(E90A-A0-Pad1)") (class "Default")
      (node (ref "E90") (pin "1") (pinfunction "A0_1") (pintype "input"))
    )
    (net (code "667") (name "unconnected-(E90A-A1-Pad6)") (class "Default")
      (node (ref "E90") (pin "6") (pinfunction "A1_6") (pintype "input"))
    )
    (net (code "668") (name "unconnected-(E90A-A2-Pad10)") (class "Default")
      (node (ref "E90") (pin "10") (pinfunction "A2_10") (pintype "input"))
    )
    (net (code "669") (name "unconnected-(E90A-A3-Pad15)") (class "Default")
      (node (ref "E90") (pin "15") (pinfunction "A3_15") (pintype "input"))
    )
    (net (code "670") (name "unconnected-(E90A-B0-Pad2)") (class "Default")
      (node (ref "E90") (pin "2") (pinfunction "B0_2") (pintype "input"))
    )
    (net (code "671") (name "unconnected-(E90A-B1-Pad5)") (class "Default")
      (node (ref "E90") (pin "5") (pinfunction "B1_5") (pintype "input"))
    )
    (net (code "672") (name "unconnected-(E90A-B2-Pad11)") (class "Default")
      (node (ref "E90") (pin "11") (pinfunction "B2_11") (pintype "input"))
    )
    (net (code "673") (name "unconnected-(E90A-B3-Pad14)") (class "Default")
      (node (ref "E90") (pin "14") (pinfunction "B3_14") (pintype "input"))
    )
    (net (code "674") (name "unconnected-(E90A-F0-Pad3)") (class "Default")
      (node (ref "E90") (pin "3") (pinfunction "F0_3") (pintype "output"))
    )
    (net (code "675") (name "unconnected-(E90A-F1-Pad4)") (class "Default")
      (node (ref "E90") (pin "4") (pinfunction "F1_4") (pintype "output"))
    )
    (net (code "676") (name "unconnected-(E90A-F2-Pad12)") (class "Default")
      (node (ref "E90") (pin "12") (pinfunction "F2_12") (pintype "output"))
    )
    (net (code "677") (name "unconnected-(E90A-F3-Pad13)") (class "Default")
      (node (ref "E90") (pin "13") (pinfunction "F3_13") (pintype "output"))
    )
    (net (code "678") (name "unconnected-(E90A-S0-Pad9)") (class "Default")
      (node (ref "E90") (pin "9") (pinfunction "S0_9") (pintype "input"))
    )
    (net (code "679") (name "unconnected-(E90A-S1-Pad7)") (class "Default")
      (node (ref "E90") (pin "7") (pinfunction "S1_7") (pintype "input"))
    )
    (net (code "680") (name "unconnected-(E91A-I0-Pad1)") (class "Default")
      (node (ref "E91") (pin "1") (pinfunction "I0_1") (pintype "input"))
    )
    (net (code "681") (name "unconnected-(E91A-I1-Pad2)") (class "Default")
      (node (ref "E91") (pin "2") (pinfunction "I1_2") (pintype "input"))
    )
    (net (code "682") (name "unconnected-(E91A-O-Pad3)") (class "Default")
      (node (ref "E91") (pin "3") (pinfunction "O_3") (pintype "output"))
    )
    (net (code "683") (name "unconnected-(E92-Pad1)") (class "Default")
      (node (ref "E92") (pin "1") (pinfunction "1_1") (pintype "passive"))
    )
    (net (code "684") (name "unconnected-(E92-Pad2)") (class "Default")
      (node (ref "E92") (pin "2") (pinfunction "2_2") (pintype "passive"))
    )
    (net (code "685") (name "unconnected-(E92-Pad3)") (class "Default")
      (node (ref "E92") (pin "3") (pinfunction "3_3") (pintype "passive"))
    )
    (net (code "686") (name "unconnected-(E92-Pad4)") (class "Default")
      (node (ref "E92") (pin "4") (pinfunction "4_4") (pintype "passive"))
    )
    (net (code "687") (name "unconnected-(E92-Pad5)") (class "Default")
      (node (ref "E92") (pin "5") (pinfunction "5_5") (pintype "passive"))
    )
    (net (code "688") (name "unconnected-(E92-Pad6)") (class "Default")
      (node (ref "E92") (pin "6") (pinfunction "6_6") (pintype "passive"))
    )
    (net (code "689") (name "unconnected-(E92-Pad7)") (class "Default")
      (node (ref "E92") (pin "7") (pinfunction "7_7") (pintype "passive"))
    )
    (net (code "690") (name "unconnected-(E92-Pad8)") (class "Default")
      (node (ref "E92") (pin "8") (pinfunction "8_8") (pintype "passive"))
    )
    (net (code "691") (name "unconnected-(E92-Pad9)") (class "Default")
      (node (ref "E92") (pin "9") (pinfunction "9_9") (pintype "passive"))
    )
    (net (code "692") (name "unconnected-(E92-Pad10)") (class "Default")
      (node (ref "E92") (pin "10") (pinfunction "10_10") (pintype "passive"))
    )
    (net (code "693") (name "unconnected-(E92-Pad11)") (class "Default")
      (node (ref "E92") (pin "11") (pinfunction "11_11") (pintype "passive"))
    )
    (net (code "694") (name "unconnected-(E92-Pad12)") (class "Default")
      (node (ref "E92") (pin "12") (pinfunction "12_12") (pintype "passive"))
    )
    (net (code "695") (name "unconnected-(E92-Pad13)") (class "Default")
      (node (ref "E92") (pin "13") (pinfunction "13_13") (pintype "passive"))
    )
    (net (code "696") (name "unconnected-(E92-Pad14)") (class "Default")
      (node (ref "E92") (pin "14") (pinfunction "14_14") (pintype "passive"))
    )
    (net (code "697") (name "unconnected-(E92-Pad15)") (class "Default")
      (node (ref "E92") (pin "15") (pinfunction "15_15") (pintype "passive"))
    )
    (net (code "698") (name "unconnected-(E92-Pad16)") (class "Default")
      (node (ref "E92") (pin "16") (pinfunction "16_16") (pintype "passive"))
    )
    (net (code "699") (name "unconnected-(E93-Pad1)") (class "Default")
      (node (ref "E93") (pin "1") (pinfunction "1_1") (pintype "passive"))
    )
    (net (code "700") (name "unconnected-(E93-Pad2)") (class "Default")
      (node (ref "E93") (pin "2") (pinfunction "2_2") (pintype "passive"))
    )
    (net (code "701") (name "unconnected-(E93-Pad3)") (class "Default")
      (node (ref "E93") (pin "3") (pinfunction "3_3") (pintype "passive"))
    )
    (net (code "702") (name "unconnected-(E93-Pad4)") (class "Default")
      (node (ref "E93") (pin "4") (pinfunction "4_4") (pintype "passive"))
    )
    (net (code "703") (name "unconnected-(E93-Pad5)") (class "Default")
      (node (ref "E93") (pin "5") (pinfunction "5_5") (pintype "passive"))
    )
    (net (code "704") (name "unconnected-(E93-Pad6)") (class "Default")
      (node (ref "E93") (pin "6") (pinfunction "6_6") (pintype "passive"))
    )
    (net (code "705") (name "unconnected-(E93-Pad7)") (class "Default")
      (node (ref "E93") (pin "7") (pinfunction "7_7") (pintype "passive"))
    )
    (net (code "706") (name "unconnected-(E93-Pad8)") (class "Default")
      (node (ref "E93") (pin "8") (pinfunction "8_8") (pintype "passive"))
    )
    (net (code "707") (name "unconnected-(E93-Pad9)") (class "Default")
      (node (ref "E93") (pin "9") (pinfunction "9_9") (pintype "passive"))
    )
    (net (code "708") (name "unconnected-(E93-Pad10)") (class "Default")
      (node (ref "E93") (pin "10") (pinfunction "10_10") (pintype "passive"))
    )
    (net (code "709") (name "unconnected-(E93-Pad11)") (class "Default")
      (node (ref "E93") (pin "11") (pinfunction "11_11") (pintype "passive"))
    )
    (net (code "710") (name "unconnected-(E93-Pad12)") (class "Default")
      (node (ref "E93") (pin "12") (pinfunction "12_12") (pintype "passive"))
    )
    (net (code "711") (name "unconnected-(E93-Pad13)") (class "Default")
      (node (ref "E93") (pin "13") (pinfunction "13_13") (pintype "passive"))
    )
    (net (code "712") (name "unconnected-(E93-Pad14)") (class "Default")
      (node (ref "E93") (pin "14") (pinfunction "14_14") (pintype "passive"))
    )
    (net (code "713") (name "unconnected-(E93-Pad15)") (class "Default")
      (node (ref "E93") (pin "15") (pinfunction "15_15") (pintype "passive"))
    )
    (net (code "714") (name "unconnected-(E93-Pad16)") (class "Default")
      (node (ref "E93") (pin "16") (pinfunction "16_16") (pintype "passive"))
    )
    (net (code "715") (name "unconnected-(Q1-B-Pad2)") (class "Default")
      (node (ref "Q1") (pin "2") (pinfunction "B_2") (pintype "passive"))
    )
    (net (code "716") (name "unconnected-(Q1-C-Pad3)") (class "Default")
      (node (ref "Q1") (pin "3") (pinfunction "C_3") (pintype "passive"))
    )
    (net (code "717") (name "unconnected-(Q1-E-Pad1)") (class "Default")
      (node (ref "Q1") (pin "1") (pinfunction "E_1") (pintype "passive"))
    )
    (net (code "718") (name "unconnected-(Q2-B-Pad2)") (class "Default")
      (node (ref "Q2") (pin "2") (pinfunction "B_2") (pintype "passive"))
    )
    (net (code "719") (name "unconnected-(Q2-C-Pad3)") (class "Default")
      (node (ref "Q2") (pin "3") (pinfunction "C_3") (pintype "passive"))
    )
    (net (code "720") (name "unconnected-(Q2-E-Pad1)") (class "Default")
      (node (ref "Q2") (pin "1") (pinfunction "E_1") (pintype "passive"))
    )
    (net (code "721") (name "unconnected-(Q3-B-Pad2)") (class "Default")
      (node (ref "Q3") (pin "2") (pinfunction "B_2") (pintype "passive"))
    )
    (net (code "722") (name "unconnected-(Q3-C-Pad3)") (class "Default")
      (node (ref "Q3") (pin "3") (pinfunction "C_3") (pintype "passive"))
    )
    (net (code "723") (name "unconnected-(Q3-E-Pad1)") (class "Default")
      (node (ref "Q3") (pin "1") (pinfunction "E_1") (pintype "passive"))
    )
    (net (code "724") (name "unconnected-(R1-Pad1)") (class "Default")
      (node (ref "R1") (pin "1") (pinfunction "1_1") (pintype "passive"))
    )
    (net (code "725") (name "unconnected-(R1-Pad2)") (class "Default")
      (node (ref "R1") (pin "2") (pinfunction "2_2") (pintype "passive"))
    )
    (net (code "726") (name "unconnected-(R2-Pad1)") (class "Default")
      (node (ref "R2") (pin "1") (pinfunction "1_1") (pintype "passive"))
    )
    (net (code "727") (name "unconnected-(R2-Pad2)") (class "Default")
      (node (ref "R2") (pin "2") (pinfunction "2_2") (pintype "passive"))
    )
    (net (code "728") (name "unconnected-(R3-Pad1)") (class "Default")
      (node (ref "R3") (pin "1") (pinfunction "1_1") (pintype "passive"))
    )
    (net (code "729") (name "unconnected-(R3-Pad2)") (class "Default")
      (node (ref "R3") (pin "2") (pinfunction "2_2") (pintype "passive"))
    )
    (net (code "730") (name "unconnected-(R4-Pad1)") (class "Default")
      (node (ref "R4") (pin "1") (pinfunction "1_1") (pintype "passive"))
    )
    (net (code "731") (name "unconnected-(R4-Pad2)") (class "Default")
      (node (ref "R4") (pin "2") (pinfunction "2_2") (pintype "passive"))
    )
    (net (code "732") (name "unconnected-(R5-Pad1)") (class "Default")
      (node (ref "R5") (pin "1") (pinfunction "1_1") (pintype "passive"))
    )
    (net (code "733") (name "unconnected-(R5-Pad2)") (class "Default")
      (node (ref "R5") (pin "2") (pinfunction "2_2") (pintype "passive"))
    )
    (net (code "734") (name "unconnected-(R6-Pad1)") (class "Default")
      (node (ref "R6") (pin "1") (pinfunction "1_1") (pintype "passive"))
    )
    (net (code "735") (name "unconnected-(R6-Pad2)") (class "Default")
      (node (ref "R6") (pin "2") (pinfunction "2_2") (pintype "passive"))
    )
    (net (code "736") (name "unconnected-(R7-Pad1)") (class "Default")
      (node (ref "R7") (pin "1") (pinfunction "1_1") (pintype "passive"))
    )
    (net (code "737") (name "unconnected-(R7-Pad2)") (class "Default")
      (node (ref "R7") (pin "2") (pinfunction "2_2") (pintype "passive"))
    )
    (net (code "738") (name "unconnected-(R8-Pad1)") (class "Default")
      (node (ref "R8") (pin "1") (pinfunction "1_1") (pintype "passive"))
    )
    (net (code "739") (name "unconnected-(R8-Pad2)") (class "Default")
      (node (ref "R8") (pin "2") (pinfunction "2_2") (pintype "passive"))
    )
    (net (code "740") (name "unconnected-(R9-Pad1)") (class "Default")
      (node (ref "R9") (pin "1") (pinfunction "1_1") (pintype "passive"))
    )
    (net (code "741") (name "unconnected-(R9-Pad2)") (class "Default")
      (node (ref "R9") (pin "2") (pinfunction "2_2") (pintype "passive"))
    )
    (net (code "742") (name "unconnected-(R10-Pad1)") (class "Default")
      (node (ref "R10") (pin "1") (pinfunction "1_1") (pintype "passive"))
    )
    (net (code "743") (name "unconnected-(R10-Pad2)") (class "Default")
      (node (ref "R10") (pin "2") (pinfunction "2_2") (pintype "passive"))
    )
    (net (code "744") (name "unconnected-(R11-Pad1)") (class "Default")
      (node (ref "R11") (pin "1") (pinfunction "1_1") (pintype "passive"))
    )
    (net (code "745") (name "unconnected-(R11-Pad2)") (class "Default")
      (node (ref "R11") (pin "2") (pinfunction "2_2") (pintype "passive"))
    )
    (net (code "746") (name "unconnected-(R12-Pad1)") (class "Default")
      (node (ref "R12") (pin "1") (pinfunction "1_1") (pintype "passive"))
    )
    (net (code "747") (name "unconnected-(R12-Pad2)") (class "Default")
      (node (ref "R12") (pin "2") (pinfunction "2_2") (pintype "passive"))
    )
    (net (code "748") (name "unconnected-(R13-Pad1)") (class "Default")
      (node (ref "R13") (pin "1") (pinfunction "1_1") (pintype "passive"))
    )
    (net (code "749") (name "unconnected-(R13-Pad2)") (class "Default")
      (node (ref "R13") (pin "2") (pinfunction "2_2") (pintype "passive"))
    )
    (net (code "750") (name "unconnected-(R14-Pad1)") (class "Default")
      (node (ref "R14") (pin "1") (pinfunction "1_1") (pintype "passive"))
    )
    (net (code "751") (name "unconnected-(R14-Pad2)") (class "Default")
      (node (ref "R14") (pin "2") (pinfunction "2_2") (pintype "passive"))
    )
    (net (code "752") (name "unconnected-(R15-Pad1)") (class "Default")
      (node (ref "R15") (pin "1") (pinfunction "1_1") (pintype "passive"))
    )
    (net (code "753") (name "unconnected-(R15-Pad2)") (class "Default")
      (node (ref "R15") (pin "2") (pinfunction "2_2") (pintype "passive"))
    )
    (net (code "754") (name "unconnected-(R16-Pad1)") (class "Default")
      (node (ref "R16") (pin "1") (pinfunction "1_1") (pintype "passive"))
    )
    (net (code "755") (name "unconnected-(R16-Pad2)") (class "Default")
      (node (ref "R16") (pin "2") (pinfunction "2_2") (pintype "passive"))
    )
    (net (code "756") (name "unconnected-(R17-Pad1)") (class "Default")
      (node (ref "R17") (pin "1") (pinfunction "1_1") (pintype "passive"))
    )
    (net (code "757") (name "unconnected-(R17-Pad2)") (class "Default")
      (node (ref "R17") (pin "2") (pinfunction "2_2") (pintype "passive"))
    )
    (net (code "758") (name "unconnected-(R18-Pad1)") (class "Default")
      (node (ref "R18") (pin "1") (pinfunction "1_1") (pintype "passive"))
    )
    (net (code "759") (name "unconnected-(R18-Pad2)") (class "Default")
      (node (ref "R18") (pin "2") (pinfunction "2_2") (pintype "passive"))
    )
    (net (code "760") (name "unconnected-(R19-Pad1)") (class "Default")
      (node (ref "R19") (pin "1") (pinfunction "1_1") (pintype "passive"))
    )
    (net (code "761") (name "unconnected-(R19-Pad2)") (class "Default")
      (node (ref "R19") (pin "2") (pinfunction "2_2") (pintype "passive"))
    )
    (net (code "762") (name "unconnected-(R20-Pad1)") (class "Default")
      (node (ref "R20") (pin "1") (pinfunction "1_1") (pintype "passive"))
    )
    (net (code "763") (name "unconnected-(R20-Pad2)") (class "Default")
      (node (ref "R20") (pin "2") (pinfunction "2_2") (pintype "passive"))
    )
    (net (code "764") (name "unconnected-(R21-Pad1)") (class "Default")
      (node (ref "R21") (pin "1") (pinfunction "1_1") (pintype "passive"))
    )
    (net (code "765") (name "unconnected-(R21-Pad2)") (class "Default")
      (node (ref "R21") (pin "2") (pinfunction "2_2") (pintype "passive"))
    )
    (net (code "766") (name "unconnected-(R22-Pad1)") (class "Default")
      (node (ref "R22") (pin "1") (pinfunction "1_1") (pintype "passive"))
    )
    (net (code "767") (name "unconnected-(R22-Pad2)") (class "Default")
      (node (ref "R22") (pin "2") (pinfunction "2_2") (pintype "passive"))
    )
    (net (code "768") (name "unconnected-(R23-Pad1)") (class "Default")
      (node (ref "R23") (pin "1") (pinfunction "1_1") (pintype "passive"))
    )
    (net (code "769") (name "unconnected-(R23-Pad2)") (class "Default")
      (node (ref "R23") (pin "2") (pinfunction "2_2") (pintype "passive"))
    )
    (net (code "770") (name "unconnected-(R24-Pad1)") (class "Default")
      (node (ref "R24") (pin "1") (pinfunction "1_1") (pintype "passive"))
    )
    (net (code "771") (name "unconnected-(R24-Pad2)") (class "Default")
      (node (ref "R24") (pin "2") (pinfunction "2_2") (pintype "passive"))
    )
    (net (code "772") (name "unconnected-(R25-Pad1)") (class "Default")
      (node (ref "R25") (pin "1") (pinfunction "1_1") (pintype "passive"))
    )
    (net (code "773") (name "unconnected-(R25-Pad2)") (class "Default")
      (node (ref "R25") (pin "2") (pinfunction "2_2") (pintype "passive"))
    )
    (net (code "774") (name "unconnected-(R26-Pad1)") (class "Default")
      (node (ref "R26") (pin "1") (pinfunction "1_1") (pintype "passive"))
    )
    (net (code "775") (name "unconnected-(R26-Pad2)") (class "Default")
      (node (ref "R26") (pin "2") (pinfunction "2_2") (pintype "passive"))
    )
    (net (code "776") (name "unconnected-(R27-Pad1)") (class "Default")
      (node (ref "R27") (pin "1") (pinfunction "1_1") (pintype "passive"))
    )
    (net (code "777") (name "unconnected-(R27-Pad2)") (class "Default")
      (node (ref "R27") (pin "2") (pinfunction "2_2") (pintype "passive"))
    )
    (net (code "778") (name "unconnected-(R28-Pad1)") (class "Default")
      (node (ref "R28") (pin "1") (pinfunction "1_1") (pintype "passive"))
    )
    (net (code "779") (name "unconnected-(R28-Pad2)") (class "Default")
      (node (ref "R28") (pin "2") (pinfunction "2_2") (pintype "passive"))
    )
    (net (code "780") (name "unconnected-(R29-Pad1)") (class "Default")
      (node (ref "R29") (pin "1") (pinfunction "1_1") (pintype "passive"))
    )
    (net (code "781") (name "unconnected-(R29-Pad2)") (class "Default")
      (node (ref "R29") (pin "2") (pinfunction "2_2") (pintype "passive"))
    )
    (net (code "782") (name "unconnected-(R30-Pad1)") (class "Default")
      (node (ref "R30") (pin "1") (pinfunction "1_1") (pintype "passive"))
    )
    (net (code "783") (name "unconnected-(R30-Pad2)") (class "Default")
      (node (ref "R30") (pin "2") (pinfunction "2_2") (pintype "passive"))
    )
    (net (code "784") (name "unconnected-(R31-Pad1)") (class "Default")
      (node (ref "R31") (pin "1") (pinfunction "1_1") (pintype "passive"))
    )
    (net (code "785") (name "unconnected-(R31-Pad2)") (class "Default")
      (node (ref "R31") (pin "2") (pinfunction "2_2") (pintype "passive"))
    )
    (net (code "786") (name "unconnected-(R32-Pad1)") (class "Default")
      (node (ref "R32") (pin "1") (pinfunction "1_1") (pintype "passive"))
    )
    (net (code "787") (name "unconnected-(R32-Pad2)") (class "Default")
      (node (ref "R32") (pin "2") (pinfunction "2_2") (pintype "passive"))
    )
    (net (code "788") (name "unconnected-(R33-Pad1)") (class "Default")
      (node (ref "R33") (pin "1") (pinfunction "1_1") (pintype "passive"))
    )
    (net (code "789") (name "unconnected-(R33-Pad2)") (class "Default")
      (node (ref "R33") (pin "2") (pinfunction "2_2") (pintype "passive"))
    )
    (net (code "790") (name "unconnected-(R34-Pad1)") (class "Default")
      (node (ref "R34") (pin "1") (pinfunction "1_1") (pintype "passive"))
    )
    (net (code "791") (name "unconnected-(R34-Pad2)") (class "Default")
      (node (ref "R34") (pin "2") (pinfunction "2_2") (pintype "passive"))
    )
    (net (code "792") (name "unconnected-(R35-Pad1)") (class "Default")
      (node (ref "R35") (pin "1") (pinfunction "1_1") (pintype "passive"))
    )
    (net (code "793") (name "unconnected-(R35-Pad2)") (class "Default")
      (node (ref "R35") (pin "2") (pinfunction "2_2") (pintype "passive"))
    )
    (net (code "794") (name "unconnected-(R36-Pad1)") (class "Default")
      (node (ref "R36") (pin "1") (pinfunction "1_1") (pintype "passive"))
    )
    (net (code "795") (name "unconnected-(R36-Pad2)") (class "Default")
      (node (ref "R36") (pin "2") (pinfunction "2_2") (pintype "passive"))
    )
    (net (code "796") (name "unconnected-(R37-Pad1)") (class "Default")
      (node (ref "R37") (pin "1") (pinfunction "1_1") (pintype "passive"))
    )
    (net (code "797") (name "unconnected-(R37-Pad2)") (class "Default")
      (node (ref "R37") (pin "2") (pinfunction "2_2") (pintype "passive"))
    )
    (net (code "798") (name "unconnected-(R38-Pad1)") (class "Default")
      (node (ref "R38") (pin "1") (pinfunction "1_1") (pintype "passive"))
    )
    (net (code "799") (name "unconnected-(R38-Pad2)") (class "Default")
      (node (ref "R38") (pin "2") (pinfunction "2_2") (pintype "passive"))
    )
    (net (code "800") (name "unconnected-(R39-Pad1)") (class "Default")
      (node (ref "R39") (pin "1") (pinfunction "1_1") (pintype "passive"))
    )
    (net (code "801") (name "unconnected-(R39-Pad2)") (class "Default")
      (node (ref "R39") (pin "2") (pinfunction "2_2") (pintype "passive"))
    )
    (net (code "802") (name "unconnected-(R40-Pad1)") (class "Default")
      (node (ref "R40") (pin "1") (pinfunction "1_1") (pintype "passive"))
    )
    (net (code "803") (name "unconnected-(R40-Pad2)") (class "Default")
      (node (ref "R40") (pin "2") (pinfunction "2_2") (pintype "passive"))
    )
    (net (code "804") (name "unconnected-(R41-Pad1)") (class "Default")
      (node (ref "R41") (pin "1") (pinfunction "1_1") (pintype "passive"))
    )
    (net (code "805") (name "unconnected-(R41-Pad2)") (class "Default")
      (node (ref "R41") (pin "2") (pinfunction "2_2") (pintype "passive"))
    )
    (net (code "806") (name "unconnected-(R42-Pad1)") (class "Default")
      (node (ref "R42") (pin "1") (pinfunction "1_1") (pintype "passive"))
    )
    (net (code "807") (name "unconnected-(R42-Pad2)") (class "Default")
      (node (ref "R42") (pin "2") (pinfunction "2_2") (pintype "passive"))
    )
    (net (code "808") (name "unconnected-(R43-Pad1)") (class "Default")
      (node (ref "R43") (pin "1") (pinfunction "1_1") (pintype "passive"))
    )
    (net (code "809") (name "unconnected-(R43-Pad2)") (class "Default")
      (node (ref "R43") (pin "2") (pinfunction "2_2") (pintype "passive"))
    )
    (net (code "810") (name "unconnected-(R44-Pad1)") (class "Default")
      (node (ref "R44") (pin "1") (pinfunction "1_1") (pintype "passive"))
    )
    (net (code "811") (name "unconnected-(R44-Pad2)") (class "Default")
      (node (ref "R44") (pin "2") (pinfunction "2_2") (pintype "passive"))
    )
    (net (code "812") (name "unconnected-(R45-Pad1)") (class "Default")
      (node (ref "R45") (pin "1") (pinfunction "1_1") (pintype "passive"))
    )
    (net (code "813") (name "unconnected-(R45-Pad2)") (class "Default")
      (node (ref "R45") (pin "2") (pinfunction "2_2") (pintype "passive"))
    )
    (net (code "814") (name "unconnected-(R46-Pad1)") (class "Default")
      (node (ref "R46") (pin "1") (pinfunction "1_1") (pintype "passive"))
    )
    (net (code "815") (name "unconnected-(R46-Pad2)") (class "Default")
      (node (ref "R46") (pin "2") (pinfunction "2_2") (pintype "passive"))
    )
    (net (code "816") (name "unconnected-(R47-Pad1)") (class "Default")
      (node (ref "R47") (pin "1") (pinfunction "1_1") (pintype "passive"))
    )
    (net (code "817") (name "unconnected-(R47-Pad2)") (class "Default")
      (node (ref "R47") (pin "2") (pinfunction "2_2") (pintype "passive"))
    )
    (net (code "818") (name "unconnected-(R48-Pad1)") (class "Default")
      (node (ref "R48") (pin "1") (pinfunction "1_1") (pintype "passive"))
    )
    (net (code "819") (name "unconnected-(R48-Pad2)") (class "Default")
      (node (ref "R48") (pin "2") (pinfunction "2_2") (pintype "passive"))
    )
    (net (code "820") (name "unconnected-(R49-Pad1)") (class "Default")
      (node (ref "R49") (pin "1") (pinfunction "1_1") (pintype "passive"))
    )
    (net (code "821") (name "unconnected-(R49-Pad2)") (class "Default")
      (node (ref "R49") (pin "2") (pinfunction "2_2") (pintype "passive"))
    )
    (net (code "822") (name "unconnected-(R50-Pad1)") (class "Default")
      (node (ref "R50") (pin "1") (pinfunction "1_1") (pintype "passive"))
    )
    (net (code "823") (name "unconnected-(R50-Pad2)") (class "Default")
      (node (ref "R50") (pin "2") (pinfunction "2_2") (pintype "passive"))
    )
    (net (code "824") (name "unconnected-(R51-Pad1)") (class "Default")
      (node (ref "R51") (pin "1") (pinfunction "1_1") (pintype "passive"))
    )
    (net (code "825") (name "unconnected-(R51-Pad2)") (class "Default")
      (node (ref "R51") (pin "2") (pinfunction "2_2") (pintype "passive"))
    )
    (net (code "826") (name "unconnected-(R52-Pad1)") (class "Default")
      (node (ref "R52") (pin "1") (pinfunction "1_1") (pintype "passive"))
    )
    (net (code "827") (name "unconnected-(R52-Pad2)") (class "Default")
      (node (ref "R52") (pin "2") (pinfunction "2_2") (pintype "passive"))
    )
    (net (code "828") (name "unconnected-(R53-Pad1)") (class "Default")
      (node (ref "R53") (pin "1") (pinfunction "1_1") (pintype "passive"))
    )
    (net (code "829") (name "unconnected-(R53-Pad2)") (class "Default")
      (node (ref "R53") (pin "2") (pinfunction "2_2") (pintype "passive"))
    )
    (net (code "830") (name "unconnected-(R54-Pad1)") (class "Default")
      (node (ref "R54") (pin "1") (pinfunction "1_1") (pintype "passive"))
    )
    (net (code "831") (name "unconnected-(R54-Pad2)") (class "Default")
      (node (ref "R54") (pin "2") (pinfunction "2_2") (pintype "passive"))
    )
    (net (code "832") (name "unconnected-(SW1-Pad1)") (class "Default")
      (node (ref "SW1") (pin "1") (pinfunction "1_1") (pintype "passive"))
    )
    (net (code "833") (name "unconnected-(SW1A-2-Pad16)") (class "Default")
      (node (ref "SW1") (pin "16") (pinfunction "2_16") (pintype "passive"))
    )
    (net (code "834") (name "unconnected-(SW1B-1-Pad2)") (class "Default")
      (node (ref "SW1") (pin "2") (pinfunction "1_2") (pintype "passive"))
    )
    (net (code "835") (name "unconnected-(SW1B-2-Pad15)") (class "Default")
      (node (ref "SW1") (pin "15") (pinfunction "2_15") (pintype "passive"))
    )
    (net (code "836") (name "unconnected-(SW1C-1-Pad3)") (class "Default")
      (node (ref "SW1") (pin "3") (pinfunction "1_3") (pintype "passive"))
    )
    (net (code "837") (name "unconnected-(SW1C-2-Pad14)") (class "Default")
      (node (ref "SW1") (pin "14") (pinfunction "2_14") (pintype "passive"))
    )
    (net (code "838") (name "unconnected-(SW1D-1-Pad4)") (class "Default")
      (node (ref "SW1") (pin "4") (pinfunction "1_4") (pintype "passive"))
    )
    (net (code "839") (name "unconnected-(SW1D-2-Pad13)") (class "Default")
      (node (ref "SW1") (pin "13") (pinfunction "2_13") (pintype "passive"))
    )
    (net (code "840") (name "unconnected-(SW1E-1-Pad5)") (class "Default")
      (node (ref "SW1") (pin "5") (pinfunction "1_5") (pintype "passive"))
    )
    (net (code "841") (name "unconnected-(SW1E-2-Pad12)") (class "Default")
      (node (ref "SW1") (pin "12") (pinfunction "2_12") (pintype "passive"))
    )
    (net (code "842") (name "unconnected-(SW1F-1-Pad6)") (class "Default")
      (node (ref "SW1") (pin "6") (pinfunction "1_6") (pintype "passive"))
    )
    (net (code "843") (name "unconnected-(SW1F-2-Pad11)") (class "Default")
      (node (ref "SW1") (pin "11") (pinfunction "2_11") (pintype "passive"))
    )
    (net (code "844") (name "unconnected-(SW1G-1-Pad7)") (class "Default")
      (node (ref "SW1") (pin "7") (pinfunction "1_7") (pintype "passive"))
    )
    (net (code "845") (name "unconnected-(SW1G-2-Pad10)") (class "Default")
      (node (ref "SW1") (pin "10") (pinfunction "2_10") (pintype "passive"))
    )
    (net (code "846") (name "unconnected-(SW1H-1-Pad8)") (class "Default")
      (node (ref "SW1") (pin "8") (pinfunction "1_8") (pintype "passive"))
    )
    (net (code "847") (name "unconnected-(SW1H-2-Pad9)") (class "Default")
      (node (ref "SW1") (pin "9") (pinfunction "2_9") (pintype "passive"))
    )
    (net (code "848") (name "unconnected-(SW2-Pad1)") (class "Default")
      (node (ref "SW2") (pin "1") (pinfunction "1_1") (pintype "passive"))
    )
    (net (code "849") (name "unconnected-(SW2A-2-Pad16)") (class "Default")
      (node (ref "SW2") (pin "16") (pinfunction "2_16") (pintype "passive"))
    )
    (net (code "850") (name "unconnected-(SW2B-1-Pad2)") (class "Default")
      (node (ref "SW2") (pin "2") (pinfunction "1_2") (pintype "passive"))
    )
    (net (code "851") (name "unconnected-(SW2B-2-Pad15)") (class "Default")
      (node (ref "SW2") (pin "15") (pinfunction "2_15") (pintype "passive"))
    )
    (net (code "852") (name "unconnected-(SW2C-1-Pad3)") (class "Default")
      (node (ref "SW2") (pin "3") (pinfunction "1_3") (pintype "passive"))
    )
    (net (code "853") (name "unconnected-(SW2C-2-Pad14)") (class "Default")
      (node (ref "SW2") (pin "14") (pinfunction "2_14") (pintype "passive"))
    )
    (net (code "854") (name "unconnected-(SW2D-1-Pad4)") (class "Default")
      (node (ref "SW2") (pin "4") (pinfunction "1_4") (pintype "passive"))
    )
    (net (code "855") (name "unconnected-(SW2D-2-Pad13)") (class "Default")
      (node (ref "SW2") (pin "13") (pinfunction "2_13") (pintype "passive"))
    )
    (net (code "856") (name "unconnected-(SW2E-1-Pad5)") (class "Default")
      (node (ref "SW2") (pin "5") (pinfunction "1_5") (pintype "passive"))
    )
    (net (code "857") (name "unconnected-(SW2E-2-Pad12)") (class "Default")
      (node (ref "SW2") (pin "12") (pinfunction "2_12") (pintype "passive"))
    )
    (net (code "858") (name "unconnected-(SW2F-1-Pad6)") (class "Default")
      (node (ref "SW2") (pin "6") (pinfunction "1_6") (pintype "passive"))
    )
    (net (code "859") (name "unconnected-(SW2F-2-Pad11)") (class "Default")
      (node (ref "SW2") (pin "11") (pinfunction "2_11") (pintype "passive"))
    )
    (net (code "860") (name "unconnected-(SW2G-1-Pad7)") (class "Default")
      (node (ref "SW2") (pin "7") (pinfunction "1_7") (pintype "passive"))
    )
    (net (code "861") (name "unconnected-(SW2G-2-Pad10)") (class "Default")
      (node (ref "SW2") (pin "10") (pinfunction "2_10") (pintype "passive"))
    )
    (net (code "862") (name "unconnected-(SW2H-1-Pad8)") (class "Default")
      (node (ref "SW2") (pin "8") (pinfunction "1_8") (pintype "passive"))
    )
    (net (code "863") (name "unconnected-(SW2H-2-Pad9)") (class "Default")
      (node (ref "SW2") (pin "9") (pinfunction "2_9") (pintype "passive"))
    )
    (net (code "864") (name "unconnected-(U$1A-1-PadAA1)") (class "Default")
      (node (ref "U$1") (pin "AA1") (pinfunction "1_AA1") (pintype "bidirectional"))
    )
    (net (code "865") (name "unconnected-(U$1AA-1-PadAR1)") (class "Default")
      (node (ref "U$1") (pin "AR1") (pinfunction "1_AR1") (pintype "bidirectional"))
    )
    (net (code "866") (name "unconnected-(U$1AB-1-PadAR2)") (class "Default")
      (node (ref "U$1") (pin "AR2") (pinfunction "1_AR2") (pintype "bidirectional"))
    )
    (net (code "867") (name "unconnected-(U$1AC-1-PadAS1)") (class "Default")
      (node (ref "U$1") (pin "AS1") (pinfunction "1_AS1") (pintype "bidirectional"))
    )
    (net (code "868") (name "unconnected-(U$1AD-1-PadAS2)") (class "Default")
      (node (ref "U$1") (pin "AS2") (pinfunction "1_AS2") (pintype "bidirectional"))
    )
    (net (code "869") (name "unconnected-(U$1AG-1-PadAU1)") (class "Default")
      (node (ref "U$1") (pin "AU1") (pinfunction "1_AU1") (pintype "bidirectional"))
    )
    (net (code "870") (name "unconnected-(U$1AH-1-PadAU2)") (class "Default")
      (node (ref "U$1") (pin "AU2") (pinfunction "1_AU2") (pintype "bidirectional"))
    )
    (net (code "871") (name "unconnected-(U$1AI-1-PadAV1)") (class "Default")
      (node (ref "U$1") (pin "AV1") (pinfunction "1_AV1") (pintype "bidirectional"))
    )
    (net (code "872") (name "unconnected-(U$1AJ-1-PadAV2)") (class "Default")
      (node (ref "U$1") (pin "AV2") (pinfunction "1_AV2") (pintype "bidirectional"))
    )
    (net (code "873") (name "unconnected-(U$1AK-1-PadBA1)") (class "Default")
      (node (ref "U$1") (pin "BA1") (pinfunction "1_BA1") (pintype "bidirectional"))
    )
    (net (code "874") (name "unconnected-(U$1AM-1-PadBB1)") (class "Default")
      (node (ref "U$1") (pin "BB1") (pinfunction "1_BB1") (pintype "bidirectional"))
    )
    (net (code "875") (name "unconnected-(U$1AN-1-PadBB2)") (class "Default")
      (node (ref "U$1") (pin "BB2") (pinfunction "1_BB2") (pintype "bidirectional"))
    )
    (net (code "876") (name "unconnected-(U$1AQ-1-PadBD1)") (class "Default")
      (node (ref "U$1") (pin "BD1") (pinfunction "1_BD1") (pintype "bidirectional"))
    )
    (net (code "877") (name "unconnected-(U$1AR-1-PadBD2)") (class "Default")
      (node (ref "U$1") (pin "BD2") (pinfunction "1_BD2") (pintype "bidirectional"))
    )
    (net (code "878") (name "unconnected-(U$1AS-1-PadBE1)") (class "Default")
      (node (ref "U$1") (pin "BE1") (pinfunction "1_BE1") (pintype "bidirectional"))
    )
    (net (code "879") (name "unconnected-(U$1AT-1-PadBE2)") (class "Default")
      (node (ref "U$1") (pin "BE2") (pinfunction "1_BE2") (pintype "bidirectional"))
    )
    (net (code "880") (name "unconnected-(U$1AW-1-PadBH1)") (class "Default")
      (node (ref "U$1") (pin "BH1") (pinfunction "1_BH1") (pintype "bidirectional"))
    )
    (net (code "881") (name "unconnected-(U$1AX-1-PadBH2)") (class "Default")
      (node (ref "U$1") (pin "BH2") (pinfunction "1_BH2") (pintype "bidirectional"))
    )
    (net (code "882") (name "unconnected-(U$1AY-1-PadBJ1)") (class "Default")
      (node (ref "U$1") (pin "BJ1") (pinfunction "1_BJ1") (pintype "bidirectional"))
    )
    (net (code "883") (name "unconnected-(U$1AZ-1-PadBJ2)") (class "Default")
      (node (ref "U$1") (pin "BJ2") (pinfunction "1_BJ2") (pintype "bidirectional"))
    )
    (net (code "884") (name "unconnected-(U$1BA-1-PadBK1)") (class "Default")
      (node (ref "U$1") (pin "BK1") (pinfunction "1_BK1") (pintype "bidirectional"))
    )
    (net (code "885") (name "unconnected-(U$1BB-1-PadBK2)") (class "Default")
      (node (ref "U$1") (pin "BK2") (pinfunction "1_BK2") (pintype "bidirectional"))
    )
    (net (code "886") (name "unconnected-(U$1BC-1-PadBL1)") (class "Default")
      (node (ref "U$1") (pin "BL1") (pinfunction "1_BL1") (pintype "bidirectional"))
    )
    (net (code "887") (name "unconnected-(U$1BD-1-PadBL2)") (class "Default")
      (node (ref "U$1") (pin "BL2") (pinfunction "1_BL2") (pintype "bidirectional"))
    )
    (net (code "888") (name "unconnected-(U$1BE-1-PadBM1)") (class "Default")
      (node (ref "U$1") (pin "BM1") (pinfunction "1_BM1") (pintype "bidirectional"))
    )
    (net (code "889") (name "unconnected-(U$1BF-1-PadBM2)") (class "Default")
      (node (ref "U$1") (pin "BM2") (pinfunction "1_BM2") (pintype "bidirectional"))
    )
    (net (code "890") (name "unconnected-(U$1BI-1-PadBP1)") (class "Default")
      (node (ref "U$1") (pin "BP1") (pinfunction "1_BP1") (pintype "bidirectional"))
    )
    (net (code "891") (name "unconnected-(U$1BJ-1-PadBP2)") (class "Default")
      (node (ref "U$1") (pin "BP2") (pinfunction "1_BP2") (pintype "bidirectional"))
    )
    (net (code "892") (name "unconnected-(U$1BK-1-PadBR1)") (class "Default")
      (node (ref "U$1") (pin "BR1") (pinfunction "1_BR1") (pintype "bidirectional"))
    )
    (net (code "893") (name "unconnected-(U$1BL-1-PadBR2)") (class "Default")
      (node (ref "U$1") (pin "BR2") (pinfunction "1_BR2") (pintype "bidirectional"))
    )
    (net (code "894") (name "unconnected-(U$1BM-1-PadBS1)") (class "Default")
      (node (ref "U$1") (pin "BS1") (pinfunction "1_BS1") (pintype "bidirectional"))
    )
    (net (code "895") (name "unconnected-(U$1BN-1-PadBS2)") (class "Default")
      (node (ref "U$1") (pin "BS2") (pinfunction "1_BS2") (pintype "bidirectional"))
    )
    (net (code "896") (name "unconnected-(U$1BQ-1-PadBU1)") (class "Default")
      (node (ref "U$1") (pin "BU1") (pinfunction "1_BU1") (pintype "bidirectional"))
    )
    (net (code "897") (name "unconnected-(U$1BR-1-PadBU2)") (class "Default")
      (node (ref "U$1") (pin "BU2") (pinfunction "1_BU2") (pintype "bidirectional"))
    )
    (net (code "898") (name "unconnected-(U$1BS-1-PadBV1)") (class "Default")
      (node (ref "U$1") (pin "BV1") (pinfunction "1_BV1") (pintype "bidirectional"))
    )
    (net (code "899") (name "unconnected-(U$1BT-1-PadBV2)") (class "Default")
      (node (ref "U$1") (pin "BV2") (pinfunction "1_BV2") (pintype "bidirectional"))
    )
    (net (code "900") (name "unconnected-(U$1BU-1-PadCA1)") (class "Default")
      (node (ref "U$1") (pin "CA1") (pinfunction "1_CA1") (pintype "bidirectional"))
    )
    (net (code "901") (name "unconnected-(U$1BW-1-PadCB1)") (class "Default")
      (node (ref "U$1") (pin "CB1") (pinfunction "1_CB1") (pintype "bidirectional"))
    )
    (net (code "902") (name "unconnected-(U$1BX-1-PadCB2)") (class "Default")
      (node (ref "U$1") (pin "CB2") (pinfunction "1_CB2") (pintype "bidirectional"))
    )
    (net (code "903") (name "unconnected-(U$1C-1-PadAB1)") (class "Default")
      (node (ref "U$1") (pin "AB1") (pinfunction "1_AB1") (pintype "bidirectional"))
    )
    (net (code "904") (name "unconnected-(U$1CA-1-PadCD1)") (class "Default")
      (node (ref "U$1") (pin "CD1") (pinfunction "1_CD1") (pintype "bidirectional"))
    )
    (net (code "905") (name "unconnected-(U$1CB-1-PadCD2)") (class "Default")
      (node (ref "U$1") (pin "CD2") (pinfunction "1_CD2") (pintype "bidirectional"))
    )
    (net (code "906") (name "unconnected-(U$1CC-1-PadCE1)") (class "Default")
      (node (ref "U$1") (pin "CE1") (pinfunction "1_CE1") (pintype "bidirectional"))
    )
    (net (code "907") (name "unconnected-(U$1CD-1-PadCE2)") (class "Default")
      (node (ref "U$1") (pin "CE2") (pinfunction "1_CE2") (pintype "bidirectional"))
    )
    (net (code "908") (name "unconnected-(U$1CG-1-PadCH1)") (class "Default")
      (node (ref "U$1") (pin "CH1") (pinfunction "1_CH1") (pintype "bidirectional"))
    )
    (net (code "909") (name "unconnected-(U$1CH-1-PadCH2)") (class "Default")
      (node (ref "U$1") (pin "CH2") (pinfunction "1_CH2") (pintype "bidirectional"))
    )
    (net (code "910") (name "unconnected-(U$1CI-1-PadCJ1)") (class "Default")
      (node (ref "U$1") (pin "CJ1") (pinfunction "1_CJ1") (pintype "bidirectional"))
    )
    (net (code "911") (name "unconnected-(U$1CJ-1-PadCJ2)") (class "Default")
      (node (ref "U$1") (pin "CJ2") (pinfunction "1_CJ2") (pintype "bidirectional"))
    )
    (net (code "912") (name "unconnected-(U$1CK-1-PadCK1)") (class "Default")
      (node (ref "U$1") (pin "CK1") (pinfunction "1_CK1") (pintype "bidirectional"))
    )
    (net (code "913") (name "unconnected-(U$1CL-1-PadCK2)") (class "Default")
      (node (ref "U$1") (pin "CK2") (pinfunction "1_CK2") (pintype "bidirectional"))
    )
    (net (code "914") (name "unconnected-(U$1CM-1-PadCL1)") (class "Default")
      (node (ref "U$1") (pin "CL1") (pinfunction "1_CL1") (pintype "bidirectional"))
    )
    (net (code "915") (name "unconnected-(U$1CN-1-PadCL2)") (class "Default")
      (node (ref "U$1") (pin "CL2") (pinfunction "1_CL2") (pintype "bidirectional"))
    )
    (net (code "916") (name "unconnected-(U$1CO-1-PadCM1)") (class "Default")
      (node (ref "U$1") (pin "CM1") (pinfunction "1_CM1") (pintype "bidirectional"))
    )
    (net (code "917") (name "unconnected-(U$1CP-1-PadCM2)") (class "Default")
      (node (ref "U$1") (pin "CM2") (pinfunction "1_CM2") (pintype "bidirectional"))
    )
    (net (code "918") (name "unconnected-(U$1CS-1-PadCP1)") (class "Default")
      (node (ref "U$1") (pin "CP1") (pinfunction "1_CP1") (pintype "bidirectional"))
    )
    (net (code "919") (name "unconnected-(U$1CT-1-PadCP2)") (class "Default")
      (node (ref "U$1") (pin "CP2") (pinfunction "1_CP2") (pintype "bidirectional"))
    )
    (net (code "920") (name "unconnected-(U$1CU-1-PadCR1)") (class "Default")
      (node (ref "U$1") (pin "CR1") (pinfunction "1_CR1") (pintype "bidirectional"))
    )
    (net (code "921") (name "unconnected-(U$1CV-1-PadCR2)") (class "Default")
      (node (ref "U$1") (pin "CR2") (pinfunction "1_CR2") (pintype "bidirectional"))
    )
    (net (code "922") (name "unconnected-(U$1CW-1-PadCS1)") (class "Default")
      (node (ref "U$1") (pin "CS1") (pinfunction "1_CS1") (pintype "bidirectional"))
    )
    (net (code "923") (name "unconnected-(U$1CX-1-PadCS2)") (class "Default")
      (node (ref "U$1") (pin "CS2") (pinfunction "1_CS2") (pintype "bidirectional"))
    )
    (net (code "924") (name "unconnected-(U$1D-1-PadAB2)") (class "Default")
      (node (ref "U$1") (pin "AB2") (pinfunction "1_AB2") (pintype "bidirectional"))
    )
    (net (code "925") (name "unconnected-(U$1DA-1-PadCU1)") (class "Default")
      (node (ref "U$1") (pin "CU1") (pinfunction "1_CU1") (pintype "bidirectional"))
    )
    (net (code "926") (name "unconnected-(U$1DB-1-PadCU2)") (class "Default")
      (node (ref "U$1") (pin "CU2") (pinfunction "1_CU2") (pintype "bidirectional"))
    )
    (net (code "927") (name "unconnected-(U$1DC-1-PadCV1)") (class "Default")
      (node (ref "U$1") (pin "CV1") (pinfunction "1_CV1") (pintype "bidirectional"))
    )
    (net (code "928") (name "unconnected-(U$1DD-1-PadCV2)") (class "Default")
      (node (ref "U$1") (pin "CV2") (pinfunction "1_CV2") (pintype "bidirectional"))
    )
    (net (code "929") (name "unconnected-(U$1DE-1-PadDA1)") (class "Default")
      (node (ref "U$1") (pin "DA1") (pinfunction "1_DA1") (pintype "bidirectional"))
    )
    (net (code "930") (name "unconnected-(U$1DF-1-PadDA2)") (class "Default")
      (node (ref "U$1") (pin "DA2") (pinfunction "1_DA2") (pintype "bidirectional"))
    )
    (net (code "931") (name "unconnected-(U$1DG-1-PadDB1)") (class "Default")
      (node (ref "U$1") (pin "DB1") (pinfunction "1_DB1") (pintype "bidirectional"))
    )
    (net (code "932") (name "unconnected-(U$1DH-1-PadDB2)") (class "Default")
      (node (ref "U$1") (pin "DB2") (pinfunction "1_DB2") (pintype "bidirectional"))
    )
    (net (code "933") (name "unconnected-(U$1DK-1-PadDD1)") (class "Default")
      (node (ref "U$1") (pin "DD1") (pinfunction "1_DD1") (pintype "bidirectional"))
    )
    (net (code "934") (name "unconnected-(U$1DL-1-PadDD2)") (class "Default")
      (node (ref "U$1") (pin "DD2") (pinfunction "1_DD2") (pintype "bidirectional"))
    )
    (net (code "935") (name "unconnected-(U$1DM-1-PadDE1)") (class "Default")
      (node (ref "U$1") (pin "DE1") (pinfunction "1_DE1") (pintype "bidirectional"))
    )
    (net (code "936") (name "unconnected-(U$1DN-1-PadDE2)") (class "Default")
      (node (ref "U$1") (pin "DE2") (pinfunction "1_DE2") (pintype "bidirectional"))
    )
    (net (code "937") (name "unconnected-(U$1DQ-1-PadDH1)") (class "Default")
      (node (ref "U$1") (pin "DH1") (pinfunction "1_DH1") (pintype "bidirectional"))
    )
    (net (code "938") (name "unconnected-(U$1DR-1-PadDH2)") (class "Default")
      (node (ref "U$1") (pin "DH2") (pinfunction "1_DH2") (pintype "bidirectional"))
    )
    (net (code "939") (name "unconnected-(U$1DS-1-PadDJ1)") (class "Default")
      (node (ref "U$1") (pin "DJ1") (pinfunction "1_DJ1") (pintype "bidirectional"))
    )
    (net (code "940") (name "unconnected-(U$1DT-1-PadDJ2)") (class "Default")
      (node (ref "U$1") (pin "DJ2") (pinfunction "1_DJ2") (pintype "bidirectional"))
    )
    (net (code "941") (name "unconnected-(U$1DU-1-PadDK1)") (class "Default")
      (node (ref "U$1") (pin "DK1") (pinfunction "1_DK1") (pintype "bidirectional"))
    )
    (net (code "942") (name "unconnected-(U$1DV-1-PadDK2)") (class "Default")
      (node (ref "U$1") (pin "DK2") (pinfunction "1_DK2") (pintype "bidirectional"))
    )
    (net (code "943") (name "unconnected-(U$1DW-1-PadDL1)") (class "Default")
      (node (ref "U$1") (pin "DL1") (pinfunction "1_DL1") (pintype "bidirectional"))
    )
    (net (code "944") (name "unconnected-(U$1DX-1-PadDL2)") (class "Default")
      (node (ref "U$1") (pin "DL2") (pinfunction "1_DL2") (pintype "bidirectional"))
    )
    (net (code "945") (name "unconnected-(U$1DY-1-PadDM1)") (class "Default")
      (node (ref "U$1") (pin "DM1") (pinfunction "1_DM1") (pintype "bidirectional"))
    )
    (net (code "946") (name "unconnected-(U$1DZ-1-PadDM2)") (class "Default")
      (node (ref "U$1") (pin "DM2") (pinfunction "1_DM2") (pintype "bidirectional"))
    )
    (net (code "947") (name "unconnected-(U$1EC-1-PadDP1)") (class "Default")
      (node (ref "U$1") (pin "DP1") (pinfunction "1_DP1") (pintype "bidirectional"))
    )
    (net (code "948") (name "unconnected-(U$1ED-1-PadDP2)") (class "Default")
      (node (ref "U$1") (pin "DP2") (pinfunction "1_DP2") (pintype "bidirectional"))
    )
    (net (code "949") (name "unconnected-(U$1EE-1-PadDR1)") (class "Default")
      (node (ref "U$1") (pin "DR1") (pinfunction "1_DR1") (pintype "bidirectional"))
    )
    (net (code "950") (name "unconnected-(U$1EF-1-PadDR2)") (class "Default")
      (node (ref "U$1") (pin "DR2") (pinfunction "1_DR2") (pintype "bidirectional"))
    )
    (net (code "951") (name "unconnected-(U$1EG-1-PadDS1)") (class "Default")
      (node (ref "U$1") (pin "DS1") (pinfunction "1_DS1") (pintype "bidirectional"))
    )
    (net (code "952") (name "unconnected-(U$1EH-1-PadDS2)") (class "Default")
      (node (ref "U$1") (pin "DS2") (pinfunction "1_DS2") (pintype "bidirectional"))
    )
    (net (code "953") (name "unconnected-(U$1EK-1-PadDU1)") (class "Default")
      (node (ref "U$1") (pin "DU1") (pinfunction "1_DU1") (pintype "bidirectional"))
    )
    (net (code "954") (name "unconnected-(U$1EL-1-PadDU2)") (class "Default")
      (node (ref "U$1") (pin "DU2") (pinfunction "1_DU2") (pintype "bidirectional"))
    )
    (net (code "955") (name "unconnected-(U$1EM-1-PadDV1)") (class "Default")
      (node (ref "U$1") (pin "DV1") (pinfunction "1_DV1") (pintype "bidirectional"))
    )
    (net (code "956") (name "unconnected-(U$1EN-1-PadDV2)") (class "Default")
      (node (ref "U$1") (pin "DV2") (pinfunction "1_DV2") (pintype "bidirectional"))
    )
    (net (code "957") (name "unconnected-(U$1G-1-PadAD1)") (class "Default")
      (node (ref "U$1") (pin "AD1") (pinfunction "1_AD1") (pintype "bidirectional"))
    )
    (net (code "958") (name "unconnected-(U$1H-1-PadAD2)") (class "Default")
      (node (ref "U$1") (pin "AD2") (pinfunction "1_AD2") (pintype "bidirectional"))
    )
    (net (code "959") (name "unconnected-(U$1I-1-PadAE1)") (class "Default")
      (node (ref "U$1") (pin "AE1") (pinfunction "1_AE1") (pintype "bidirectional"))
    )
    (net (code "960") (name "unconnected-(U$1J-1-PadAE2)") (class "Default")
      (node (ref "U$1") (pin "AE2") (pinfunction "1_AE2") (pintype "bidirectional"))
    )
    (net (code "961") (name "unconnected-(U$1M-1-PadAH1)") (class "Default")
      (node (ref "U$1") (pin "AH1") (pinfunction "1_AH1") (pintype "bidirectional"))
    )
    (net (code "962") (name "unconnected-(U$1N-1-PadAH2)") (class "Default")
      (node (ref "U$1") (pin "AH2") (pinfunction "1_AH2") (pintype "bidirectional"))
    )
    (net (code "963") (name "unconnected-(U$1O-1-PadAJ1)") (class "Default")
      (node (ref "U$1") (pin "AJ1") (pinfunction "1_AJ1") (pintype "bidirectional"))
    )
    (net (code "964") (name "unconnected-(U$1P-1-PadAJ2)") (class "Default")
      (node (ref "U$1") (pin "AJ2") (pinfunction "1_AJ2") (pintype "bidirectional"))
    )
    (net (code "965") (name "unconnected-(U$1Q-1-PadAK1)") (class "Default")
      (node (ref "U$1") (pin "AK1") (pinfunction "1_AK1") (pintype "bidirectional"))
    )
    (net (code "966") (name "unconnected-(U$1R-1-PadAK2)") (class "Default")
      (node (ref "U$1") (pin "AK2") (pinfunction "1_AK2") (pintype "bidirectional"))
    )
    (net (code "967") (name "unconnected-(U$1S-1-PadAL1)") (class "Default")
      (node (ref "U$1") (pin "AL1") (pinfunction "1_AL1") (pintype "bidirectional"))
    )
    (net (code "968") (name "unconnected-(U$1T-1-PadAL2)") (class "Default")
      (node (ref "U$1") (pin "AL2") (pinfunction "1_AL2") (pintype "bidirectional"))
    )
    (net (code "969") (name "unconnected-(U$1U-1-PadAM1)") (class "Default")
      (node (ref "U$1") (pin "AM1") (pinfunction "1_AM1") (pintype "bidirectional"))
    )
    (net (code "970") (name "unconnected-(U$1V-1-PadAM2)") (class "Default")
      (node (ref "U$1") (pin "AM2") (pinfunction "1_AM2") (pintype "bidirectional"))
    )
    (net (code "971") (name "unconnected-(U$1Y-1-PadAP1)") (class "Default")
      (node (ref "U$1") (pin "AP1") (pinfunction "1_AP1") (pintype "bidirectional"))
    )
    (net (code "972") (name "unconnected-(U$1Z-1-PadAP2)") (class "Default")
      (node (ref "U$1") (pin "AP2") (pinfunction "1_AP2") (pintype "bidirectional"))
    )
  )
)
